# L3DCube_16x16_Base_Rev3.net
KiCad netlist of a schematic drawn in EAGLE
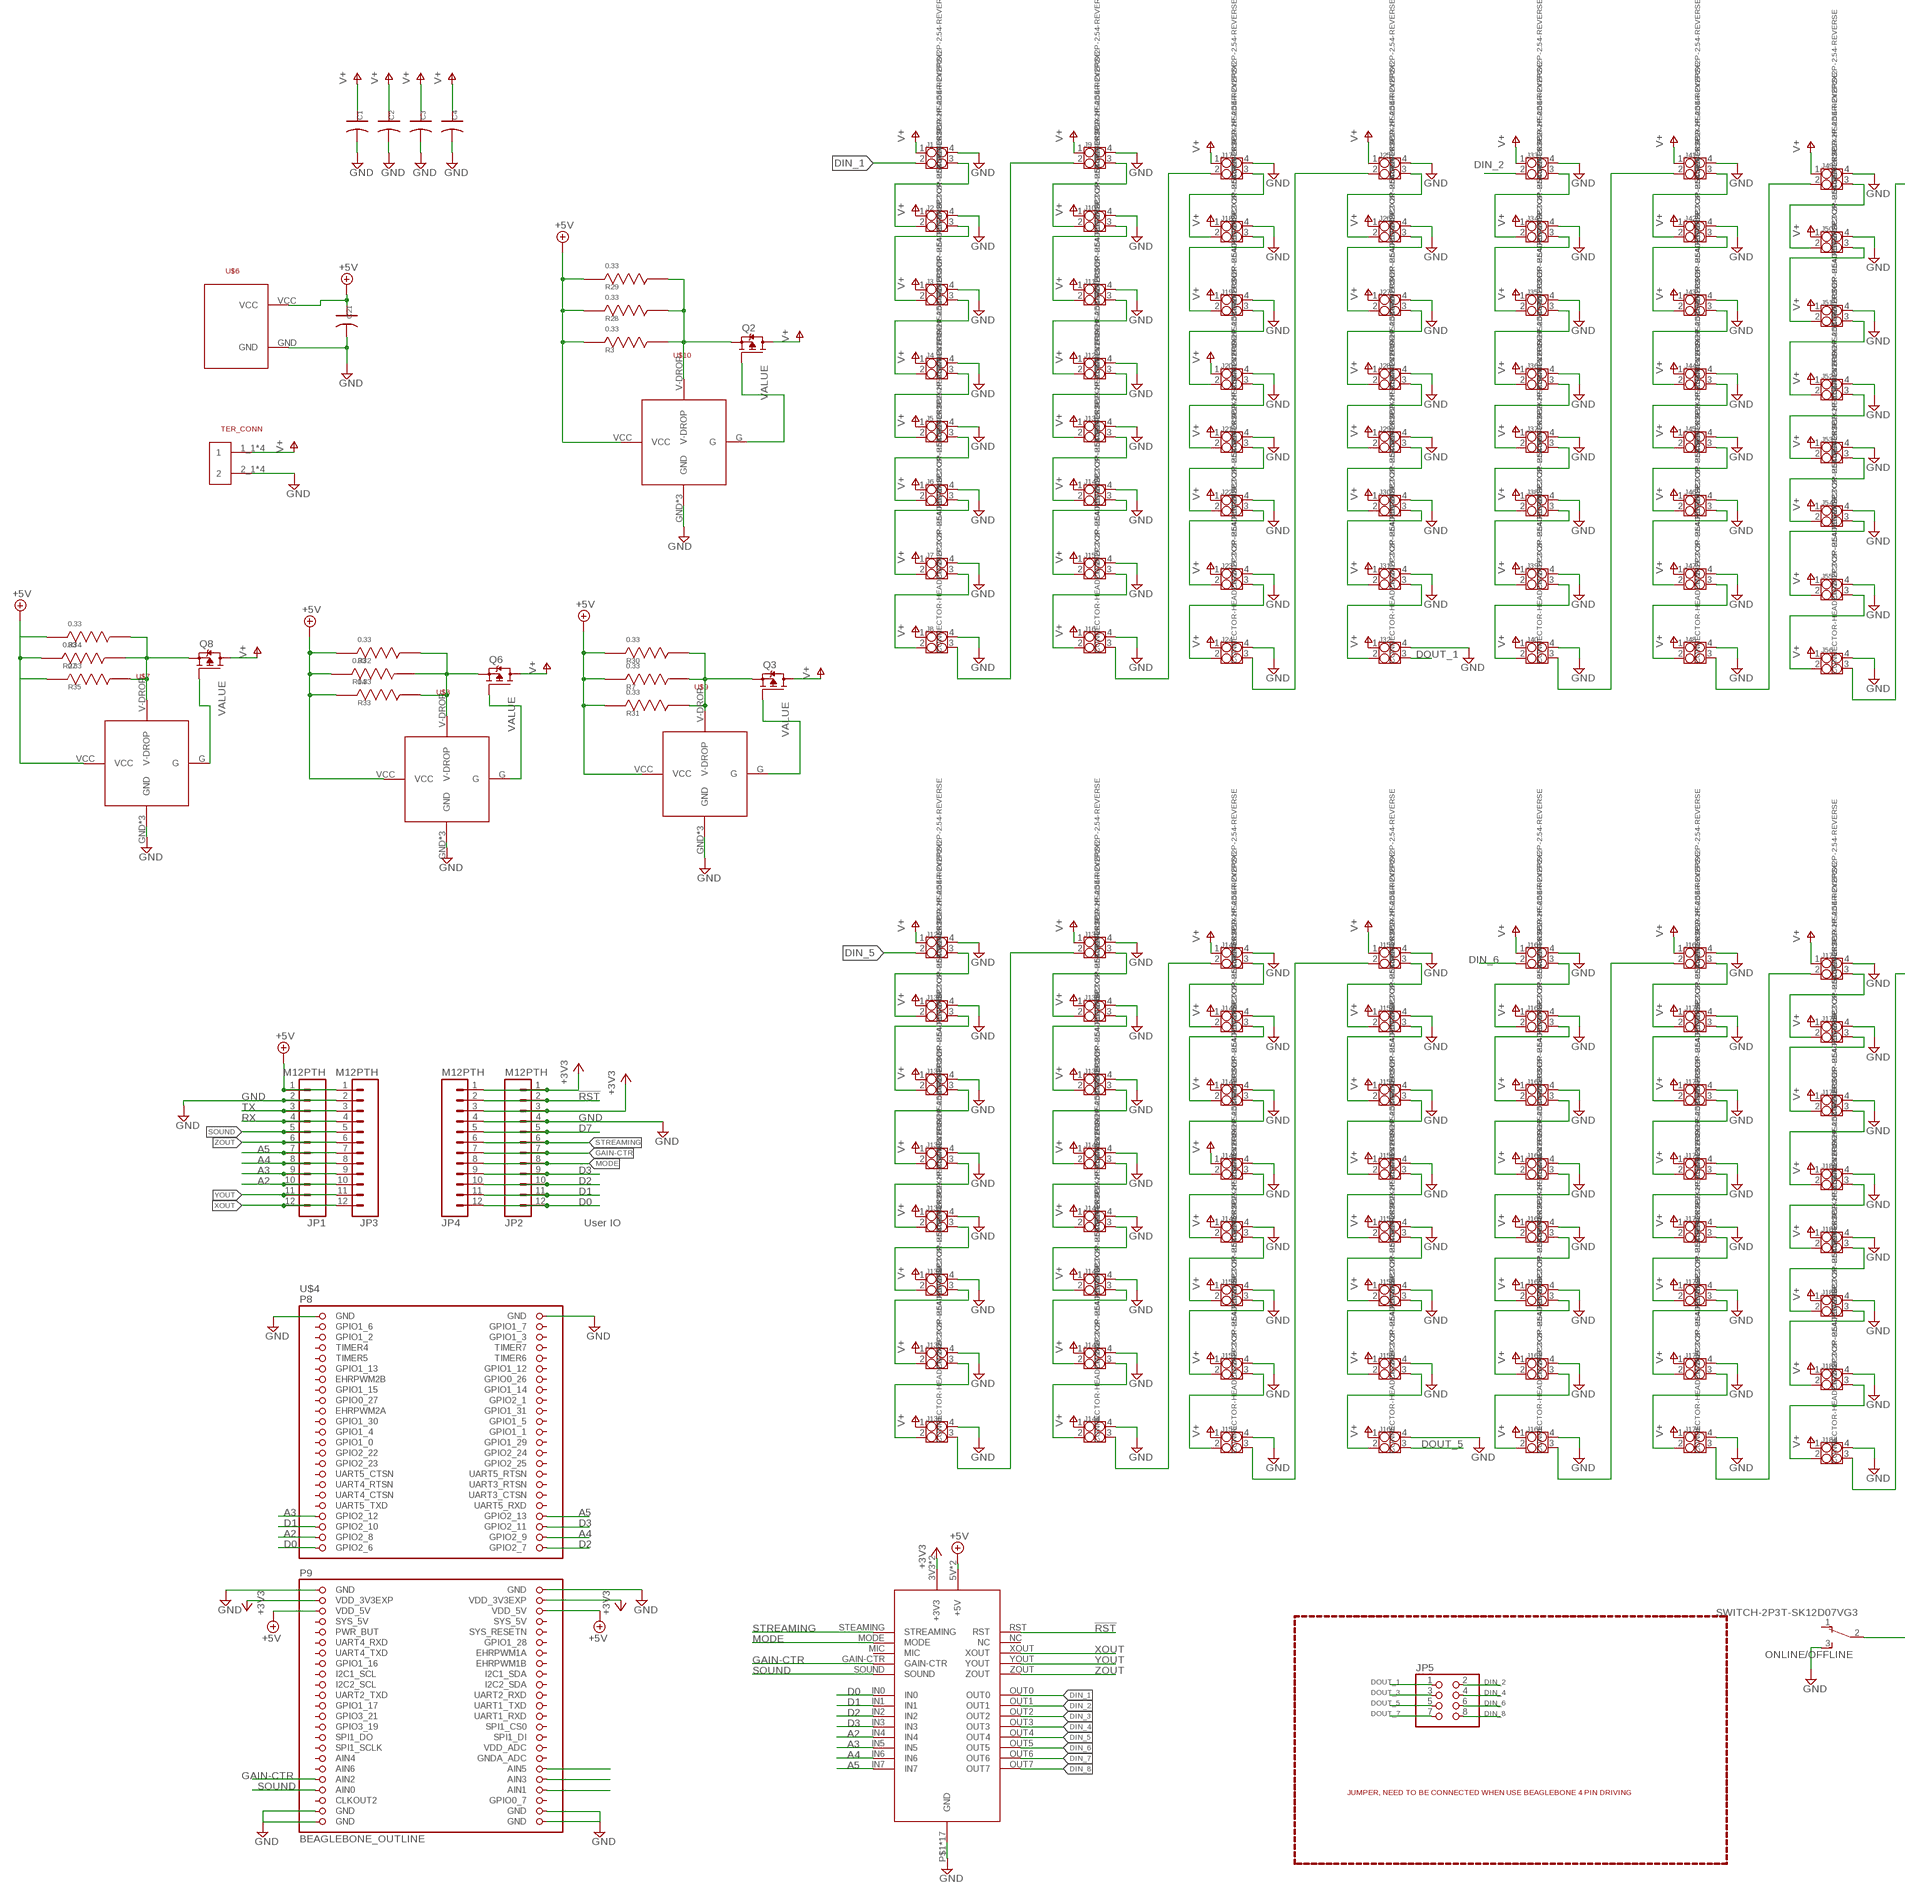
[diagram p0: schematic, sheet 1, part 1 of 2]
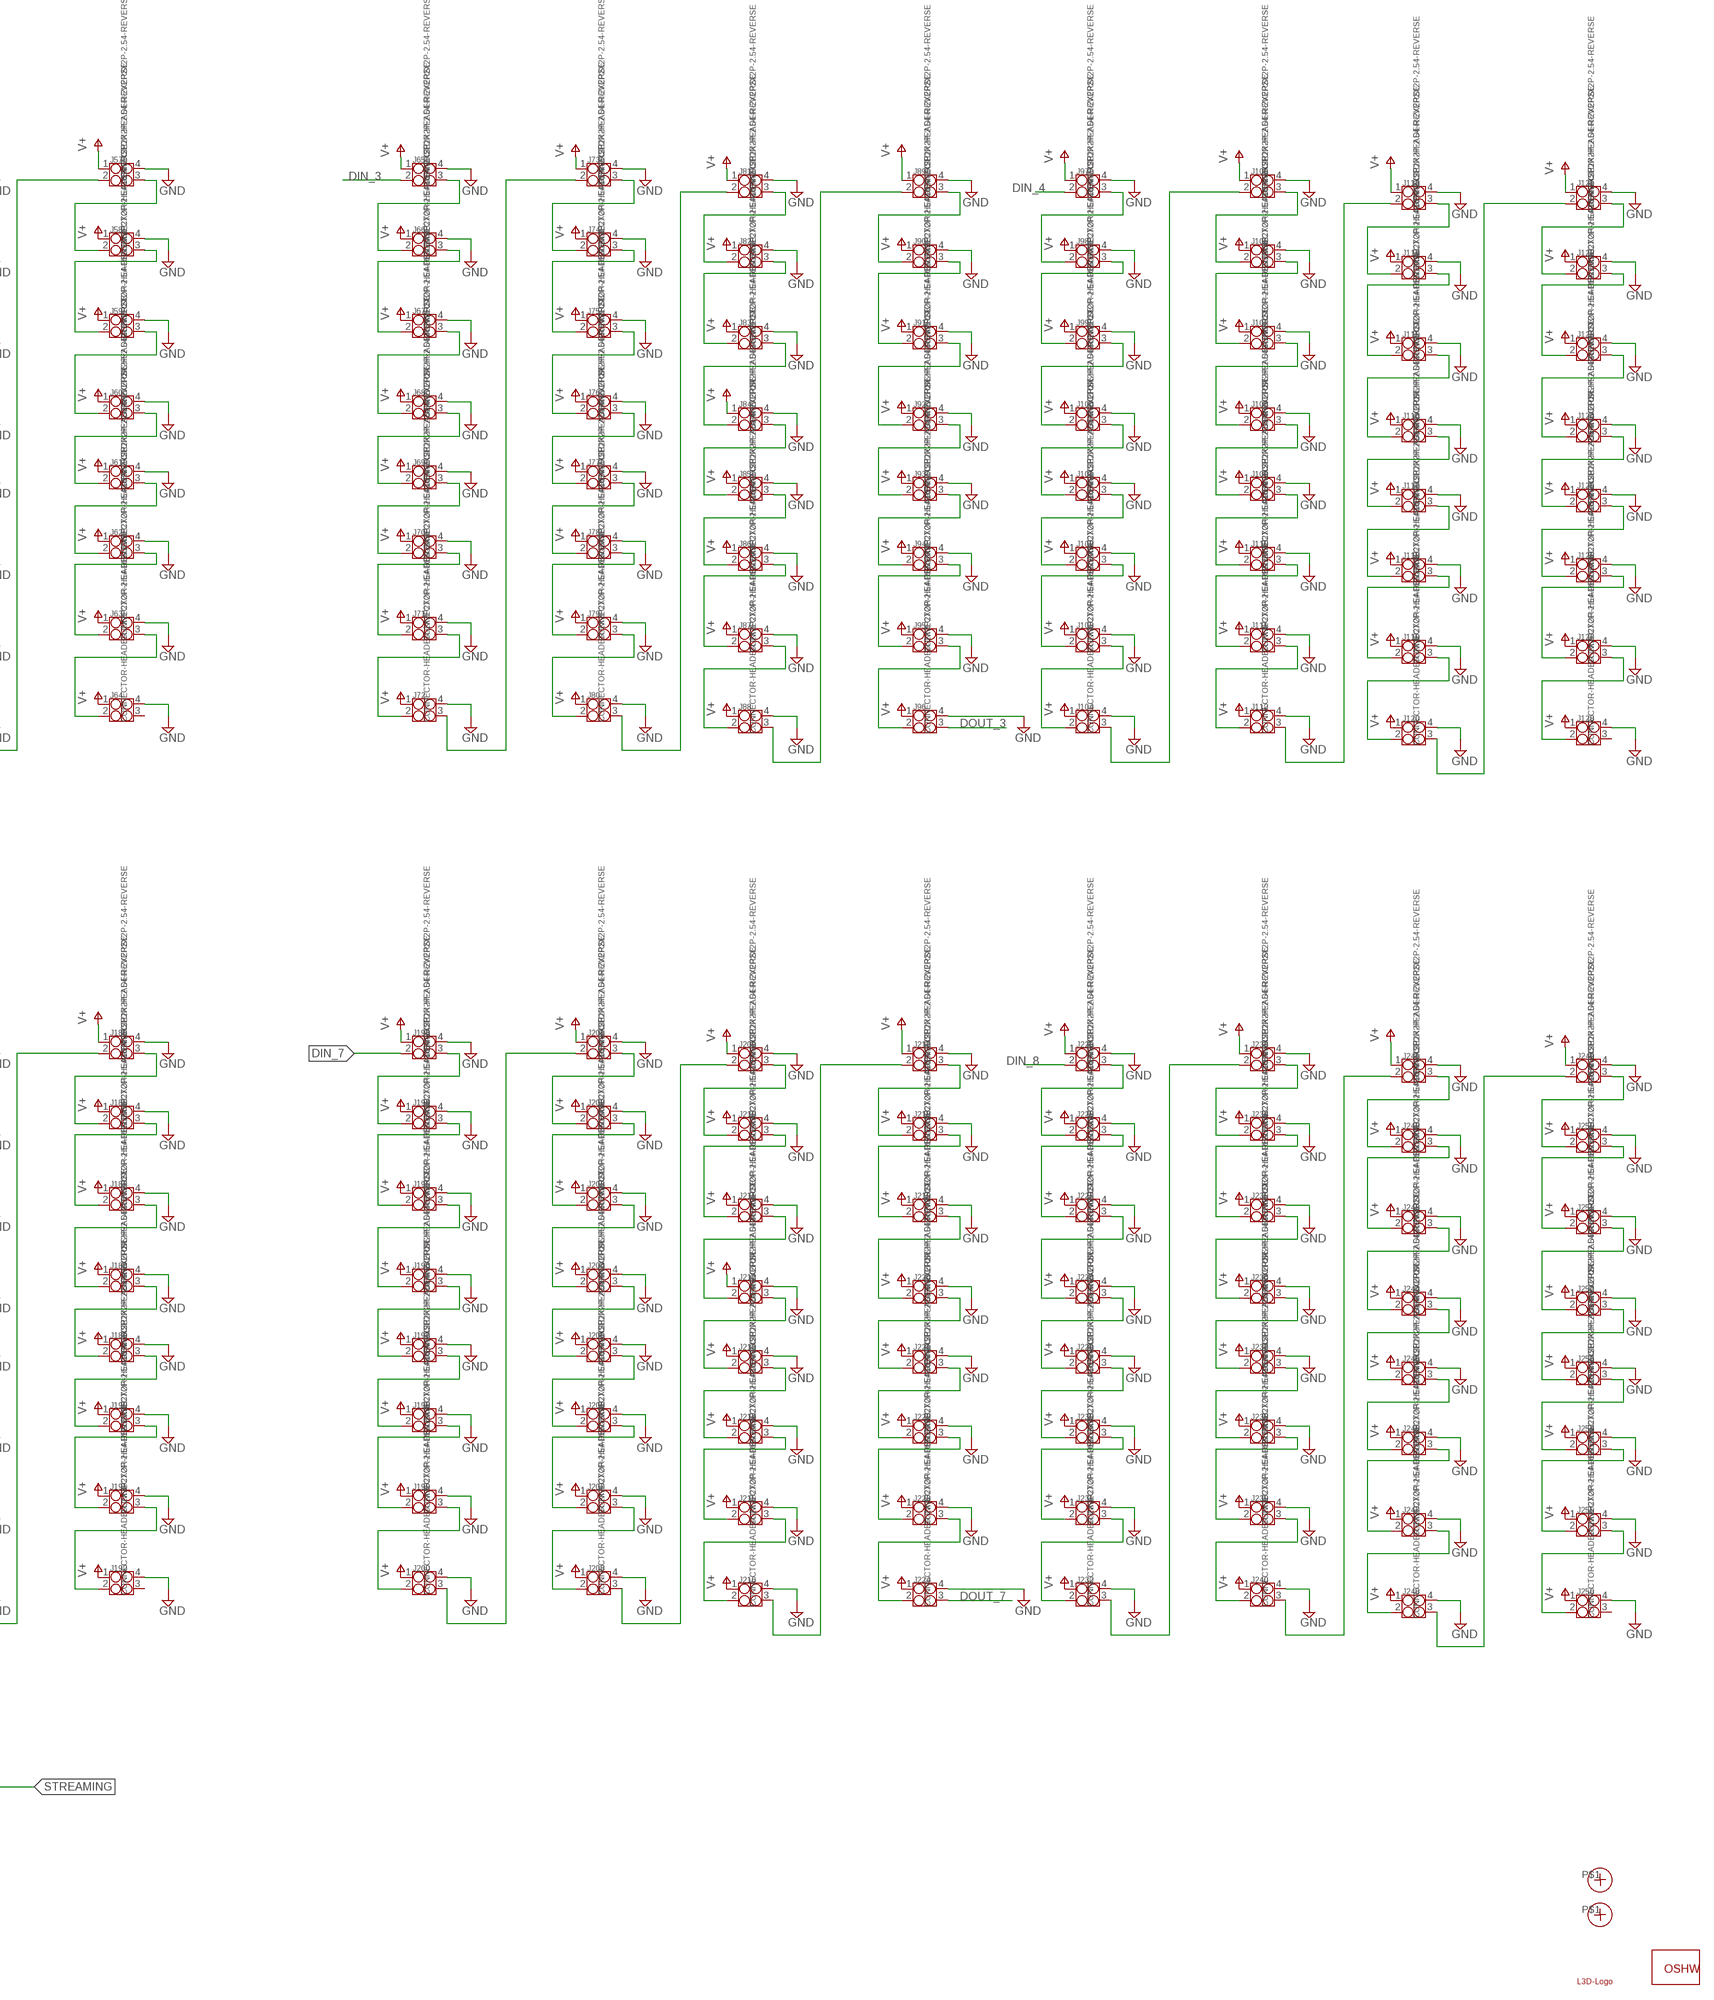
[diagram p1: schematic, sheet 1, part 2 of 2]

(export (version "E")
  (design (tool "Eeschema 10.0.6"))
  (components
    (comp (ref "C1")
      (value "C-POLAR")
      (footprint "eagle-import:CAPACITOR-E3-8")
      (libsource (lib "eagle-import") (part "C-POLAR"))
    )
    (comp (ref "C2")
      (value "C-POLAR")
      (footprint "eagle-import:CAPACITOR-E3-8")
      (libsource (lib "eagle-import") (part "C-POLAR"))
    )
    (comp (ref "C3")
      (value "C-POLAR")
      (footprint "eagle-import:CAPACITOR-E3-8")
      (libsource (lib "eagle-import") (part "C-POLAR"))
    )
    (comp (ref "C4")
      (value "C-POLAR")
      (footprint "eagle-import:CAPACITOR-E3-8")
      (libsource (lib "eagle-import") (part "C-POLAR"))
    )
    (comp (ref "C21")
      (value "C-POLAR")
      (footprint "eagle-import:CAPACITOR-E3-8")
      (libsource (lib "eagle-import") (part "C-POLAR"))
    )
    (comp (ref "GOLD_ORB_SM1")
      (value "OSHWLOGO_GOLD_ORB_LG")
      (footprint "eagle-import:OSHW0")
      (libsource (lib "eagle-import") (part "OSHWLOGO_GOLD_ORB_LG"))
    )
    (comp (ref "J1")
      (value "CONNECTOR-HEADER-2X2P2X2P-2.54-REVERSE")
      (footprint "eagle-import:2X2P-2.54-REVERSE")
      (libsource (lib "eagle-import") (part "CONNECTOR-HEADER-2X2P2X2P-2.54-REVERSE"))
    )
    (comp (ref "J2")
      (value "CONNECTOR-HEADER-2X2P2X2P-2.54-REVERSE")
      (footprint "eagle-import:2X2P-2.54-REVERSE")
      (libsource (lib "eagle-import") (part "CONNECTOR-HEADER-2X2P2X2P-2.54-REVERSE"))
    )
    (comp (ref "J3")
      (value "CONNECTOR-HEADER-2X2P2X2P-2.54-REVERSE")
      (footprint "eagle-import:2X2P-2.54-REVERSE")
      (libsource (lib "eagle-import") (part "CONNECTOR-HEADER-2X2P2X2P-2.54-REVERSE"))
    )
    (comp (ref "J4")
      (value "CONNECTOR-HEADER-2X2P2X2P-2.54-REVERSE")
      (footprint "eagle-import:2X2P-2.54-REVERSE")
      (libsource (lib "eagle-import") (part "CONNECTOR-HEADER-2X2P2X2P-2.54-REVERSE"))
    )
    (comp (ref "J5")
      (value "CONNECTOR-HEADER-2X2P2X2P-2.54-REVERSE")
      (footprint "eagle-import:2X2P-2.54-REVERSE")
      (libsource (lib "eagle-import") (part "CONNECTOR-HEADER-2X2P2X2P-2.54-REVERSE"))
    )
    (comp (ref "J6")
      (value "CONNECTOR-HEADER-2X2P2X2P-2.54-REVERSE")
      (footprint "eagle-import:2X2P-2.54-REVERSE")
      (libsource (lib "eagle-import") (part "CONNECTOR-HEADER-2X2P2X2P-2.54-REVERSE"))
    )
    (comp (ref "J7")
      (value "CONNECTOR-HEADER-2X2P2X2P-2.54-REVERSE")
      (footprint "eagle-import:2X2P-2.54-REVERSE")
      (libsource (lib "eagle-import") (part "CONNECTOR-HEADER-2X2P2X2P-2.54-REVERSE"))
    )
    (comp (ref "J8")
      (value "CONNECTOR-HEADER-2X2P2X2P-2.54-REVERSE")
      (footprint "eagle-import:2X2P-2.54-REVERSE")
      (libsource (lib "eagle-import") (part "CONNECTOR-HEADER-2X2P2X2P-2.54-REVERSE"))
    )
    (comp (ref "J9")
      (value "CONNECTOR-HEADER-2X2P2X2P-2.54-REVERSE")
      (footprint "eagle-import:2X2P-2.54-REVERSE")
      (libsource (lib "eagle-import") (part "CONNECTOR-HEADER-2X2P2X2P-2.54-REVERSE"))
    )
    (comp (ref "J10")
      (value "CONNECTOR-HEADER-2X2P2X2P-2.54-REVERSE")
      (footprint "eagle-import:2X2P-2.54-REVERSE")
      (libsource (lib "eagle-import") (part "CONNECTOR-HEADER-2X2P2X2P-2.54-REVERSE"))
    )
    (comp (ref "J11")
      (value "CONNECTOR-HEADER-2X2P2X2P-2.54-REVERSE")
      (footprint "eagle-import:2X2P-2.54-REVERSE")
      (libsource (lib "eagle-import") (part "CONNECTOR-HEADER-2X2P2X2P-2.54-REVERSE"))
    )
    (comp (ref "J12")
      (value "CONNECTOR-HEADER-2X2P2X2P-2.54-REVERSE")
      (footprint "eagle-import:2X2P-2.54-REVERSE")
      (libsource (lib "eagle-import") (part "CONNECTOR-HEADER-2X2P2X2P-2.54-REVERSE"))
    )
    (comp (ref "J13")
      (value "CONNECTOR-HEADER-2X2P2X2P-2.54-REVERSE")
      (footprint "eagle-import:2X2P-2.54-REVERSE")
      (libsource (lib "eagle-import") (part "CONNECTOR-HEADER-2X2P2X2P-2.54-REVERSE"))
    )
    (comp (ref "J14")
      (value "CONNECTOR-HEADER-2X2P2X2P-2.54-REVERSE")
      (footprint "eagle-import:2X2P-2.54-REVERSE")
      (libsource (lib "eagle-import") (part "CONNECTOR-HEADER-2X2P2X2P-2.54-REVERSE"))
    )
    (comp (ref "J15")
      (value "CONNECTOR-HEADER-2X2P2X2P-2.54-REVERSE")
      (footprint "eagle-import:2X2P-2.54-REVERSE")
      (libsource (lib "eagle-import") (part "CONNECTOR-HEADER-2X2P2X2P-2.54-REVERSE"))
    )
    (comp (ref "J16")
      (value "CONNECTOR-HEADER-2X2P2X2P-2.54-REVERSE")
      (footprint "eagle-import:2X2P-2.54-REVERSE")
      (libsource (lib "eagle-import") (part "CONNECTOR-HEADER-2X2P2X2P-2.54-REVERSE"))
    )
    (comp (ref "J17")
      (value "CONNECTOR-HEADER-2X2P2X2P-2.54-REVERSE")
      (footprint "eagle-import:2X2P-2.54-REVERSE")
      (libsource (lib "eagle-import") (part "CONNECTOR-HEADER-2X2P2X2P-2.54-REVERSE"))
    )
    (comp (ref "J18")
      (value "CONNECTOR-HEADER-2X2P2X2P-2.54-REVERSE")
      (footprint "eagle-import:2X2P-2.54-REVERSE")
      (libsource (lib "eagle-import") (part "CONNECTOR-HEADER-2X2P2X2P-2.54-REVERSE"))
    )
    (comp (ref "J19")
      (value "CONNECTOR-HEADER-2X2P2X2P-2.54-REVERSE")
      (footprint "eagle-import:2X2P-2.54-REVERSE")
      (libsource (lib "eagle-import") (part "CONNECTOR-HEADER-2X2P2X2P-2.54-REVERSE"))
    )
    (comp (ref "J20")
      (value "CONNECTOR-HEADER-2X2P2X2P-2.54-REVERSE")
      (footprint "eagle-import:2X2P-2.54-REVERSE")
      (libsource (lib "eagle-import") (part "CONNECTOR-HEADER-2X2P2X2P-2.54-REVERSE"))
    )
    (comp (ref "J21")
      (value "CONNECTOR-HEADER-2X2P2X2P-2.54-REVERSE")
      (footprint "eagle-import:2X2P-2.54-REVERSE")
      (libsource (lib "eagle-import") (part "CONNECTOR-HEADER-2X2P2X2P-2.54-REVERSE"))
    )
    (comp (ref "J22")
      (value "CONNECTOR-HEADER-2X2P2X2P-2.54-REVERSE")
      (footprint "eagle-import:2X2P-2.54-REVERSE")
      (libsource (lib "eagle-import") (part "CONNECTOR-HEADER-2X2P2X2P-2.54-REVERSE"))
    )
    (comp (ref "J23")
      (value "CONNECTOR-HEADER-2X2P2X2P-2.54-REVERSE")
      (footprint "eagle-import:2X2P-2.54-REVERSE")
      (libsource (lib "eagle-import") (part "CONNECTOR-HEADER-2X2P2X2P-2.54-REVERSE"))
    )
    (comp (ref "J24")
      (value "CONNECTOR-HEADER-2X2P2X2P-2.54-REVERSE")
      (footprint "eagle-import:2X2P-2.54-REVERSE")
      (libsource (lib "eagle-import") (part "CONNECTOR-HEADER-2X2P2X2P-2.54-REVERSE"))
    )
    (comp (ref "J25")
      (value "CONNECTOR-HEADER-2X2P2X2P-2.54-REVERSE")
      (footprint "eagle-import:2X2P-2.54-REVERSE")
      (libsource (lib "eagle-import") (part "CONNECTOR-HEADER-2X2P2X2P-2.54-REVERSE"))
    )
    (comp (ref "J26")
      (value "CONNECTOR-HEADER-2X2P2X2P-2.54-REVERSE")
      (footprint "eagle-import:2X2P-2.54-REVERSE")
      (libsource (lib "eagle-import") (part "CONNECTOR-HEADER-2X2P2X2P-2.54-REVERSE"))
    )
    (comp (ref "J27")
      (value "CONNECTOR-HEADER-2X2P2X2P-2.54-REVERSE")
      (footprint "eagle-import:2X2P-2.54-REVERSE")
      (libsource (lib "eagle-import") (part "CONNECTOR-HEADER-2X2P2X2P-2.54-REVERSE"))
    )
    (comp (ref "J28")
      (value "CONNECTOR-HEADER-2X2P2X2P-2.54-REVERSE")
      (footprint "eagle-import:2X2P-2.54-REVERSE")
      (libsource (lib "eagle-import") (part "CONNECTOR-HEADER-2X2P2X2P-2.54-REVERSE"))
    )
    (comp (ref "J29")
      (value "CONNECTOR-HEADER-2X2P2X2P-2.54-REVERSE")
      (footprint "eagle-import:2X2P-2.54-REVERSE")
      (libsource (lib "eagle-import") (part "CONNECTOR-HEADER-2X2P2X2P-2.54-REVERSE"))
    )
    (comp (ref "J30")
      (value "CONNECTOR-HEADER-2X2P2X2P-2.54-REVERSE")
      (footprint "eagle-import:2X2P-2.54-REVERSE")
      (libsource (lib "eagle-import") (part "CONNECTOR-HEADER-2X2P2X2P-2.54-REVERSE"))
    )
    (comp (ref "J31")
      (value "CONNECTOR-HEADER-2X2P2X2P-2.54-REVERSE")
      (footprint "eagle-import:2X2P-2.54-REVERSE")
      (libsource (lib "eagle-import") (part "CONNECTOR-HEADER-2X2P2X2P-2.54-REVERSE"))
    )
    (comp (ref "J32")
      (value "CONNECTOR-HEADER-2X2P2X2P-2.54-REVERSE")
      (footprint "eagle-import:2X2P-2.54-REVERSE")
      (libsource (lib "eagle-import") (part "CONNECTOR-HEADER-2X2P2X2P-2.54-REVERSE"))
    )
    (comp (ref "J33")
      (value "CONNECTOR-HEADER-2X2P2X2P-2.54-REVERSE")
      (footprint "eagle-import:2X2P-2.54-REVERSE")
      (libsource (lib "eagle-import") (part "CONNECTOR-HEADER-2X2P2X2P-2.54-REVERSE"))
    )
    (comp (ref "J34")
      (value "CONNECTOR-HEADER-2X2P2X2P-2.54-REVERSE")
      (footprint "eagle-import:2X2P-2.54-REVERSE")
      (libsource (lib "eagle-import") (part "CONNECTOR-HEADER-2X2P2X2P-2.54-REVERSE"))
    )
    (comp (ref "J35")
      (value "CONNECTOR-HEADER-2X2P2X2P-2.54-REVERSE")
      (footprint "eagle-import:2X2P-2.54-REVERSE")
      (libsource (lib "eagle-import") (part "CONNECTOR-HEADER-2X2P2X2P-2.54-REVERSE"))
    )
    (comp (ref "J36")
      (value "CONNECTOR-HEADER-2X2P2X2P-2.54-REVERSE")
      (footprint "eagle-import:2X2P-2.54-REVERSE")
      (libsource (lib "eagle-import") (part "CONNECTOR-HEADER-2X2P2X2P-2.54-REVERSE"))
    )
    (comp (ref "J37")
      (value "CONNECTOR-HEADER-2X2P2X2P-2.54-REVERSE")
      (footprint "eagle-import:2X2P-2.54-REVERSE")
      (libsource (lib "eagle-import") (part "CONNECTOR-HEADER-2X2P2X2P-2.54-REVERSE"))
    )
    (comp (ref "J38")
      (value "CONNECTOR-HEADER-2X2P2X2P-2.54-REVERSE")
      (footprint "eagle-import:2X2P-2.54-REVERSE")
      (libsource (lib "eagle-import") (part "CONNECTOR-HEADER-2X2P2X2P-2.54-REVERSE"))
    )
    (comp (ref "J39")
      (value "CONNECTOR-HEADER-2X2P2X2P-2.54-REVERSE")
      (footprint "eagle-import:2X2P-2.54-REVERSE")
      (libsource (lib "eagle-import") (part "CONNECTOR-HEADER-2X2P2X2P-2.54-REVERSE"))
    )
    (comp (ref "J40")
      (value "CONNECTOR-HEADER-2X2P2X2P-2.54-REVERSE")
      (footprint "eagle-import:2X2P-2.54-REVERSE")
      (libsource (lib "eagle-import") (part "CONNECTOR-HEADER-2X2P2X2P-2.54-REVERSE"))
    )
    (comp (ref "J41")
      (value "CONNECTOR-HEADER-2X2P2X2P-2.54-REVERSE")
      (footprint "eagle-import:2X2P-2.54-REVERSE")
      (libsource (lib "eagle-import") (part "CONNECTOR-HEADER-2X2P2X2P-2.54-REVERSE"))
    )
    (comp (ref "J42")
      (value "CONNECTOR-HEADER-2X2P2X2P-2.54-REVERSE")
      (footprint "eagle-import:2X2P-2.54-REVERSE")
      (libsource (lib "eagle-import") (part "CONNECTOR-HEADER-2X2P2X2P-2.54-REVERSE"))
    )
    (comp (ref "J43")
      (value "CONNECTOR-HEADER-2X2P2X2P-2.54-REVERSE")
      (footprint "eagle-import:2X2P-2.54-REVERSE")
      (libsource (lib "eagle-import") (part "CONNECTOR-HEADER-2X2P2X2P-2.54-REVERSE"))
    )
    (comp (ref "J44")
      (value "CONNECTOR-HEADER-2X2P2X2P-2.54-REVERSE")
      (footprint "eagle-import:2X2P-2.54-REVERSE")
      (libsource (lib "eagle-import") (part "CONNECTOR-HEADER-2X2P2X2P-2.54-REVERSE"))
    )
    (comp (ref "J45")
      (value "CONNECTOR-HEADER-2X2P2X2P-2.54-REVERSE")
      (footprint "eagle-import:2X2P-2.54-REVERSE")
      (libsource (lib "eagle-import") (part "CONNECTOR-HEADER-2X2P2X2P-2.54-REVERSE"))
    )
    (comp (ref "J46")
      (value "CONNECTOR-HEADER-2X2P2X2P-2.54-REVERSE")
      (footprint "eagle-import:2X2P-2.54-REVERSE")
      (libsource (lib "eagle-import") (part "CONNECTOR-HEADER-2X2P2X2P-2.54-REVERSE"))
    )
    (comp (ref "J47")
      (value "CONNECTOR-HEADER-2X2P2X2P-2.54-REVERSE")
      (footprint "eagle-import:2X2P-2.54-REVERSE")
      (libsource (lib "eagle-import") (part "CONNECTOR-HEADER-2X2P2X2P-2.54-REVERSE"))
    )
    (comp (ref "J48")
      (value "CONNECTOR-HEADER-2X2P2X2P-2.54-REVERSE")
      (footprint "eagle-import:2X2P-2.54-REVERSE")
      (libsource (lib "eagle-import") (part "CONNECTOR-HEADER-2X2P2X2P-2.54-REVERSE"))
    )
    (comp (ref "J49")
      (value "CONNECTOR-HEADER-2X2P2X2P-2.54-REVERSE")
      (footprint "eagle-import:2X2P-2.54-REVERSE")
      (libsource (lib "eagle-import") (part "CONNECTOR-HEADER-2X2P2X2P-2.54-REVERSE"))
    )
    (comp (ref "J50")
      (value "CONNECTOR-HEADER-2X2P2X2P-2.54-REVERSE")
      (footprint "eagle-import:2X2P-2.54-REVERSE")
      (libsource (lib "eagle-import") (part "CONNECTOR-HEADER-2X2P2X2P-2.54-REVERSE"))
    )
    (comp (ref "J51")
      (value "CONNECTOR-HEADER-2X2P2X2P-2.54-REVERSE")
      (footprint "eagle-import:2X2P-2.54-REVERSE")
      (libsource (lib "eagle-import") (part "CONNECTOR-HEADER-2X2P2X2P-2.54-REVERSE"))
    )
    (comp (ref "J52")
      (value "CONNECTOR-HEADER-2X2P2X2P-2.54-REVERSE")
      (footprint "eagle-import:2X2P-2.54-REVERSE")
      (libsource (lib "eagle-import") (part "CONNECTOR-HEADER-2X2P2X2P-2.54-REVERSE"))
    )
    (comp (ref "J53")
      (value "CONNECTOR-HEADER-2X2P2X2P-2.54-REVERSE")
      (footprint "eagle-import:2X2P-2.54-REVERSE")
      (libsource (lib "eagle-import") (part "CONNECTOR-HEADER-2X2P2X2P-2.54-REVERSE"))
    )
    (comp (ref "J54")
      (value "CONNECTOR-HEADER-2X2P2X2P-2.54-REVERSE")
      (footprint "eagle-import:2X2P-2.54-REVERSE")
      (libsource (lib "eagle-import") (part "CONNECTOR-HEADER-2X2P2X2P-2.54-REVERSE"))
    )
    (comp (ref "J55")
      (value "CONNECTOR-HEADER-2X2P2X2P-2.54-REVERSE")
      (footprint "eagle-import:2X2P-2.54-REVERSE")
      (libsource (lib "eagle-import") (part "CONNECTOR-HEADER-2X2P2X2P-2.54-REVERSE"))
    )
    (comp (ref "J56")
      (value "CONNECTOR-HEADER-2X2P2X2P-2.54-REVERSE")
      (footprint "eagle-import:2X2P-2.54-REVERSE")
      (libsource (lib "eagle-import") (part "CONNECTOR-HEADER-2X2P2X2P-2.54-REVERSE"))
    )
    (comp (ref "J57")
      (value "CONNECTOR-HEADER-2X2P2X2P-2.54-REVERSE")
      (footprint "eagle-import:2X2P-2.54-REVERSE")
      (libsource (lib "eagle-import") (part "CONNECTOR-HEADER-2X2P2X2P-2.54-REVERSE"))
    )
    (comp (ref "J58")
      (value "CONNECTOR-HEADER-2X2P2X2P-2.54-REVERSE")
      (footprint "eagle-import:2X2P-2.54-REVERSE")
      (libsource (lib "eagle-import") (part "CONNECTOR-HEADER-2X2P2X2P-2.54-REVERSE"))
    )
    (comp (ref "J59")
      (value "CONNECTOR-HEADER-2X2P2X2P-2.54-REVERSE")
      (footprint "eagle-import:2X2P-2.54-REVERSE")
      (libsource (lib "eagle-import") (part "CONNECTOR-HEADER-2X2P2X2P-2.54-REVERSE"))
    )
    (comp (ref "J60")
      (value "CONNECTOR-HEADER-2X2P2X2P-2.54-REVERSE")
      (footprint "eagle-import:2X2P-2.54-REVERSE")
      (libsource (lib "eagle-import") (part "CONNECTOR-HEADER-2X2P2X2P-2.54-REVERSE"))
    )
    (comp (ref "J61")
      (value "CONNECTOR-HEADER-2X2P2X2P-2.54-REVERSE")
      (footprint "eagle-import:2X2P-2.54-REVERSE")
      (libsource (lib "eagle-import") (part "CONNECTOR-HEADER-2X2P2X2P-2.54-REVERSE"))
    )
    (comp (ref "J62")
      (value "CONNECTOR-HEADER-2X2P2X2P-2.54-REVERSE")
      (footprint "eagle-import:2X2P-2.54-REVERSE")
      (libsource (lib "eagle-import") (part "CONNECTOR-HEADER-2X2P2X2P-2.54-REVERSE"))
    )
    (comp (ref "J63")
      (value "CONNECTOR-HEADER-2X2P2X2P-2.54-REVERSE")
      (footprint "eagle-import:2X2P-2.54-REVERSE")
      (libsource (lib "eagle-import") (part "CONNECTOR-HEADER-2X2P2X2P-2.54-REVERSE"))
    )
    (comp (ref "J64")
      (value "CONNECTOR-HEADER-2X2P2X2P-2.54-REVERSE")
      (footprint "eagle-import:2X2P-2.54-REVERSE")
      (libsource (lib "eagle-import") (part "CONNECTOR-HEADER-2X2P2X2P-2.54-REVERSE"))
    )
    (comp (ref "J65")
      (value "CONNECTOR-HEADER-2X2P2X2P-2.54-REVERSE")
      (footprint "eagle-import:2X2P-2.54-REVERSE")
      (libsource (lib "eagle-import") (part "CONNECTOR-HEADER-2X2P2X2P-2.54-REVERSE"))
    )
    (comp (ref "J66")
      (value "CONNECTOR-HEADER-2X2P2X2P-2.54-REVERSE")
      (footprint "eagle-import:2X2P-2.54-REVERSE")
      (libsource (lib "eagle-import") (part "CONNECTOR-HEADER-2X2P2X2P-2.54-REVERSE"))
    )
    (comp (ref "J67")
      (value "CONNECTOR-HEADER-2X2P2X2P-2.54-REVERSE")
      (footprint "eagle-import:2X2P-2.54-REVERSE")
      (libsource (lib "eagle-import") (part "CONNECTOR-HEADER-2X2P2X2P-2.54-REVERSE"))
    )
    (comp (ref "J68")
      (value "CONNECTOR-HEADER-2X2P2X2P-2.54-REVERSE")
      (footprint "eagle-import:2X2P-2.54-REVERSE")
      (libsource (lib "eagle-import") (part "CONNECTOR-HEADER-2X2P2X2P-2.54-REVERSE"))
    )
    (comp (ref "J69")
      (value "CONNECTOR-HEADER-2X2P2X2P-2.54-REVERSE")
      (footprint "eagle-import:2X2P-2.54-REVERSE")
      (libsource (lib "eagle-import") (part "CONNECTOR-HEADER-2X2P2X2P-2.54-REVERSE"))
    )
    (comp (ref "J70")
      (value "CONNECTOR-HEADER-2X2P2X2P-2.54-REVERSE")
      (footprint "eagle-import:2X2P-2.54-REVERSE")
      (libsource (lib "eagle-import") (part "CONNECTOR-HEADER-2X2P2X2P-2.54-REVERSE"))
    )
    (comp (ref "J71")
      (value "CONNECTOR-HEADER-2X2P2X2P-2.54-REVERSE")
      (footprint "eagle-import:2X2P-2.54-REVERSE")
      (libsource (lib "eagle-import") (part "CONNECTOR-HEADER-2X2P2X2P-2.54-REVERSE"))
    )
    (comp (ref "J72")
      (value "CONNECTOR-HEADER-2X2P2X2P-2.54-REVERSE")
      (footprint "eagle-import:2X2P-2.54-REVERSE")
      (libsource (lib "eagle-import") (part "CONNECTOR-HEADER-2X2P2X2P-2.54-REVERSE"))
    )
    (comp (ref "J73")
      (value "CONNECTOR-HEADER-2X2P2X2P-2.54-REVERSE")
      (footprint "eagle-import:2X2P-2.54-REVERSE")
      (libsource (lib "eagle-import") (part "CONNECTOR-HEADER-2X2P2X2P-2.54-REVERSE"))
    )
    (comp (ref "J74")
      (value "CONNECTOR-HEADER-2X2P2X2P-2.54-REVERSE")
      (footprint "eagle-import:2X2P-2.54-REVERSE")
      (libsource (lib "eagle-import") (part "CONNECTOR-HEADER-2X2P2X2P-2.54-REVERSE"))
    )
    (comp (ref "J75")
      (value "CONNECTOR-HEADER-2X2P2X2P-2.54-REVERSE")
      (footprint "eagle-import:2X2P-2.54-REVERSE")
      (libsource (lib "eagle-import") (part "CONNECTOR-HEADER-2X2P2X2P-2.54-REVERSE"))
    )
    (comp (ref "J76")
      (value "CONNECTOR-HEADER-2X2P2X2P-2.54-REVERSE")
      (footprint "eagle-import:2X2P-2.54-REVERSE")
      (libsource (lib "eagle-import") (part "CONNECTOR-HEADER-2X2P2X2P-2.54-REVERSE"))
    )
    (comp (ref "J77")
      (value "CONNECTOR-HEADER-2X2P2X2P-2.54-REVERSE")
      (footprint "eagle-import:2X2P-2.54-REVERSE")
      (libsource (lib "eagle-import") (part "CONNECTOR-HEADER-2X2P2X2P-2.54-REVERSE"))
    )
    (comp (ref "J78")
      (value "CONNECTOR-HEADER-2X2P2X2P-2.54-REVERSE")
      (footprint "eagle-import:2X2P-2.54-REVERSE")
      (libsource (lib "eagle-import") (part "CONNECTOR-HEADER-2X2P2X2P-2.54-REVERSE"))
    )
    (comp (ref "J79")
      (value "CONNECTOR-HEADER-2X2P2X2P-2.54-REVERSE")
      (footprint "eagle-import:2X2P-2.54-REVERSE")
      (libsource (lib "eagle-import") (part "CONNECTOR-HEADER-2X2P2X2P-2.54-REVERSE"))
    )
    (comp (ref "J80")
      (value "CONNECTOR-HEADER-2X2P2X2P-2.54-REVERSE")
      (footprint "eagle-import:2X2P-2.54-REVERSE")
      (libsource (lib "eagle-import") (part "CONNECTOR-HEADER-2X2P2X2P-2.54-REVERSE"))
    )
    (comp (ref "J81")
      (value "CONNECTOR-HEADER-2X2P2X2P-2.54-REVERSE")
      (footprint "eagle-import:2X2P-2.54-REVERSE")
      (libsource (lib "eagle-import") (part "CONNECTOR-HEADER-2X2P2X2P-2.54-REVERSE"))
    )
    (comp (ref "J82")
      (value "CONNECTOR-HEADER-2X2P2X2P-2.54-REVERSE")
      (footprint "eagle-import:2X2P-2.54-REVERSE")
      (libsource (lib "eagle-import") (part "CONNECTOR-HEADER-2X2P2X2P-2.54-REVERSE"))
    )
    (comp (ref "J83")
      (value "CONNECTOR-HEADER-2X2P2X2P-2.54-REVERSE")
      (footprint "eagle-import:2X2P-2.54-REVERSE")
      (libsource (lib "eagle-import") (part "CONNECTOR-HEADER-2X2P2X2P-2.54-REVERSE"))
    )
    (comp (ref "J84")
      (value "CONNECTOR-HEADER-2X2P2X2P-2.54-REVERSE")
      (footprint "eagle-import:2X2P-2.54-REVERSE")
      (libsource (lib "eagle-import") (part "CONNECTOR-HEADER-2X2P2X2P-2.54-REVERSE"))
    )
    (comp (ref "J85")
      (value "CONNECTOR-HEADER-2X2P2X2P-2.54-REVERSE")
      (footprint "eagle-import:2X2P-2.54-REVERSE")
      (libsource (lib "eagle-import") (part "CONNECTOR-HEADER-2X2P2X2P-2.54-REVERSE"))
    )
    (comp (ref "J86")
      (value "CONNECTOR-HEADER-2X2P2X2P-2.54-REVERSE")
      (footprint "eagle-import:2X2P-2.54-REVERSE")
      (libsource (lib "eagle-import") (part "CONNECTOR-HEADER-2X2P2X2P-2.54-REVERSE"))
    )
    (comp (ref "J87")
      (value "CONNECTOR-HEADER-2X2P2X2P-2.54-REVERSE")
      (footprint "eagle-import:2X2P-2.54-REVERSE")
      (libsource (lib "eagle-import") (part "CONNECTOR-HEADER-2X2P2X2P-2.54-REVERSE"))
    )
    (comp (ref "J88")
      (value "CONNECTOR-HEADER-2X2P2X2P-2.54-REVERSE")
      (footprint "eagle-import:2X2P-2.54-REVERSE")
      (libsource (lib "eagle-import") (part "CONNECTOR-HEADER-2X2P2X2P-2.54-REVERSE"))
    )
    (comp (ref "J89")
      (value "CONNECTOR-HEADER-2X2P2X2P-2.54-REVERSE")
      (footprint "eagle-import:2X2P-2.54-REVERSE")
      (libsource (lib "eagle-import") (part "CONNECTOR-HEADER-2X2P2X2P-2.54-REVERSE"))
    )
    (comp (ref "J90")
      (value "CONNECTOR-HEADER-2X2P2X2P-2.54-REVERSE")
      (footprint "eagle-import:2X2P-2.54-REVERSE")
      (libsource (lib "eagle-import") (part "CONNECTOR-HEADER-2X2P2X2P-2.54-REVERSE"))
    )
    (comp (ref "J91")
      (value "CONNECTOR-HEADER-2X2P2X2P-2.54-REVERSE")
      (footprint "eagle-import:2X2P-2.54-REVERSE")
      (libsource (lib "eagle-import") (part "CONNECTOR-HEADER-2X2P2X2P-2.54-REVERSE"))
    )
    (comp (ref "J92")
      (value "CONNECTOR-HEADER-2X2P2X2P-2.54-REVERSE")
      (footprint "eagle-import:2X2P-2.54-REVERSE")
      (libsource (lib "eagle-import") (part "CONNECTOR-HEADER-2X2P2X2P-2.54-REVERSE"))
    )
    (comp (ref "J93")
      (value "CONNECTOR-HEADER-2X2P2X2P-2.54-REVERSE")
      (footprint "eagle-import:2X2P-2.54-REVERSE")
      (libsource (lib "eagle-import") (part "CONNECTOR-HEADER-2X2P2X2P-2.54-REVERSE"))
    )
    (comp (ref "J94")
      (value "CONNECTOR-HEADER-2X2P2X2P-2.54-REVERSE")
      (footprint "eagle-import:2X2P-2.54-REVERSE")
      (libsource (lib "eagle-import") (part "CONNECTOR-HEADER-2X2P2X2P-2.54-REVERSE"))
    )
    (comp (ref "J95")
      (value "CONNECTOR-HEADER-2X2P2X2P-2.54-REVERSE")
      (footprint "eagle-import:2X2P-2.54-REVERSE")
      (libsource (lib "eagle-import") (part "CONNECTOR-HEADER-2X2P2X2P-2.54-REVERSE"))
    )
    (comp (ref "J96")
      (value "CONNECTOR-HEADER-2X2P2X2P-2.54-REVERSE")
      (footprint "eagle-import:2X2P-2.54-REVERSE")
      (libsource (lib "eagle-import") (part "CONNECTOR-HEADER-2X2P2X2P-2.54-REVERSE"))
    )
    (comp (ref "J97")
      (value "CONNECTOR-HEADER-2X2P2X2P-2.54-REVERSE")
      (footprint "eagle-import:2X2P-2.54-REVERSE")
      (libsource (lib "eagle-import") (part "CONNECTOR-HEADER-2X2P2X2P-2.54-REVERSE"))
    )
    (comp (ref "J98")
      (value "CONNECTOR-HEADER-2X2P2X2P-2.54-REVERSE")
      (footprint "eagle-import:2X2P-2.54-REVERSE")
      (libsource (lib "eagle-import") (part "CONNECTOR-HEADER-2X2P2X2P-2.54-REVERSE"))
    )
    (comp (ref "J99")
      (value "CONNECTOR-HEADER-2X2P2X2P-2.54-REVERSE")
      (footprint "eagle-import:2X2P-2.54-REVERSE")
      (libsource (lib "eagle-import") (part "CONNECTOR-HEADER-2X2P2X2P-2.54-REVERSE"))
    )
    (comp (ref "J100")
      (value "CONNECTOR-HEADER-2X2P2X2P-2.54-REVERSE")
      (footprint "eagle-import:2X2P-2.54-REVERSE")
      (libsource (lib "eagle-import") (part "CONNECTOR-HEADER-2X2P2X2P-2.54-REVERSE"))
    )
    (comp (ref "J101")
      (value "CONNECTOR-HEADER-2X2P2X2P-2.54-REVERSE")
      (footprint "eagle-import:2X2P-2.54-REVERSE")
      (libsource (lib "eagle-import") (part "CONNECTOR-HEADER-2X2P2X2P-2.54-REVERSE"))
    )
    (comp (ref "J102")
      (value "CONNECTOR-HEADER-2X2P2X2P-2.54-REVERSE")
      (footprint "eagle-import:2X2P-2.54-REVERSE")
      (libsource (lib "eagle-import") (part "CONNECTOR-HEADER-2X2P2X2P-2.54-REVERSE"))
    )
    (comp (ref "J103")
      (value "CONNECTOR-HEADER-2X2P2X2P-2.54-REVERSE")
      (footprint "eagle-import:2X2P-2.54-REVERSE")
      (libsource (lib "eagle-import") (part "CONNECTOR-HEADER-2X2P2X2P-2.54-REVERSE"))
    )
    (comp (ref "J104")
      (value "CONNECTOR-HEADER-2X2P2X2P-2.54-REVERSE")
      (footprint "eagle-import:2X2P-2.54-REVERSE")
      (libsource (lib "eagle-import") (part "CONNECTOR-HEADER-2X2P2X2P-2.54-REVERSE"))
    )
    (comp (ref "J105")
      (value "CONNECTOR-HEADER-2X2P2X2P-2.54-REVERSE")
      (footprint "eagle-import:2X2P-2.54-REVERSE")
      (libsource (lib "eagle-import") (part "CONNECTOR-HEADER-2X2P2X2P-2.54-REVERSE"))
    )
    (comp (ref "J106")
      (value "CONNECTOR-HEADER-2X2P2X2P-2.54-REVERSE")
      (footprint "eagle-import:2X2P-2.54-REVERSE")
      (libsource (lib "eagle-import") (part "CONNECTOR-HEADER-2X2P2X2P-2.54-REVERSE"))
    )
    (comp (ref "J107")
      (value "CONNECTOR-HEADER-2X2P2X2P-2.54-REVERSE")
      (footprint "eagle-import:2X2P-2.54-REVERSE")
      (libsource (lib "eagle-import") (part "CONNECTOR-HEADER-2X2P2X2P-2.54-REVERSE"))
    )
    (comp (ref "J108")
      (value "CONNECTOR-HEADER-2X2P2X2P-2.54-REVERSE")
      (footprint "eagle-import:2X2P-2.54-REVERSE")
      (libsource (lib "eagle-import") (part "CONNECTOR-HEADER-2X2P2X2P-2.54-REVERSE"))
    )
    (comp (ref "J109")
      (value "CONNECTOR-HEADER-2X2P2X2P-2.54-REVERSE")
      (footprint "eagle-import:2X2P-2.54-REVERSE")
      (libsource (lib "eagle-import") (part "CONNECTOR-HEADER-2X2P2X2P-2.54-REVERSE"))
    )
    (comp (ref "J110")
      (value "CONNECTOR-HEADER-2X2P2X2P-2.54-REVERSE")
      (footprint "eagle-import:2X2P-2.54-REVERSE")
      (libsource (lib "eagle-import") (part "CONNECTOR-HEADER-2X2P2X2P-2.54-REVERSE"))
    )
    (comp (ref "J111")
      (value "CONNECTOR-HEADER-2X2P2X2P-2.54-REVERSE")
      (footprint "eagle-import:2X2P-2.54-REVERSE")
      (libsource (lib "eagle-import") (part "CONNECTOR-HEADER-2X2P2X2P-2.54-REVERSE"))
    )
    (comp (ref "J112")
      (value "CONNECTOR-HEADER-2X2P2X2P-2.54-REVERSE")
      (footprint "eagle-import:2X2P-2.54-REVERSE")
      (libsource (lib "eagle-import") (part "CONNECTOR-HEADER-2X2P2X2P-2.54-REVERSE"))
    )
    (comp (ref "J113")
      (value "CONNECTOR-HEADER-2X2P2X2P-2.54-REVERSE")
      (footprint "eagle-import:2X2P-2.54-REVERSE")
      (libsource (lib "eagle-import") (part "CONNECTOR-HEADER-2X2P2X2P-2.54-REVERSE"))
    )
    (comp (ref "J114")
      (value "CONNECTOR-HEADER-2X2P2X2P-2.54-REVERSE")
      (footprint "eagle-import:2X2P-2.54-REVERSE")
      (libsource (lib "eagle-import") (part "CONNECTOR-HEADER-2X2P2X2P-2.54-REVERSE"))
    )
    (comp (ref "J115")
      (value "CONNECTOR-HEADER-2X2P2X2P-2.54-REVERSE")
      (footprint "eagle-import:2X2P-2.54-REVERSE")
      (libsource (lib "eagle-import") (part "CONNECTOR-HEADER-2X2P2X2P-2.54-REVERSE"))
    )
    (comp (ref "J116")
      (value "CONNECTOR-HEADER-2X2P2X2P-2.54-REVERSE")
      (footprint "eagle-import:2X2P-2.54-REVERSE")
      (libsource (lib "eagle-import") (part "CONNECTOR-HEADER-2X2P2X2P-2.54-REVERSE"))
    )
    (comp (ref "J117")
      (value "CONNECTOR-HEADER-2X2P2X2P-2.54-REVERSE")
      (footprint "eagle-import:2X2P-2.54-REVERSE")
      (libsource (lib "eagle-import") (part "CONNECTOR-HEADER-2X2P2X2P-2.54-REVERSE"))
    )
    (comp (ref "J118")
      (value "CONNECTOR-HEADER-2X2P2X2P-2.54-REVERSE")
      (footprint "eagle-import:2X2P-2.54-REVERSE")
      (libsource (lib "eagle-import") (part "CONNECTOR-HEADER-2X2P2X2P-2.54-REVERSE"))
    )
    (comp (ref "J119")
      (value "CONNECTOR-HEADER-2X2P2X2P-2.54-REVERSE")
      (footprint "eagle-import:2X2P-2.54-REVERSE")
      (libsource (lib "eagle-import") (part "CONNECTOR-HEADER-2X2P2X2P-2.54-REVERSE"))
    )
    (comp (ref "J120")
      (value "CONNECTOR-HEADER-2X2P2X2P-2.54-REVERSE")
      (footprint "eagle-import:2X2P-2.54-REVERSE")
      (libsource (lib "eagle-import") (part "CONNECTOR-HEADER-2X2P2X2P-2.54-REVERSE"))
    )
    (comp (ref "J121")
      (value "CONNECTOR-HEADER-2X2P2X2P-2.54-REVERSE")
      (footprint "eagle-import:2X2P-2.54-REVERSE")
      (libsource (lib "eagle-import") (part "CONNECTOR-HEADER-2X2P2X2P-2.54-REVERSE"))
    )
    (comp (ref "J122")
      (value "CONNECTOR-HEADER-2X2P2X2P-2.54-REVERSE")
      (footprint "eagle-import:2X2P-2.54-REVERSE")
      (libsource (lib "eagle-import") (part "CONNECTOR-HEADER-2X2P2X2P-2.54-REVERSE"))
    )
    (comp (ref "J123")
      (value "CONNECTOR-HEADER-2X2P2X2P-2.54-REVERSE")
      (footprint "eagle-import:2X2P-2.54-REVERSE")
      (libsource (lib "eagle-import") (part "CONNECTOR-HEADER-2X2P2X2P-2.54-REVERSE"))
    )
    (comp (ref "J124")
      (value "CONNECTOR-HEADER-2X2P2X2P-2.54-REVERSE")
      (footprint "eagle-import:2X2P-2.54-REVERSE")
      (libsource (lib "eagle-import") (part "CONNECTOR-HEADER-2X2P2X2P-2.54-REVERSE"))
    )
    (comp (ref "J125")
      (value "CONNECTOR-HEADER-2X2P2X2P-2.54-REVERSE")
      (footprint "eagle-import:2X2P-2.54-REVERSE")
      (libsource (lib "eagle-import") (part "CONNECTOR-HEADER-2X2P2X2P-2.54-REVERSE"))
    )
    (comp (ref "J126")
      (value "CONNECTOR-HEADER-2X2P2X2P-2.54-REVERSE")
      (footprint "eagle-import:2X2P-2.54-REVERSE")
      (libsource (lib "eagle-import") (part "CONNECTOR-HEADER-2X2P2X2P-2.54-REVERSE"))
    )
    (comp (ref "J127")
      (value "CONNECTOR-HEADER-2X2P2X2P-2.54-REVERSE")
      (footprint "eagle-import:2X2P-2.54-REVERSE")
      (libsource (lib "eagle-import") (part "CONNECTOR-HEADER-2X2P2X2P-2.54-REVERSE"))
    )
    (comp (ref "J128")
      (value "CONNECTOR-HEADER-2X2P2X2P-2.54-REVERSE")
      (footprint "eagle-import:2X2P-2.54-REVERSE")
      (libsource (lib "eagle-import") (part "CONNECTOR-HEADER-2X2P2X2P-2.54-REVERSE"))
    )
    (comp (ref "J129")
      (value "CONNECTOR-HEADER-2X2P2X2P-2.54-REVERSE")
      (footprint "eagle-import:2X2P-2.54-REVERSE")
      (libsource (lib "eagle-import") (part "CONNECTOR-HEADER-2X2P2X2P-2.54-REVERSE"))
    )
    (comp (ref "J130")
      (value "CONNECTOR-HEADER-2X2P2X2P-2.54-REVERSE")
      (footprint "eagle-import:2X2P-2.54-REVERSE")
      (libsource (lib "eagle-import") (part "CONNECTOR-HEADER-2X2P2X2P-2.54-REVERSE"))
    )
    (comp (ref "J131")
      (value "CONNECTOR-HEADER-2X2P2X2P-2.54-REVERSE")
      (footprint "eagle-import:2X2P-2.54-REVERSE")
      (libsource (lib "eagle-import") (part "CONNECTOR-HEADER-2X2P2X2P-2.54-REVERSE"))
    )
    (comp (ref "J132")
      (value "CONNECTOR-HEADER-2X2P2X2P-2.54-REVERSE")
      (footprint "eagle-import:2X2P-2.54-REVERSE")
      (libsource (lib "eagle-import") (part "CONNECTOR-HEADER-2X2P2X2P-2.54-REVERSE"))
    )
    (comp (ref "J133")
      (value "CONNECTOR-HEADER-2X2P2X2P-2.54-REVERSE")
      (footprint "eagle-import:2X2P-2.54-REVERSE")
      (libsource (lib "eagle-import") (part "CONNECTOR-HEADER-2X2P2X2P-2.54-REVERSE"))
    )
    (comp (ref "J134")
      (value "CONNECTOR-HEADER-2X2P2X2P-2.54-REVERSE")
      (footprint "eagle-import:2X2P-2.54-REVERSE")
      (libsource (lib "eagle-import") (part "CONNECTOR-HEADER-2X2P2X2P-2.54-REVERSE"))
    )
    (comp (ref "J135")
      (value "CONNECTOR-HEADER-2X2P2X2P-2.54-REVERSE")
      (footprint "eagle-import:2X2P-2.54-REVERSE")
      (libsource (lib "eagle-import") (part "CONNECTOR-HEADER-2X2P2X2P-2.54-REVERSE"))
    )
    (comp (ref "J136")
      (value "CONNECTOR-HEADER-2X2P2X2P-2.54-REVERSE")
      (footprint "eagle-import:2X2P-2.54-REVERSE")
      (libsource (lib "eagle-import") (part "CONNECTOR-HEADER-2X2P2X2P-2.54-REVERSE"))
    )
    (comp (ref "J137")
      (value "CONNECTOR-HEADER-2X2P2X2P-2.54-REVERSE")
      (footprint "eagle-import:2X2P-2.54-REVERSE")
      (libsource (lib "eagle-import") (part "CONNECTOR-HEADER-2X2P2X2P-2.54-REVERSE"))
    )
    (comp (ref "J138")
      (value "CONNECTOR-HEADER-2X2P2X2P-2.54-REVERSE")
      (footprint "eagle-import:2X2P-2.54-REVERSE")
      (libsource (lib "eagle-import") (part "CONNECTOR-HEADER-2X2P2X2P-2.54-REVERSE"))
    )
    (comp (ref "J139")
      (value "CONNECTOR-HEADER-2X2P2X2P-2.54-REVERSE")
      (footprint "eagle-import:2X2P-2.54-REVERSE")
      (libsource (lib "eagle-import") (part "CONNECTOR-HEADER-2X2P2X2P-2.54-REVERSE"))
    )
    (comp (ref "J140")
      (value "CONNECTOR-HEADER-2X2P2X2P-2.54-REVERSE")
      (footprint "eagle-import:2X2P-2.54-REVERSE")
      (libsource (lib "eagle-import") (part "CONNECTOR-HEADER-2X2P2X2P-2.54-REVERSE"))
    )
    (comp (ref "J141")
      (value "CONNECTOR-HEADER-2X2P2X2P-2.54-REVERSE")
      (footprint "eagle-import:2X2P-2.54-REVERSE")
      (libsource (lib "eagle-import") (part "CONNECTOR-HEADER-2X2P2X2P-2.54-REVERSE"))
    )
    (comp (ref "J142")
      (value "CONNECTOR-HEADER-2X2P2X2P-2.54-REVERSE")
      (footprint "eagle-import:2X2P-2.54-REVERSE")
      (libsource (lib "eagle-import") (part "CONNECTOR-HEADER-2X2P2X2P-2.54-REVERSE"))
    )
    (comp (ref "J143")
      (value "CONNECTOR-HEADER-2X2P2X2P-2.54-REVERSE")
      (footprint "eagle-import:2X2P-2.54-REVERSE")
      (libsource (lib "eagle-import") (part "CONNECTOR-HEADER-2X2P2X2P-2.54-REVERSE"))
    )
    (comp (ref "J144")
      (value "CONNECTOR-HEADER-2X2P2X2P-2.54-REVERSE")
      (footprint "eagle-import:2X2P-2.54-REVERSE")
      (libsource (lib "eagle-import") (part "CONNECTOR-HEADER-2X2P2X2P-2.54-REVERSE"))
    )
    (comp (ref "J145")
      (value "CONNECTOR-HEADER-2X2P2X2P-2.54-REVERSE")
      (footprint "eagle-import:2X2P-2.54-REVERSE")
      (libsource (lib "eagle-import") (part "CONNECTOR-HEADER-2X2P2X2P-2.54-REVERSE"))
    )
    (comp (ref "J146")
      (value "CONNECTOR-HEADER-2X2P2X2P-2.54-REVERSE")
      (footprint "eagle-import:2X2P-2.54-REVERSE")
      (libsource (lib "eagle-import") (part "CONNECTOR-HEADER-2X2P2X2P-2.54-REVERSE"))
    )
    (comp (ref "J147")
      (value "CONNECTOR-HEADER-2X2P2X2P-2.54-REVERSE")
      (footprint "eagle-import:2X2P-2.54-REVERSE")
      (libsource (lib "eagle-import") (part "CONNECTOR-HEADER-2X2P2X2P-2.54-REVERSE"))
    )
    (comp (ref "J148")
      (value "CONNECTOR-HEADER-2X2P2X2P-2.54-REVERSE")
      (footprint "eagle-import:2X2P-2.54-REVERSE")
      (libsource (lib "eagle-import") (part "CONNECTOR-HEADER-2X2P2X2P-2.54-REVERSE"))
    )
    (comp (ref "J149")
      (value "CONNECTOR-HEADER-2X2P2X2P-2.54-REVERSE")
      (footprint "eagle-import:2X2P-2.54-REVERSE")
      (libsource (lib "eagle-import") (part "CONNECTOR-HEADER-2X2P2X2P-2.54-REVERSE"))
    )
    (comp (ref "J150")
      (value "CONNECTOR-HEADER-2X2P2X2P-2.54-REVERSE")
      (footprint "eagle-import:2X2P-2.54-REVERSE")
      (libsource (lib "eagle-import") (part "CONNECTOR-HEADER-2X2P2X2P-2.54-REVERSE"))
    )
    (comp (ref "J151")
      (value "CONNECTOR-HEADER-2X2P2X2P-2.54-REVERSE")
      (footprint "eagle-import:2X2P-2.54-REVERSE")
      (libsource (lib "eagle-import") (part "CONNECTOR-HEADER-2X2P2X2P-2.54-REVERSE"))
    )
    (comp (ref "J152")
      (value "CONNECTOR-HEADER-2X2P2X2P-2.54-REVERSE")
      (footprint "eagle-import:2X2P-2.54-REVERSE")
      (libsource (lib "eagle-import") (part "CONNECTOR-HEADER-2X2P2X2P-2.54-REVERSE"))
    )
    (comp (ref "J153")
      (value "CONNECTOR-HEADER-2X2P2X2P-2.54-REVERSE")
      (footprint "eagle-import:2X2P-2.54-REVERSE")
      (libsource (lib "eagle-import") (part "CONNECTOR-HEADER-2X2P2X2P-2.54-REVERSE"))
    )
    (comp (ref "J154")
      (value "CONNECTOR-HEADER-2X2P2X2P-2.54-REVERSE")
      (footprint "eagle-import:2X2P-2.54-REVERSE")
      (libsource (lib "eagle-import") (part "CONNECTOR-HEADER-2X2P2X2P-2.54-REVERSE"))
    )
    (comp (ref "J155")
      (value "CONNECTOR-HEADER-2X2P2X2P-2.54-REVERSE")
      (footprint "eagle-import:2X2P-2.54-REVERSE")
      (libsource (lib "eagle-import") (part "CONNECTOR-HEADER-2X2P2X2P-2.54-REVERSE"))
    )
    (comp (ref "J156")
      (value "CONNECTOR-HEADER-2X2P2X2P-2.54-REVERSE")
      (footprint "eagle-import:2X2P-2.54-REVERSE")
      (libsource (lib "eagle-import") (part "CONNECTOR-HEADER-2X2P2X2P-2.54-REVERSE"))
    )
    (comp (ref "J157")
      (value "CONNECTOR-HEADER-2X2P2X2P-2.54-REVERSE")
      (footprint "eagle-import:2X2P-2.54-REVERSE")
      (libsource (lib "eagle-import") (part "CONNECTOR-HEADER-2X2P2X2P-2.54-REVERSE"))
    )
    (comp (ref "J158")
      (value "CONNECTOR-HEADER-2X2P2X2P-2.54-REVERSE")
      (footprint "eagle-import:2X2P-2.54-REVERSE")
      (libsource (lib "eagle-import") (part "CONNECTOR-HEADER-2X2P2X2P-2.54-REVERSE"))
    )
    (comp (ref "J159")
      (value "CONNECTOR-HEADER-2X2P2X2P-2.54-REVERSE")
      (footprint "eagle-import:2X2P-2.54-REVERSE")
      (libsource (lib "eagle-import") (part "CONNECTOR-HEADER-2X2P2X2P-2.54-REVERSE"))
    )
    (comp (ref "J160")
      (value "CONNECTOR-HEADER-2X2P2X2P-2.54-REVERSE")
      (footprint "eagle-import:2X2P-2.54-REVERSE")
      (libsource (lib "eagle-import") (part "CONNECTOR-HEADER-2X2P2X2P-2.54-REVERSE"))
    )
    (comp (ref "J161")
      (value "CONNECTOR-HEADER-2X2P2X2P-2.54-REVERSE")
      (footprint "eagle-import:2X2P-2.54-REVERSE")
      (libsource (lib "eagle-import") (part "CONNECTOR-HEADER-2X2P2X2P-2.54-REVERSE"))
    )
    (comp (ref "J162")
      (value "CONNECTOR-HEADER-2X2P2X2P-2.54-REVERSE")
      (footprint "eagle-import:2X2P-2.54-REVERSE")
      (libsource (lib "eagle-import") (part "CONNECTOR-HEADER-2X2P2X2P-2.54-REVERSE"))
    )
    (comp (ref "J163")
      (value "CONNECTOR-HEADER-2X2P2X2P-2.54-REVERSE")
      (footprint "eagle-import:2X2P-2.54-REVERSE")
      (libsource (lib "eagle-import") (part "CONNECTOR-HEADER-2X2P2X2P-2.54-REVERSE"))
    )
    (comp (ref "J164")
      (value "CONNECTOR-HEADER-2X2P2X2P-2.54-REVERSE")
      (footprint "eagle-import:2X2P-2.54-REVERSE")
      (libsource (lib "eagle-import") (part "CONNECTOR-HEADER-2X2P2X2P-2.54-REVERSE"))
    )
    (comp (ref "J165")
      (value "CONNECTOR-HEADER-2X2P2X2P-2.54-REVERSE")
      (footprint "eagle-import:2X2P-2.54-REVERSE")
      (libsource (lib "eagle-import") (part "CONNECTOR-HEADER-2X2P2X2P-2.54-REVERSE"))
    )
    (comp (ref "J166")
      (value "CONNECTOR-HEADER-2X2P2X2P-2.54-REVERSE")
      (footprint "eagle-import:2X2P-2.54-REVERSE")
      (libsource (lib "eagle-import") (part "CONNECTOR-HEADER-2X2P2X2P-2.54-REVERSE"))
    )
    (comp (ref "J167")
      (value "CONNECTOR-HEADER-2X2P2X2P-2.54-REVERSE")
      (footprint "eagle-import:2X2P-2.54-REVERSE")
      (libsource (lib "eagle-import") (part "CONNECTOR-HEADER-2X2P2X2P-2.54-REVERSE"))
    )
    (comp (ref "J168")
      (value "CONNECTOR-HEADER-2X2P2X2P-2.54-REVERSE")
      (footprint "eagle-import:2X2P-2.54-REVERSE")
      (libsource (lib "eagle-import") (part "CONNECTOR-HEADER-2X2P2X2P-2.54-REVERSE"))
    )
    (comp (ref "J169")
      (value "CONNECTOR-HEADER-2X2P2X2P-2.54-REVERSE")
      (footprint "eagle-import:2X2P-2.54-REVERSE")
      (libsource (lib "eagle-import") (part "CONNECTOR-HEADER-2X2P2X2P-2.54-REVERSE"))
    )
    (comp (ref "J170")
      (value "CONNECTOR-HEADER-2X2P2X2P-2.54-REVERSE")
      (footprint "eagle-import:2X2P-2.54-REVERSE")
      (libsource (lib "eagle-import") (part "CONNECTOR-HEADER-2X2P2X2P-2.54-REVERSE"))
    )
    (comp (ref "J171")
      (value "CONNECTOR-HEADER-2X2P2X2P-2.54-REVERSE")
      (footprint "eagle-import:2X2P-2.54-REVERSE")
      (libsource (lib "eagle-import") (part "CONNECTOR-HEADER-2X2P2X2P-2.54-REVERSE"))
    )
    (comp (ref "J172")
      (value "CONNECTOR-HEADER-2X2P2X2P-2.54-REVERSE")
      (footprint "eagle-import:2X2P-2.54-REVERSE")
      (libsource (lib "eagle-import") (part "CONNECTOR-HEADER-2X2P2X2P-2.54-REVERSE"))
    )
    (comp (ref "J173")
      (value "CONNECTOR-HEADER-2X2P2X2P-2.54-REVERSE")
      (footprint "eagle-import:2X2P-2.54-REVERSE")
      (libsource (lib "eagle-import") (part "CONNECTOR-HEADER-2X2P2X2P-2.54-REVERSE"))
    )
    (comp (ref "J174")
      (value "CONNECTOR-HEADER-2X2P2X2P-2.54-REVERSE")
      (footprint "eagle-import:2X2P-2.54-REVERSE")
      (libsource (lib "eagle-import") (part "CONNECTOR-HEADER-2X2P2X2P-2.54-REVERSE"))
    )
    (comp (ref "J175")
      (value "CONNECTOR-HEADER-2X2P2X2P-2.54-REVERSE")
      (footprint "eagle-import:2X2P-2.54-REVERSE")
      (libsource (lib "eagle-import") (part "CONNECTOR-HEADER-2X2P2X2P-2.54-REVERSE"))
    )
    (comp (ref "J176")
      (value "CONNECTOR-HEADER-2X2P2X2P-2.54-REVERSE")
      (footprint "eagle-import:2X2P-2.54-REVERSE")
      (libsource (lib "eagle-import") (part "CONNECTOR-HEADER-2X2P2X2P-2.54-REVERSE"))
    )
    (comp (ref "J177")
      (value "CONNECTOR-HEADER-2X2P2X2P-2.54-REVERSE")
      (footprint "eagle-import:2X2P-2.54-REVERSE")
      (libsource (lib "eagle-import") (part "CONNECTOR-HEADER-2X2P2X2P-2.54-REVERSE"))
    )
    (comp (ref "J178")
      (value "CONNECTOR-HEADER-2X2P2X2P-2.54-REVERSE")
      (footprint "eagle-import:2X2P-2.54-REVERSE")
      (libsource (lib "eagle-import") (part "CONNECTOR-HEADER-2X2P2X2P-2.54-REVERSE"))
    )
    (comp (ref "J179")
      (value "CONNECTOR-HEADER-2X2P2X2P-2.54-REVERSE")
      (footprint "eagle-import:2X2P-2.54-REVERSE")
      (libsource (lib "eagle-import") (part "CONNECTOR-HEADER-2X2P2X2P-2.54-REVERSE"))
    )
    (comp (ref "J180")
      (value "CONNECTOR-HEADER-2X2P2X2P-2.54-REVERSE")
      (footprint "eagle-import:2X2P-2.54-REVERSE")
      (libsource (lib "eagle-import") (part "CONNECTOR-HEADER-2X2P2X2P-2.54-REVERSE"))
    )
    (comp (ref "J181")
      (value "CONNECTOR-HEADER-2X2P2X2P-2.54-REVERSE")
      (footprint "eagle-import:2X2P-2.54-REVERSE")
      (libsource (lib "eagle-import") (part "CONNECTOR-HEADER-2X2P2X2P-2.54-REVERSE"))
    )
    (comp (ref "J182")
      (value "CONNECTOR-HEADER-2X2P2X2P-2.54-REVERSE")
      (footprint "eagle-import:2X2P-2.54-REVERSE")
      (libsource (lib "eagle-import") (part "CONNECTOR-HEADER-2X2P2X2P-2.54-REVERSE"))
    )
    (comp (ref "J183")
      (value "CONNECTOR-HEADER-2X2P2X2P-2.54-REVERSE")
      (footprint "eagle-import:2X2P-2.54-REVERSE")
      (libsource (lib "eagle-import") (part "CONNECTOR-HEADER-2X2P2X2P-2.54-REVERSE"))
    )
    (comp (ref "J184")
      (value "CONNECTOR-HEADER-2X2P2X2P-2.54-REVERSE")
      (footprint "eagle-import:2X2P-2.54-REVERSE")
      (libsource (lib "eagle-import") (part "CONNECTOR-HEADER-2X2P2X2P-2.54-REVERSE"))
    )
    (comp (ref "J185")
      (value "CONNECTOR-HEADER-2X2P2X2P-2.54-REVERSE")
      (footprint "eagle-import:2X2P-2.54-REVERSE")
      (libsource (lib "eagle-import") (part "CONNECTOR-HEADER-2X2P2X2P-2.54-REVERSE"))
    )
    (comp (ref "J186")
      (value "CONNECTOR-HEADER-2X2P2X2P-2.54-REVERSE")
      (footprint "eagle-import:2X2P-2.54-REVERSE")
      (libsource (lib "eagle-import") (part "CONNECTOR-HEADER-2X2P2X2P-2.54-REVERSE"))
    )
    (comp (ref "J187")
      (value "CONNECTOR-HEADER-2X2P2X2P-2.54-REVERSE")
      (footprint "eagle-import:2X2P-2.54-REVERSE")
      (libsource (lib "eagle-import") (part "CONNECTOR-HEADER-2X2P2X2P-2.54-REVERSE"))
    )
    (comp (ref "J188")
      (value "CONNECTOR-HEADER-2X2P2X2P-2.54-REVERSE")
      (footprint "eagle-import:2X2P-2.54-REVERSE")
      (libsource (lib "eagle-import") (part "CONNECTOR-HEADER-2X2P2X2P-2.54-REVERSE"))
    )
    (comp (ref "J189")
      (value "CONNECTOR-HEADER-2X2P2X2P-2.54-REVERSE")
      (footprint "eagle-import:2X2P-2.54-REVERSE")
      (libsource (lib "eagle-import") (part "CONNECTOR-HEADER-2X2P2X2P-2.54-REVERSE"))
    )
    (comp (ref "J190")
      (value "CONNECTOR-HEADER-2X2P2X2P-2.54-REVERSE")
      (footprint "eagle-import:2X2P-2.54-REVERSE")
      (libsource (lib "eagle-import") (part "CONNECTOR-HEADER-2X2P2X2P-2.54-REVERSE"))
    )
    (comp (ref "J191")
      (value "CONNECTOR-HEADER-2X2P2X2P-2.54-REVERSE")
      (footprint "eagle-import:2X2P-2.54-REVERSE")
      (libsource (lib "eagle-import") (part "CONNECTOR-HEADER-2X2P2X2P-2.54-REVERSE"))
    )
    (comp (ref "J192")
      (value "CONNECTOR-HEADER-2X2P2X2P-2.54-REVERSE")
      (footprint "eagle-import:2X2P-2.54-REVERSE")
      (libsource (lib "eagle-import") (part "CONNECTOR-HEADER-2X2P2X2P-2.54-REVERSE"))
    )
    (comp (ref "J193")
      (value "CONNECTOR-HEADER-2X2P2X2P-2.54-REVERSE")
      (footprint "eagle-import:2X2P-2.54-REVERSE")
      (libsource (lib "eagle-import") (part "CONNECTOR-HEADER-2X2P2X2P-2.54-REVERSE"))
    )
    (comp (ref "J194")
      (value "CONNECTOR-HEADER-2X2P2X2P-2.54-REVERSE")
      (footprint "eagle-import:2X2P-2.54-REVERSE")
      (libsource (lib "eagle-import") (part "CONNECTOR-HEADER-2X2P2X2P-2.54-REVERSE"))
    )
    (comp (ref "J195")
      (value "CONNECTOR-HEADER-2X2P2X2P-2.54-REVERSE")
      (footprint "eagle-import:2X2P-2.54-REVERSE")
      (libsource (lib "eagle-import") (part "CONNECTOR-HEADER-2X2P2X2P-2.54-REVERSE"))
    )
    (comp (ref "J196")
      (value "CONNECTOR-HEADER-2X2P2X2P-2.54-REVERSE")
      (footprint "eagle-import:2X2P-2.54-REVERSE")
      (libsource (lib "eagle-import") (part "CONNECTOR-HEADER-2X2P2X2P-2.54-REVERSE"))
    )
    (comp (ref "J197")
      (value "CONNECTOR-HEADER-2X2P2X2P-2.54-REVERSE")
      (footprint "eagle-import:2X2P-2.54-REVERSE")
      (libsource (lib "eagle-import") (part "CONNECTOR-HEADER-2X2P2X2P-2.54-REVERSE"))
    )
    (comp (ref "J198")
      (value "CONNECTOR-HEADER-2X2P2X2P-2.54-REVERSE")
      (footprint "eagle-import:2X2P-2.54-REVERSE")
      (libsource (lib "eagle-import") (part "CONNECTOR-HEADER-2X2P2X2P-2.54-REVERSE"))
    )
    (comp (ref "J199")
      (value "CONNECTOR-HEADER-2X2P2X2P-2.54-REVERSE")
      (footprint "eagle-import:2X2P-2.54-REVERSE")
      (libsource (lib "eagle-import") (part "CONNECTOR-HEADER-2X2P2X2P-2.54-REVERSE"))
    )
    (comp (ref "J200")
      (value "CONNECTOR-HEADER-2X2P2X2P-2.54-REVERSE")
      (footprint "eagle-import:2X2P-2.54-REVERSE")
      (libsource (lib "eagle-import") (part "CONNECTOR-HEADER-2X2P2X2P-2.54-REVERSE"))
    )
    (comp (ref "J201")
      (value "CONNECTOR-HEADER-2X2P2X2P-2.54-REVERSE")
      (footprint "eagle-import:2X2P-2.54-REVERSE")
      (libsource (lib "eagle-import") (part "CONNECTOR-HEADER-2X2P2X2P-2.54-REVERSE"))
    )
    (comp (ref "J202")
      (value "CONNECTOR-HEADER-2X2P2X2P-2.54-REVERSE")
      (footprint "eagle-import:2X2P-2.54-REVERSE")
      (libsource (lib "eagle-import") (part "CONNECTOR-HEADER-2X2P2X2P-2.54-REVERSE"))
    )
    (comp (ref "J203")
      (value "CONNECTOR-HEADER-2X2P2X2P-2.54-REVERSE")
      (footprint "eagle-import:2X2P-2.54-REVERSE")
      (libsource (lib "eagle-import") (part "CONNECTOR-HEADER-2X2P2X2P-2.54-REVERSE"))
    )
    (comp (ref "J204")
      (value "CONNECTOR-HEADER-2X2P2X2P-2.54-REVERSE")
      (footprint "eagle-import:2X2P-2.54-REVERSE")
      (libsource (lib "eagle-import") (part "CONNECTOR-HEADER-2X2P2X2P-2.54-REVERSE"))
    )
    (comp (ref "J205")
      (value "CONNECTOR-HEADER-2X2P2X2P-2.54-REVERSE")
      (footprint "eagle-import:2X2P-2.54-REVERSE")
      (libsource (lib "eagle-import") (part "CONNECTOR-HEADER-2X2P2X2P-2.54-REVERSE"))
    )
    (comp (ref "J206")
      (value "CONNECTOR-HEADER-2X2P2X2P-2.54-REVERSE")
      (footprint "eagle-import:2X2P-2.54-REVERSE")
      (libsource (lib "eagle-import") (part "CONNECTOR-HEADER-2X2P2X2P-2.54-REVERSE"))
    )
    (comp (ref "J207")
      (value "CONNECTOR-HEADER-2X2P2X2P-2.54-REVERSE")
      (footprint "eagle-import:2X2P-2.54-REVERSE")
      (libsource (lib "eagle-import") (part "CONNECTOR-HEADER-2X2P2X2P-2.54-REVERSE"))
    )
    (comp (ref "J208")
      (value "CONNECTOR-HEADER-2X2P2X2P-2.54-REVERSE")
      (footprint "eagle-import:2X2P-2.54-REVERSE")
      (libsource (lib "eagle-import") (part "CONNECTOR-HEADER-2X2P2X2P-2.54-REVERSE"))
    )
    (comp (ref "J209")
      (value "CONNECTOR-HEADER-2X2P2X2P-2.54-REVERSE")
      (footprint "eagle-import:2X2P-2.54-REVERSE")
      (libsource (lib "eagle-import") (part "CONNECTOR-HEADER-2X2P2X2P-2.54-REVERSE"))
    )
    (comp (ref "J210")
      (value "CONNECTOR-HEADER-2X2P2X2P-2.54-REVERSE")
      (footprint "eagle-import:2X2P-2.54-REVERSE")
      (libsource (lib "eagle-import") (part "CONNECTOR-HEADER-2X2P2X2P-2.54-REVERSE"))
    )
    (comp (ref "J211")
      (value "CONNECTOR-HEADER-2X2P2X2P-2.54-REVERSE")
      (footprint "eagle-import:2X2P-2.54-REVERSE")
      (libsource (lib "eagle-import") (part "CONNECTOR-HEADER-2X2P2X2P-2.54-REVERSE"))
    )
    (comp (ref "J212")
      (value "CONNECTOR-HEADER-2X2P2X2P-2.54-REVERSE")
      (footprint "eagle-import:2X2P-2.54-REVERSE")
      (libsource (lib "eagle-import") (part "CONNECTOR-HEADER-2X2P2X2P-2.54-REVERSE"))
    )
    (comp (ref "J213")
      (value "CONNECTOR-HEADER-2X2P2X2P-2.54-REVERSE")
      (footprint "eagle-import:2X2P-2.54-REVERSE")
      (libsource (lib "eagle-import") (part "CONNECTOR-HEADER-2X2P2X2P-2.54-REVERSE"))
    )
    (comp (ref "J214")
      (value "CONNECTOR-HEADER-2X2P2X2P-2.54-REVERSE")
      (footprint "eagle-import:2X2P-2.54-REVERSE")
      (libsource (lib "eagle-import") (part "CONNECTOR-HEADER-2X2P2X2P-2.54-REVERSE"))
    )
    (comp (ref "J215")
      (value "CONNECTOR-HEADER-2X2P2X2P-2.54-REVERSE")
      (footprint "eagle-import:2X2P-2.54-REVERSE")
      (libsource (lib "eagle-import") (part "CONNECTOR-HEADER-2X2P2X2P-2.54-REVERSE"))
    )
    (comp (ref "J216")
      (value "CONNECTOR-HEADER-2X2P2X2P-2.54-REVERSE")
      (footprint "eagle-import:2X2P-2.54-REVERSE")
      (libsource (lib "eagle-import") (part "CONNECTOR-HEADER-2X2P2X2P-2.54-REVERSE"))
    )
    (comp (ref "J217")
      (value "CONNECTOR-HEADER-2X2P2X2P-2.54-REVERSE")
      (footprint "eagle-import:2X2P-2.54-REVERSE")
      (libsource (lib "eagle-import") (part "CONNECTOR-HEADER-2X2P2X2P-2.54-REVERSE"))
    )
    (comp (ref "J218")
      (value "CONNECTOR-HEADER-2X2P2X2P-2.54-REVERSE")
      (footprint "eagle-import:2X2P-2.54-REVERSE")
      (libsource (lib "eagle-import") (part "CONNECTOR-HEADER-2X2P2X2P-2.54-REVERSE"))
    )
    (comp (ref "J219")
      (value "CONNECTOR-HEADER-2X2P2X2P-2.54-REVERSE")
      (footprint "eagle-import:2X2P-2.54-REVERSE")
      (libsource (lib "eagle-import") (part "CONNECTOR-HEADER-2X2P2X2P-2.54-REVERSE"))
    )
    (comp (ref "J220")
      (value "CONNECTOR-HEADER-2X2P2X2P-2.54-REVERSE")
      (footprint "eagle-import:2X2P-2.54-REVERSE")
      (libsource (lib "eagle-import") (part "CONNECTOR-HEADER-2X2P2X2P-2.54-REVERSE"))
    )
    (comp (ref "J221")
      (value "CONNECTOR-HEADER-2X2P2X2P-2.54-REVERSE")
      (footprint "eagle-import:2X2P-2.54-REVERSE")
      (libsource (lib "eagle-import") (part "CONNECTOR-HEADER-2X2P2X2P-2.54-REVERSE"))
    )
    (comp (ref "J222")
      (value "CONNECTOR-HEADER-2X2P2X2P-2.54-REVERSE")
      (footprint "eagle-import:2X2P-2.54-REVERSE")
      (libsource (lib "eagle-import") (part "CONNECTOR-HEADER-2X2P2X2P-2.54-REVERSE"))
    )
    (comp (ref "J223")
      (value "CONNECTOR-HEADER-2X2P2X2P-2.54-REVERSE")
      (footprint "eagle-import:2X2P-2.54-REVERSE")
      (libsource (lib "eagle-import") (part "CONNECTOR-HEADER-2X2P2X2P-2.54-REVERSE"))
    )
    (comp (ref "J224")
      (value "CONNECTOR-HEADER-2X2P2X2P-2.54-REVERSE")
      (footprint "eagle-import:2X2P-2.54-REVERSE")
      (libsource (lib "eagle-import") (part "CONNECTOR-HEADER-2X2P2X2P-2.54-REVERSE"))
    )
    (comp (ref "J225")
      (value "CONNECTOR-HEADER-2X2P2X2P-2.54-REVERSE")
      (footprint "eagle-import:2X2P-2.54-REVERSE")
      (libsource (lib "eagle-import") (part "CONNECTOR-HEADER-2X2P2X2P-2.54-REVERSE"))
    )
    (comp (ref "J226")
      (value "CONNECTOR-HEADER-2X2P2X2P-2.54-REVERSE")
      (footprint "eagle-import:2X2P-2.54-REVERSE")
      (libsource (lib "eagle-import") (part "CONNECTOR-HEADER-2X2P2X2P-2.54-REVERSE"))
    )
    (comp (ref "J227")
      (value "CONNECTOR-HEADER-2X2P2X2P-2.54-REVERSE")
      (footprint "eagle-import:2X2P-2.54-REVERSE")
      (libsource (lib "eagle-import") (part "CONNECTOR-HEADER-2X2P2X2P-2.54-REVERSE"))
    )
    (comp (ref "J228")
      (value "CONNECTOR-HEADER-2X2P2X2P-2.54-REVERSE")
      (footprint "eagle-import:2X2P-2.54-REVERSE")
      (libsource (lib "eagle-import") (part "CONNECTOR-HEADER-2X2P2X2P-2.54-REVERSE"))
    )
    (comp (ref "J229")
      (value "CONNECTOR-HEADER-2X2P2X2P-2.54-REVERSE")
      (footprint "eagle-import:2X2P-2.54-REVERSE")
      (libsource (lib "eagle-import") (part "CONNECTOR-HEADER-2X2P2X2P-2.54-REVERSE"))
    )
    (comp (ref "J230")
      (value "CONNECTOR-HEADER-2X2P2X2P-2.54-REVERSE")
      (footprint "eagle-import:2X2P-2.54-REVERSE")
      (libsource (lib "eagle-import") (part "CONNECTOR-HEADER-2X2P2X2P-2.54-REVERSE"))
    )
    (comp (ref "J231")
      (value "CONNECTOR-HEADER-2X2P2X2P-2.54-REVERSE")
      (footprint "eagle-import:2X2P-2.54-REVERSE")
      (libsource (lib "eagle-import") (part "CONNECTOR-HEADER-2X2P2X2P-2.54-REVERSE"))
    )
    (comp (ref "J232")
      (value "CONNECTOR-HEADER-2X2P2X2P-2.54-REVERSE")
      (footprint "eagle-import:2X2P-2.54-REVERSE")
      (libsource (lib "eagle-import") (part "CONNECTOR-HEADER-2X2P2X2P-2.54-REVERSE"))
    )
    (comp (ref "J233")
      (value "CONNECTOR-HEADER-2X2P2X2P-2.54-REVERSE")
      (footprint "eagle-import:2X2P-2.54-REVERSE")
      (libsource (lib "eagle-import") (part "CONNECTOR-HEADER-2X2P2X2P-2.54-REVERSE"))
    )
    (comp (ref "J234")
      (value "CONNECTOR-HEADER-2X2P2X2P-2.54-REVERSE")
      (footprint "eagle-import:2X2P-2.54-REVERSE")
      (libsource (lib "eagle-import") (part "CONNECTOR-HEADER-2X2P2X2P-2.54-REVERSE"))
    )
    (comp (ref "J235")
      (value "CONNECTOR-HEADER-2X2P2X2P-2.54-REVERSE")
      (footprint "eagle-import:2X2P-2.54-REVERSE")
      (libsource (lib "eagle-import") (part "CONNECTOR-HEADER-2X2P2X2P-2.54-REVERSE"))
    )
    (comp (ref "J236")
      (value "CONNECTOR-HEADER-2X2P2X2P-2.54-REVERSE")
      (footprint "eagle-import:2X2P-2.54-REVERSE")
      (libsource (lib "eagle-import") (part "CONNECTOR-HEADER-2X2P2X2P-2.54-REVERSE"))
    )
    (comp (ref "J237")
      (value "CONNECTOR-HEADER-2X2P2X2P-2.54-REVERSE")
      (footprint "eagle-import:2X2P-2.54-REVERSE")
      (libsource (lib "eagle-import") (part "CONNECTOR-HEADER-2X2P2X2P-2.54-REVERSE"))
    )
    (comp (ref "J238")
      (value "CONNECTOR-HEADER-2X2P2X2P-2.54-REVERSE")
      (footprint "eagle-import:2X2P-2.54-REVERSE")
      (libsource (lib "eagle-import") (part "CONNECTOR-HEADER-2X2P2X2P-2.54-REVERSE"))
    )
    (comp (ref "J239")
      (value "CONNECTOR-HEADER-2X2P2X2P-2.54-REVERSE")
      (footprint "eagle-import:2X2P-2.54-REVERSE")
      (libsource (lib "eagle-import") (part "CONNECTOR-HEADER-2X2P2X2P-2.54-REVERSE"))
    )
    (comp (ref "J240")
      (value "CONNECTOR-HEADER-2X2P2X2P-2.54-REVERSE")
      (footprint "eagle-import:2X2P-2.54-REVERSE")
      (libsource (lib "eagle-import") (part "CONNECTOR-HEADER-2X2P2X2P-2.54-REVERSE"))
    )
    (comp (ref "J241")
      (value "CONNECTOR-HEADER-2X2P2X2P-2.54-REVERSE")
      (footprint "eagle-import:2X2P-2.54-REVERSE")
      (libsource (lib "eagle-import") (part "CONNECTOR-HEADER-2X2P2X2P-2.54-REVERSE"))
    )
    (comp (ref "J242")
      (value "CONNECTOR-HEADER-2X2P2X2P-2.54-REVERSE")
      (footprint "eagle-import:2X2P-2.54-REVERSE")
      (libsource (lib "eagle-import") (part "CONNECTOR-HEADER-2X2P2X2P-2.54-REVERSE"))
    )
    (comp (ref "J243")
      (value "CONNECTOR-HEADER-2X2P2X2P-2.54-REVERSE")
      (footprint "eagle-import:2X2P-2.54-REVERSE")
      (libsource (lib "eagle-import") (part "CONNECTOR-HEADER-2X2P2X2P-2.54-REVERSE"))
    )
    (comp (ref "J244")
      (value "CONNECTOR-HEADER-2X2P2X2P-2.54-REVERSE")
      (footprint "eagle-import:2X2P-2.54-REVERSE")
      (libsource (lib "eagle-import") (part "CONNECTOR-HEADER-2X2P2X2P-2.54-REVERSE"))
    )
    (comp (ref "J245")
      (value "CONNECTOR-HEADER-2X2P2X2P-2.54-REVERSE")
      (footprint "eagle-import:2X2P-2.54-REVERSE")
      (libsource (lib "eagle-import") (part "CONNECTOR-HEADER-2X2P2X2P-2.54-REVERSE"))
    )
    (comp (ref "J246")
      (value "CONNECTOR-HEADER-2X2P2X2P-2.54-REVERSE")
      (footprint "eagle-import:2X2P-2.54-REVERSE")
      (libsource (lib "eagle-import") (part "CONNECTOR-HEADER-2X2P2X2P-2.54-REVERSE"))
    )
    (comp (ref "J247")
      (value "CONNECTOR-HEADER-2X2P2X2P-2.54-REVERSE")
      (footprint "eagle-import:2X2P-2.54-REVERSE")
      (libsource (lib "eagle-import") (part "CONNECTOR-HEADER-2X2P2X2P-2.54-REVERSE"))
    )
    (comp (ref "J248")
      (value "CONNECTOR-HEADER-2X2P2X2P-2.54-REVERSE")
      (footprint "eagle-import:2X2P-2.54-REVERSE")
      (libsource (lib "eagle-import") (part "CONNECTOR-HEADER-2X2P2X2P-2.54-REVERSE"))
    )
    (comp (ref "J249")
      (value "CONNECTOR-HEADER-2X2P2X2P-2.54-REVERSE")
      (footprint "eagle-import:2X2P-2.54-REVERSE")
      (libsource (lib "eagle-import") (part "CONNECTOR-HEADER-2X2P2X2P-2.54-REVERSE"))
    )
    (comp (ref "J250")
      (value "CONNECTOR-HEADER-2X2P2X2P-2.54-REVERSE")
      (footprint "eagle-import:2X2P-2.54-REVERSE")
      (libsource (lib "eagle-import") (part "CONNECTOR-HEADER-2X2P2X2P-2.54-REVERSE"))
    )
    (comp (ref "J251")
      (value "CONNECTOR-HEADER-2X2P2X2P-2.54-REVERSE")
      (footprint "eagle-import:2X2P-2.54-REVERSE")
      (libsource (lib "eagle-import") (part "CONNECTOR-HEADER-2X2P2X2P-2.54-REVERSE"))
    )
    (comp (ref "J252")
      (value "CONNECTOR-HEADER-2X2P2X2P-2.54-REVERSE")
      (footprint "eagle-import:2X2P-2.54-REVERSE")
      (libsource (lib "eagle-import") (part "CONNECTOR-HEADER-2X2P2X2P-2.54-REVERSE"))
    )
    (comp (ref "J253")
      (value "CONNECTOR-HEADER-2X2P2X2P-2.54-REVERSE")
      (footprint "eagle-import:2X2P-2.54-REVERSE")
      (libsource (lib "eagle-import") (part "CONNECTOR-HEADER-2X2P2X2P-2.54-REVERSE"))
    )
    (comp (ref "J254")
      (value "CONNECTOR-HEADER-2X2P2X2P-2.54-REVERSE")
      (footprint "eagle-import:2X2P-2.54-REVERSE")
      (libsource (lib "eagle-import") (part "CONNECTOR-HEADER-2X2P2X2P-2.54-REVERSE"))
    )
    (comp (ref "J255")
      (value "CONNECTOR-HEADER-2X2P2X2P-2.54-REVERSE")
      (footprint "eagle-import:2X2P-2.54-REVERSE")
      (libsource (lib "eagle-import") (part "CONNECTOR-HEADER-2X2P2X2P-2.54-REVERSE"))
    )
    (comp (ref "J256")
      (value "CONNECTOR-HEADER-2X2P2X2P-2.54-REVERSE")
      (footprint "eagle-import:2X2P-2.54-REVERSE")
      (libsource (lib "eagle-import") (part "CONNECTOR-HEADER-2X2P2X2P-2.54-REVERSE"))
    )
    (comp (ref "JP1")
      (value "M12PTH")
      (footprint "eagle-import:1X12-SMALL-PADS")
      (libsource (lib "eagle-import") (part "M12PTH"))
    )
    (comp (ref "JP2")
      (value "M12PTH")
      (footprint "eagle-import:1X12-SMALL-PADS")
      (libsource (lib "eagle-import") (part "M12PTH"))
    )
    (comp (ref "JP3")
      (value "M12PTH")
      (footprint "eagle-import:1X12-SMALL-PADS")
      (libsource (lib "eagle-import") (part "M12PTH"))
    )
    (comp (ref "JP4")
      (value "M12PTH")
      (footprint "eagle-import:1X12-SMALL-PADS")
      (libsource (lib "eagle-import") (part "M12PTH"))
    )
    (comp (ref "JP5")
      (value "PINHD-2X4")
      (footprint "eagle-import:2X04")
      (libsource (lib "eagle-import") (part "PINHD-2X4"))
    )
    (comp (ref "ONLINE/OFFLINE")
      (value "SWITCH-2P3T-SK12D07VG3")
      (footprint "eagle-import:SWITCH-2P3T-SK12D07VG3")
      (libsource (lib "eagle-import") (part "SWITCH-2P3T-SK12D07VG3"))
    )
    (comp (ref "Q2")
      (value "FDD6637")
      (footprint "eagle-import:TO252")
      (libsource (lib "eagle-import") (part "FDD4141TO252"))
    )
    (comp (ref "Q3")
      (value "FDD6637")
      (footprint "eagle-import:TO252")
      (libsource (lib "eagle-import") (part "FDD4141TO252"))
    )
    (comp (ref "Q6")
      (value "FDD6637")
      (footprint "eagle-import:TO252")
      (libsource (lib "eagle-import") (part "FDD4141TO252"))
    )
    (comp (ref "Q8")
      (value "FDD6637")
      (footprint "eagle-import:TO252")
      (libsource (lib "eagle-import") (part "FDD4141TO252"))
    )
    (comp (ref "R3")
      (value "0.33")
      (footprint "eagle-import:RESISTOR-3W-20MM")
      (libsource (lib "eagle-import") (part "RESISTOR-3W-20MM"))
    )
    (comp (ref "R7")
      (value "0.33")
      (footprint "eagle-import:RESISTOR-3W-20MM")
      (libsource (lib "eagle-import") (part "RESISTOR-3W-20MM"))
    )
    (comp (ref "R14")
      (value "0.33")
      (footprint "eagle-import:RESISTOR-3W-20MM")
      (libsource (lib "eagle-import") (part "RESISTOR-3W-20MM"))
    )
    (comp (ref "R27")
      (value "0.33")
      (footprint "eagle-import:RESISTOR-3W-20MM")
      (libsource (lib "eagle-import") (part "RESISTOR-3W-20MM"))
    )
    (comp (ref "R28")
      (value "0.33")
      (footprint "eagle-import:RESISTOR-3W-20MM")
      (libsource (lib "eagle-import") (part "RESISTOR-3W-20MM"))
    )
    (comp (ref "R29")
      (value "0.33")
      (footprint "eagle-import:RESISTOR-3W-20MM")
      (libsource (lib "eagle-import") (part "RESISTOR-3W-20MM"))
    )
    (comp (ref "R30")
      (value "0.33")
      (footprint "eagle-import:RESISTOR-3W-20MM")
      (libsource (lib "eagle-import") (part "RESISTOR-3W-20MM"))
    )
    (comp (ref "R31")
      (value "0.33")
      (footprint "eagle-import:RESISTOR-3W-20MM")
      (libsource (lib "eagle-import") (part "RESISTOR-3W-20MM"))
    )
    (comp (ref "R32")
      (value "0.33")
      (footprint "eagle-import:RESISTOR-3W-20MM")
      (libsource (lib "eagle-import") (part "RESISTOR-3W-20MM"))
    )
    (comp (ref "R33")
      (value "0.33")
      (footprint "eagle-import:RESISTOR-3W-20MM")
      (libsource (lib "eagle-import") (part "RESISTOR-3W-20MM"))
    )
    (comp (ref "R34")
      (value "0.33")
      (footprint "eagle-import:RESISTOR-3W-20MM")
      (libsource (lib "eagle-import") (part "RESISTOR-3W-20MM"))
    )
    (comp (ref "R35")
      (value "0.33")
      (footprint "eagle-import:RESISTOR-3W-20MM")
      (libsource (lib "eagle-import") (part "RESISTOR-3W-20MM"))
    )
    (comp (ref "TER_CONN")
      (value "TERMINAL_CONN")
      (footprint "eagle-import:TERMINALCONNECTOR_15MM")
      (libsource (lib "eagle-import") (part "TERMINAL_CONN"))
    )
    (comp (ref "U$1")
      (value "L3D-LOGOL3DCUBE-LOGO-0.8X2.5")
      (footprint "eagle-import:L3DCUBE-LOGO-0.8X2.5")
      (libsource (lib "eagle-import") (part "L3D-LOGOL3DCUBE-LOGO-0.8X2.5"))
    )
    (comp (ref "U$2")
      (value "FIDUCIAL-MARK")
      (footprint "eagle-import:FIDUCIAL-MARK")
      (libsource (lib "eagle-import") (part "FIDUCIAL-MARK"))
    )
    (comp (ref "U$3")
      (value "FIDUCIAL-MARK")
      (footprint "eagle-import:FIDUCIAL-MARK")
      (libsource (lib "eagle-import") (part "FIDUCIAL-MARK"))
    )
    (comp (ref "U$4")
      (value "BEAGLEBONE_OUTLINE")
      (footprint "eagle-import:BEAGLEBONE_SHIELD")
      (libsource (lib "eagle-import") (part "BEAGLEBONE_OUTLINE"))
    )
    (comp (ref "U$5")
      (value "CUBE-16-DAUGHTERBOARD-SOLDERPAD")
      (footprint "eagle-import:CUBE-16-DAUGHTERBOARD-PAD")
      (libsource (lib "eagle-import") (part "CUBE-16-DAUGHTERBOARD-SOLDERPAD"))
    )
    (comp (ref "U$6")
      (value "CONNECTOR-1X2P-POWER-PAD")
      (footprint "eagle-import:1X2P-POWER-PAD")
      (libsource (lib "eagle-import") (part "CONNECTOR-1X2P-POWER-PAD"))
    )
    (comp (ref "U$7")
      (value "CUBE-16-DAUGHTERBOARD-CURRENT-LMTPAD")
      (footprint "eagle-import:CUBE-16-DAUGHTERBOARD-CURRENT-LMT-PAD")
      (libsource (lib "eagle-import") (part "CUBE-16-DAUGHTERBOARD-CURRENT-LMTPAD"))
    )
    (comp (ref "U$8")
      (value "CUBE-16-DAUGHTERBOARD-CURRENT-LMTPAD")
      (footprint "eagle-import:CUBE-16-DAUGHTERBOARD-CURRENT-LMT-PAD")
      (libsource (lib "eagle-import") (part "CUBE-16-DAUGHTERBOARD-CURRENT-LMTPAD"))
    )
    (comp (ref "U$9")
      (value "CUBE-16-DAUGHTERBOARD-CURRENT-LMTPAD")
      (footprint "eagle-import:CUBE-16-DAUGHTERBOARD-CURRENT-LMT-PAD")
      (libsource (lib "eagle-import") (part "CUBE-16-DAUGHTERBOARD-CURRENT-LMTPAD"))
    )
    (comp (ref "U$10")
      (value "CUBE-16-DAUGHTERBOARD-CURRENT-LMTPAD")
      (footprint "eagle-import:CUBE-16-DAUGHTERBOARD-CURRENT-LMT-PAD")
      (libsource (lib "eagle-import") (part "CUBE-16-DAUGHTERBOARD-CURRENT-LMTPAD"))
    )
  )
  (nets
    (net (code "1") (name "+3V3") (class "Default")
      (node (ref "JP2") (pin "1") (pinfunction "1_1") (pintype "passive"))
      (node (ref "JP2") (pin "3") (pinfunction "3_3") (pintype "passive"))
      (node (ref "JP4") (pin "1") (pinfunction "1_1") (pintype "passive"))
      (node (ref "JP4") (pin "3") (pinfunction "3_3") (pintype "passive"))
      (node (ref "U$4") (pin "49") (pinfunction "VDD_3V3EXP_49") (pintype "power_in"))
      (node (ref "U$4") (pin "50") (pinfunction "VDD_3V3EXP_50") (pintype "power_in"))
      (node (ref "U$5") (pin "3V3") (pinfunction "+3V3_3V3") (pintype "bidirectional"))
      (node (ref "U$5") (pin "3V3'") (pinfunction "+3V3_3V3'") (pintype "bidirectional"))
    )
    (net (code "2") (name "+5V") (class "Default")
      (node (ref "C21") (pin "+") (pinfunction "1_+") (pintype "bidirectional"))
      (node (ref "JP1") (pin "1") (pinfunction "1_1") (pintype "passive"))
      (node (ref "JP3") (pin "1") (pinfunction "1_1") (pintype "passive"))
      (node (ref "R14") (pin "1") (pinfunction "1_1") (pintype "bidirectional"))
      (node (ref "R27") (pin "1") (pinfunction "1_1") (pintype "bidirectional"))
      (node (ref "R28") (pin "1") (pinfunction "1_1") (pintype "bidirectional"))
      (node (ref "R29") (pin "1") (pinfunction "1_1") (pintype "bidirectional"))
      (node (ref "R3") (pin "1") (pinfunction "1_1") (pintype "bidirectional"))
      (node (ref "R30") (pin "1") (pinfunction "1_1") (pintype "bidirectional"))
      (node (ref "R31") (pin "1") (pinfunction "1_1") (pintype "bidirectional"))
      (node (ref "R32") (pin "1") (pinfunction "1_1") (pintype "bidirectional"))
      (node (ref "R33") (pin "1") (pinfunction "1_1") (pintype "bidirectional"))
      (node (ref "R34") (pin "1") (pinfunction "1_1") (pintype "bidirectional"))
      (node (ref "R35") (pin "1") (pinfunction "1_1") (pintype "bidirectional"))
      (node (ref "R7") (pin "1") (pinfunction "1_1") (pintype "bidirectional"))
      (node (ref "U$10") (pin "VCC") (pinfunction "VCC_VCC") (pintype "bidirectional"))
      (node (ref "U$4") (pin "51") (pinfunction "VDD_5V_51") (pintype "power_in"))
      (node (ref "U$4") (pin "52") (pinfunction "VDD_5V_52") (pintype "power_in"))
      (node (ref "U$5") (pin "5V") (pinfunction "+5V_5V") (pintype "bidirectional"))
      (node (ref "U$5") (pin "5V'") (pinfunction "+5V_5V'") (pintype "bidirectional"))
      (node (ref "U$6") (pin "VCC") (pinfunction "VCC_VCC") (pintype "bidirectional"))
      (node (ref "U$7") (pin "VCC") (pinfunction "VCC_VCC") (pintype "bidirectional"))
      (node (ref "U$8") (pin "VCC") (pinfunction "VCC_VCC") (pintype "bidirectional"))
      (node (ref "U$9") (pin "VCC") (pinfunction "VCC_VCC") (pintype "bidirectional"))
    )
    (net (code "3") (name "/A2") (class "Default")
      (node (ref "JP1") (pin "10") (pinfunction "10_10") (pintype "passive"))
      (node (ref "JP3") (pin "10") (pinfunction "10_10") (pintype "passive"))
      (node (ref "U$4") (pin "43") (pinfunction "GPIO2_8_43") (pintype "passive"))
      (node (ref "U$5") (pin "IN4") (pinfunction "IN4_IN4") (pintype "bidirectional"))
    )
    (net (code "4") (name "/A3") (class "Default")
      (node (ref "JP1") (pin "9") (pinfunction "9_9") (pintype "passive"))
      (node (ref "JP3") (pin "9") (pinfunction "9_9") (pintype "passive"))
      (node (ref "U$4") (pin "39") (pinfunction "GPIO2_12_39") (pintype "passive"))
      (node (ref "U$5") (pin "IN5") (pinfunction "IN5_IN5") (pintype "bidirectional"))
    )
    (net (code "5") (name "/A4") (class "Default")
      (node (ref "JP1") (pin "8") (pinfunction "8_8") (pintype "passive"))
      (node (ref "JP3") (pin "8") (pinfunction "8_8") (pintype "passive"))
      (node (ref "U$4") (pin "44") (pinfunction "GPIO2_9_44") (pintype "passive"))
      (node (ref "U$5") (pin "IN6") (pinfunction "IN6_IN6") (pintype "bidirectional"))
    )
    (net (code "6") (name "/A5") (class "Default")
      (node (ref "JP1") (pin "7") (pinfunction "7_7") (pintype "passive"))
      (node (ref "JP3") (pin "7") (pinfunction "7_7") (pintype "passive"))
      (node (ref "U$4") (pin "40") (pinfunction "GPIO2_13_40") (pintype "passive"))
      (node (ref "U$5") (pin "IN7") (pinfunction "IN7_IN7") (pintype "bidirectional"))
    )
    (net (code "7") (name "/D0") (class "Default")
      (node (ref "JP2") (pin "12") (pinfunction "12_12") (pintype "passive"))
      (node (ref "JP4") (pin "12") (pinfunction "12_12") (pintype "passive"))
      (node (ref "U$4") (pin "45") (pinfunction "GPIO2_6_45") (pintype "passive"))
      (node (ref "U$5") (pin "IN0") (pinfunction "IN0_IN0") (pintype "bidirectional"))
    )
    (net (code "8") (name "/D1") (class "Default")
      (node (ref "JP2") (pin "11") (pinfunction "11_11") (pintype "passive"))
      (node (ref "JP4") (pin "11") (pinfunction "11_11") (pintype "passive"))
      (node (ref "U$4") (pin "41") (pinfunction "GPIO2_10_41") (pintype "passive"))
      (node (ref "U$5") (pin "IN1") (pinfunction "IN1_IN1") (pintype "bidirectional"))
    )
    (net (code "9") (name "/D2") (class "Default")
      (node (ref "JP2") (pin "10") (pinfunction "10_10") (pintype "passive"))
      (node (ref "JP4") (pin "10") (pinfunction "10_10") (pintype "passive"))
      (node (ref "U$4") (pin "46") (pinfunction "GPIO2_7_46") (pintype "passive"))
      (node (ref "U$5") (pin "IN2") (pinfunction "IN2_IN2") (pintype "bidirectional"))
    )
    (net (code "10") (name "/D3") (class "Default")
      (node (ref "JP2") (pin "9") (pinfunction "9_9") (pintype "passive"))
      (node (ref "JP4") (pin "9") (pinfunction "9_9") (pintype "passive"))
      (node (ref "U$4") (pin "42") (pinfunction "GPIO2_11_42") (pintype "passive"))
      (node (ref "U$5") (pin "IN3") (pinfunction "IN3_IN3") (pintype "bidirectional"))
    )
    (net (code "11") (name "/D7") (class "Default")
      (node (ref "JP2") (pin "5") (pinfunction "5_5") (pintype "passive"))
      (node (ref "JP4") (pin "5") (pinfunction "5_5") (pintype "passive"))
    )
    (net (code "12") (name "/DOUT_1") (class "Default")
      (node (ref "J32") (pin "3") (pinfunction "3_3") (pintype "bidirectional"))
      (node (ref "JP5") (pin "1") (pinfunction "1_1") (pintype "passive"))
    )
    (net (code "13") (name "/DOUT_3") (class "Default")
      (node (ref "J96") (pin "3") (pinfunction "3_3") (pintype "bidirectional"))
      (node (ref "JP5") (pin "3") (pinfunction "3_3") (pintype "passive"))
    )
    (net (code "14") (name "/DOUT_5") (class "Default")
      (node (ref "J160") (pin "3") (pinfunction "3_3") (pintype "bidirectional"))
      (node (ref "JP5") (pin "5") (pinfunction "5_5") (pintype "passive"))
    )
    (net (code "15") (name "/DOUT_7") (class "Default")
      (node (ref "J224") (pin "3") (pinfunction "3_3") (pintype "bidirectional"))
      (node (ref "JP5") (pin "7") (pinfunction "7_7") (pintype "passive"))
    )
    (net (code "16") (name "/RX") (class "Default")
      (node (ref "JP1") (pin "4") (pinfunction "4_4") (pintype "passive"))
      (node (ref "JP3") (pin "4") (pinfunction "4_4") (pintype "passive"))
    )
    (net (code "17") (name "/SYS_5V") (class "Default")
      (node (ref "U$4") (pin "53") (pinfunction "SYS_5V_53") (pintype "power_in"))
    )
    (net (code "18") (name "/TX") (class "Default")
      (node (ref "JP1") (pin "3") (pinfunction "3_3") (pintype "passive"))
      (node (ref "JP3") (pin "3") (pinfunction "3_3") (pintype "passive"))
    )
    (net (code "19") (name "/~{RST}") (class "Default")
      (node (ref "JP2") (pin "2") (pinfunction "2_2") (pintype "passive"))
      (node (ref "JP4") (pin "2") (pinfunction "2_2") (pintype "passive"))
      (node (ref "U$5") (pin "RST") (pinfunction "RST_RST") (pintype "bidirectional"))
    )
    (net (code "20") (name "DIN_1") (class "Default")
      (node (ref "J1") (pin "2") (pinfunction "2_2") (pintype "bidirectional"))
      (node (ref "U$5") (pin "OUT0") (pinfunction "OUT0_OUT0") (pintype "bidirectional"))
    )
    (net (code "21") (name "DIN_2") (class "Default")
      (node (ref "J33") (pin "2") (pinfunction "2_2") (pintype "bidirectional"))
      (node (ref "JP5") (pin "2") (pinfunction "2_2") (pintype "passive"))
      (node (ref "U$5") (pin "OUT1") (pinfunction "OUT1_OUT1") (pintype "bidirectional"))
    )
    (net (code "22") (name "DIN_3") (class "Default")
      (node (ref "J65") (pin "2") (pinfunction "2_2") (pintype "bidirectional"))
      (node (ref "U$5") (pin "OUT2") (pinfunction "OUT2_OUT2") (pintype "bidirectional"))
    )
    (net (code "23") (name "DIN_4") (class "Default")
      (node (ref "J97") (pin "2") (pinfunction "2_2") (pintype "bidirectional"))
      (node (ref "JP5") (pin "4") (pinfunction "4_4") (pintype "passive"))
      (node (ref "U$5") (pin "OUT3") (pinfunction "OUT3_OUT3") (pintype "bidirectional"))
    )
    (net (code "24") (name "DIN_5") (class "Default")
      (node (ref "J129") (pin "2") (pinfunction "2_2") (pintype "bidirectional"))
      (node (ref "U$5") (pin "OUT4") (pinfunction "OUT4_OUT4") (pintype "bidirectional"))
    )
    (net (code "25") (name "DIN_6") (class "Default")
      (node (ref "J161") (pin "2") (pinfunction "2_2") (pintype "bidirectional"))
      (node (ref "JP5") (pin "6") (pinfunction "6_6") (pintype "passive"))
      (node (ref "U$5") (pin "OUT5") (pinfunction "OUT5_OUT5") (pintype "bidirectional"))
    )
    (net (code "26") (name "DIN_7") (class "Default")
      (node (ref "J193") (pin "2") (pinfunction "2_2") (pintype "bidirectional"))
      (node (ref "U$5") (pin "OUT6") (pinfunction "OUT6_OUT6") (pintype "bidirectional"))
    )
    (net (code "27") (name "DIN_8") (class "Default")
      (node (ref "J225") (pin "2") (pinfunction "2_2") (pintype "bidirectional"))
      (node (ref "JP5") (pin "8") (pinfunction "8_8") (pintype "passive"))
      (node (ref "U$5") (pin "OUT7") (pinfunction "OUT7_OUT7") (pintype "bidirectional"))
    )
    (net (code "28") (name "GAIN-CTR") (class "Default")
      (node (ref "JP2") (pin "7") (pinfunction "7_7") (pintype "passive"))
      (node (ref "JP4") (pin "7") (pinfunction "7_7") (pintype "passive"))
      (node (ref "U$4") (pin "83") (pinfunction "AIN2_83") (pintype "passive"))
      (node (ref "U$5") (pin "GAIN-CTR") (pinfunction "GAIN-CTR_GAIN-CTR") (pintype "bidirectional"))
    )
    (net (code "29") (name "GND") (class "Default")
      (node (ref "C1") (pin "-") (pinfunction "2_-") (pintype "bidirectional"))
      (node (ref "C2") (pin "-") (pinfunction "2_-") (pintype "bidirectional"))
      (node (ref "C21") (pin "-") (pinfunction "2_-") (pintype "bidirectional"))
      (node (ref "C3") (pin "-") (pinfunction "2_-") (pintype "bidirectional"))
      (node (ref "C4") (pin "-") (pinfunction "2_-") (pintype "bidirectional"))
      (node (ref "J1") (pin "4") (pinfunction "4_4") (pintype "bidirectional"))
      (node (ref "J10") (pin "4") (pinfunction "4_4") (pintype "bidirectional"))
      (node (ref "J100") (pin "4") (pinfunction "4_4") (pintype "bidirectional"))
      (node (ref "J101") (pin "4") (pinfunction "4_4") (pintype "bidirectional"))
      (node (ref "J102") (pin "4") (pinfunction "4_4") (pintype "bidirectional"))
      (node (ref "J103") (pin "4") (pinfunction "4_4") (pintype "bidirectional"))
      (node (ref "J104") (pin "4") (pinfunction "4_4") (pintype "bidirectional"))
      (node (ref "J105") (pin "4") (pinfunction "4_4") (pintype "bidirectional"))
      (node (ref "J106") (pin "4") (pinfunction "4_4") (pintype "bidirectional"))
      (node (ref "J107") (pin "4") (pinfunction "4_4") (pintype "bidirectional"))
      (node (ref "J108") (pin "4") (pinfunction "4_4") (pintype "bidirectional"))
      (node (ref "J109") (pin "4") (pinfunction "4_4") (pintype "bidirectional"))
      (node (ref "J11") (pin "4") (pinfunction "4_4") (pintype "bidirectional"))
      (node (ref "J110") (pin "4") (pinfunction "4_4") (pintype "bidirectional"))
      (node (ref "J111") (pin "4") (pinfunction "4_4") (pintype "bidirectional"))
      (node (ref "J112") (pin "4") (pinfunction "4_4") (pintype "bidirectional"))
      (node (ref "J113") (pin "4") (pinfunction "4_4") (pintype "bidirectional"))
      (node (ref "J114") (pin "4") (pinfunction "4_4") (pintype "bidirectional"))
      (node (ref "J115") (pin "4") (pinfunction "4_4") (pintype "bidirectional"))
      (node (ref "J116") (pin "4") (pinfunction "4_4") (pintype "bidirectional"))
      (node (ref "J117") (pin "4") (pinfunction "4_4") (pintype "bidirectional"))
      (node (ref "J118") (pin "4") (pinfunction "4_4") (pintype "bidirectional"))
      (node (ref "J119") (pin "4") (pinfunction "4_4") (pintype "bidirectional"))
      (node (ref "J12") (pin "4") (pinfunction "4_4") (pintype "bidirectional"))
      (node (ref "J120") (pin "4") (pinfunction "4_4") (pintype "bidirectional"))
      (node (ref "J121") (pin "4") (pinfunction "4_4") (pintype "bidirectional"))
      (node (ref "J122") (pin "4") (pinfunction "4_4") (pintype "bidirectional"))
      (node (ref "J123") (pin "4") (pinfunction "4_4") (pintype "bidirectional"))
      (node (ref "J124") (pin "4") (pinfunction "4_4") (pintype "bidirectional"))
      (node (ref "J125") (pin "4") (pinfunction "4_4") (pintype "bidirectional"))
      (node (ref "J126") (pin "4") (pinfunction "4_4") (pintype "bidirectional"))
      (node (ref "J127") (pin "4") (pinfunction "4_4") (pintype "bidirectional"))
      (node (ref "J128") (pin "4") (pinfunction "4_4") (pintype "bidirectional"))
      (node (ref "J129") (pin "4") (pinfunction "4_4") (pintype "bidirectional"))
      (node (ref "J13") (pin "4") (pinfunction "4_4") (pintype "bidirectional"))
      (node (ref "J130") (pin "4") (pinfunction "4_4") (pintype "bidirectional"))
      (node (ref "J131") (pin "4") (pinfunction "4_4") (pintype "bidirectional"))
      (node (ref "J132") (pin "4") (pinfunction "4_4") (pintype "bidirectional"))
      (node (ref "J133") (pin "4") (pinfunction "4_4") (pintype "bidirectional"))
      (node (ref "J134") (pin "4") (pinfunction "4_4") (pintype "bidirectional"))
      (node (ref "J135") (pin "4") (pinfunction "4_4") (pintype "bidirectional"))
      (node (ref "J136") (pin "4") (pinfunction "4_4") (pintype "bidirectional"))
      (node (ref "J137") (pin "4") (pinfunction "4_4") (pintype "bidirectional"))
      (node (ref "J138") (pin "4") (pinfunction "4_4") (pintype "bidirectional"))
      (node (ref "J139") (pin "4") (pinfunction "4_4") (pintype "bidirectional"))
      (node (ref "J14") (pin "4") (pinfunction "4_4") (pintype "bidirectional"))
      (node (ref "J140") (pin "4") (pinfunction "4_4") (pintype "bidirectional"))
      (node (ref "J141") (pin "4") (pinfunction "4_4") (pintype "bidirectional"))
      (node (ref "J142") (pin "4") (pinfunction "4_4") (pintype "bidirectional"))
      (node (ref "J143") (pin "4") (pinfunction "4_4") (pintype "bidirectional"))
      (node (ref "J144") (pin "4") (pinfunction "4_4") (pintype "bidirectional"))
      (node (ref "J145") (pin "4") (pinfunction "4_4") (pintype "bidirectional"))
      (node (ref "J146") (pin "4") (pinfunction "4_4") (pintype "bidirectional"))
      (node (ref "J147") (pin "4") (pinfunction "4_4") (pintype "bidirectional"))
      (node (ref "J148") (pin "4") (pinfunction "4_4") (pintype "bidirectional"))
      (node (ref "J149") (pin "4") (pinfunction "4_4") (pintype "bidirectional"))
      (node (ref "J15") (pin "4") (pinfunction "4_4") (pintype "bidirectional"))
      (node (ref "J150") (pin "4") (pinfunction "4_4") (pintype "bidirectional"))
      (node (ref "J151") (pin "4") (pinfunction "4_4") (pintype "bidirectional"))
      (node (ref "J152") (pin "4") (pinfunction "4_4") (pintype "bidirectional"))
      (node (ref "J153") (pin "4") (pinfunction "4_4") (pintype "bidirectional"))
      (node (ref "J154") (pin "4") (pinfunction "4_4") (pintype "bidirectional"))
      (node (ref "J155") (pin "4") (pinfunction "4_4") (pintype "bidirectional"))
      (node (ref "J156") (pin "4") (pinfunction "4_4") (pintype "bidirectional"))
      (node (ref "J157") (pin "4") (pinfunction "4_4") (pintype "bidirectional"))
      (node (ref "J158") (pin "4") (pinfunction "4_4") (pintype "bidirectional"))
      (node (ref "J159") (pin "4") (pinfunction "4_4") (pintype "bidirectional"))
      (node (ref "J16") (pin "4") (pinfunction "4_4") (pintype "bidirectional"))
      (node (ref "J160") (pin "4") (pinfunction "4_4") (pintype "bidirectional"))
      (node (ref "J161") (pin "4") (pinfunction "4_4") (pintype "bidirectional"))
      (node (ref "J162") (pin "4") (pinfunction "4_4") (pintype "bidirectional"))
      (node (ref "J163") (pin "4") (pinfunction "4_4") (pintype "bidirectional"))
      (node (ref "J164") (pin "4") (pinfunction "4_4") (pintype "bidirectional"))
      (node (ref "J165") (pin "4") (pinfunction "4_4") (pintype "bidirectional"))
      (node (ref "J166") (pin "4") (pinfunction "4_4") (pintype "bidirectional"))
      (node (ref "J167") (pin "4") (pinfunction "4_4") (pintype "bidirectional"))
      (node (ref "J168") (pin "4") (pinfunction "4_4") (pintype "bidirectional"))
      (node (ref "J169") (pin "4") (pinfunction "4_4") (pintype "bidirectional"))
      (node (ref "J17") (pin "4") (pinfunction "4_4") (pintype "bidirectional"))
      (node (ref "J170") (pin "4") (pinfunction "4_4") (pintype "bidirectional"))
      (node (ref "J171") (pin "4") (pinfunction "4_4") (pintype "bidirectional"))
      (node (ref "J172") (pin "4") (pinfunction "4_4") (pintype "bidirectional"))
      (node (ref "J173") (pin "4") (pinfunction "4_4") (pintype "bidirectional"))
      (node (ref "J174") (pin "4") (pinfunction "4_4") (pintype "bidirectional"))
      (node (ref "J175") (pin "4") (pinfunction "4_4") (pintype "bidirectional"))
      (node (ref "J176") (pin "4") (pinfunction "4_4") (pintype "bidirectional"))
      (node (ref "J177") (pin "4") (pinfunction "4_4") (pintype "bidirectional"))
      (node (ref "J178") (pin "4") (pinfunction "4_4") (pintype "bidirectional"))
      (node (ref "J179") (pin "4") (pinfunction "4_4") (pintype "bidirectional"))
      (node (ref "J18") (pin "4") (pinfunction "4_4") (pintype "bidirectional"))
      (node (ref "J180") (pin "4") (pinfunction "4_4") (pintype "bidirectional"))
      (node (ref "J181") (pin "4") (pinfunction "4_4") (pintype "bidirectional"))
      (node (ref "J182") (pin "4") (pinfunction "4_4") (pintype "bidirectional"))
      (node (ref "J183") (pin "4") (pinfunction "4_4") (pintype "bidirectional"))
      (node (ref "J184") (pin "4") (pinfunction "4_4") (pintype "bidirectional"))
      (node (ref "J185") (pin "4") (pinfunction "4_4") (pintype "bidirectional"))
      (node (ref "J186") (pin "4") (pinfunction "4_4") (pintype "bidirectional"))
      (node (ref "J187") (pin "4") (pinfunction "4_4") (pintype "bidirectional"))
      (node (ref "J188") (pin "4") (pinfunction "4_4") (pintype "bidirectional"))
      (node (ref "J189") (pin "4") (pinfunction "4_4") (pintype "bidirectional"))
      (node (ref "J19") (pin "4") (pinfunction "4_4") (pintype "bidirectional"))
      (node (ref "J190") (pin "4") (pinfunction "4_4") (pintype "bidirectional"))
      (node (ref "J191") (pin "4") (pinfunction "4_4") (pintype "bidirectional"))
      (node (ref "J192") (pin "4") (pinfunction "4_4") (pintype "bidirectional"))
      (node (ref "J193") (pin "4") (pinfunction "4_4") (pintype "bidirectional"))
      (node (ref "J194") (pin "4") (pinfunction "4_4") (pintype "bidirectional"))
      (node (ref "J195") (pin "4") (pinfunction "4_4") (pintype "bidirectional"))
      (node (ref "J196") (pin "4") (pinfunction "4_4") (pintype "bidirectional"))
      (node (ref "J197") (pin "4") (pinfunction "4_4") (pintype "bidirectional"))
      (node (ref "J198") (pin "4") (pinfunction "4_4") (pintype "bidirectional"))
      (node (ref "J199") (pin "4") (pinfunction "4_4") (pintype "bidirectional"))
      (node (ref "J2") (pin "4") (pinfunction "4_4") (pintype "bidirectional"))
      (node (ref "J20") (pin "4") (pinfunction "4_4") (pintype "bidirectional"))
      (node (ref "J200") (pin "4") (pinfunction "4_4") (pintype "bidirectional"))
      (node (ref "J201") (pin "4") (pinfunction "4_4") (pintype "bidirectional"))
      (node (ref "J202") (pin "4") (pinfunction "4_4") (pintype "bidirectional"))
      (node (ref "J203") (pin "4") (pinfunction "4_4") (pintype "bidirectional"))
      (node (ref "J204") (pin "4") (pinfunction "4_4") (pintype "bidirectional"))
      (node (ref "J205") (pin "4") (pinfunction "4_4") (pintype "bidirectional"))
      (node (ref "J206") (pin "4") (pinfunction "4_4") (pintype "bidirectional"))
      (node (ref "J207") (pin "4") (pinfunction "4_4") (pintype "bidirectional"))
      (node (ref "J208") (pin "4") (pinfunction "4_4") (pintype "bidirectional"))
      (node (ref "J209") (pin "4") (pinfunction "4_4") (pintype "bidirectional"))
      (node (ref "J21") (pin "4") (pinfunction "4_4") (pintype "bidirectional"))
      (node (ref "J210") (pin "4") (pinfunction "4_4") (pintype "bidirectional"))
      (node (ref "J211") (pin "4") (pinfunction "4_4") (pintype "bidirectional"))
      (node (ref "J212") (pin "4") (pinfunction "4_4") (pintype "bidirectional"))
      (node (ref "J213") (pin "4") (pinfunction "4_4") (pintype "bidirectional"))
      (node (ref "J214") (pin "4") (pinfunction "4_4") (pintype "bidirectional"))
      (node (ref "J215") (pin "4") (pinfunction "4_4") (pintype "bidirectional"))
      (node (ref "J216") (pin "4") (pinfunction "4_4") (pintype "bidirectional"))
      (node (ref "J217") (pin "4") (pinfunction "4_4") (pintype "bidirectional"))
      (node (ref "J218") (pin "4") (pinfunction "4_4") (pintype "bidirectional"))
      (node (ref "J219") (pin "4") (pinfunction "4_4") (pintype "bidirectional"))
      (node (ref "J22") (pin "4") (pinfunction "4_4") (pintype "bidirectional"))
      (node (ref "J220") (pin "4") (pinfunction "4_4") (pintype "bidirectional"))
      (node (ref "J221") (pin "4") (pinfunction "4_4") (pintype "bidirectional"))
      (node (ref "J222") (pin "4") (pinfunction "4_4") (pintype "bidirectional"))
      (node (ref "J223") (pin "4") (pinfunction "4_4") (pintype "bidirectional"))
      (node (ref "J224") (pin "4") (pinfunction "4_4") (pintype "bidirectional"))
      (node (ref "J225") (pin "4") (pinfunction "4_4") (pintype "bidirectional"))
      (node (ref "J226") (pin "4") (pinfunction "4_4") (pintype "bidirectional"))
      (node (ref "J227") (pin "4") (pinfunction "4_4") (pintype "bidirectional"))
      (node (ref "J228") (pin "4") (pinfunction "4_4") (pintype "bidirectional"))
      (node (ref "J229") (pin "4") (pinfunction "4_4") (pintype "bidirectional"))
      (node (ref "J23") (pin "4") (pinfunction "4_4") (pintype "bidirectional"))
      (node (ref "J230") (pin "4") (pinfunction "4_4") (pintype "bidirectional"))
      (node (ref "J231") (pin "4") (pinfunction "4_4") (pintype "bidirectional"))
      (node (ref "J232") (pin "4") (pinfunction "4_4") (pintype "bidirectional"))
      (node (ref "J233") (pin "4") (pinfunction "4_4") (pintype "bidirectional"))
      (node (ref "J234") (pin "4") (pinfunction "4_4") (pintype "bidirectional"))
      (node (ref "J235") (pin "4") (pinfunction "4_4") (pintype "bidirectional"))
      (node (ref "J236") (pin "4") (pinfunction "4_4") (pintype "bidirectional"))
      (node (ref "J237") (pin "4") (pinfunction "4_4") (pintype "bidirectional"))
      (node (ref "J238") (pin "4") (pinfunction "4_4") (pintype "bidirectional"))
      (node (ref "J239") (pin "4") (pinfunction "4_4") (pintype "bidirectional"))
      (node (ref "J24") (pin "4") (pinfunction "4_4") (pintype "bidirectional"))
      (node (ref "J240") (pin "4") (pinfunction "4_4") (pintype "bidirectional"))
      (node (ref "J241") (pin "4") (pinfunction "4_4") (pintype "bidirectional"))
      (node (ref "J242") (pin "4") (pinfunction "4_4") (pintype "bidirectional"))
      (node (ref "J243") (pin "4") (pinfunction "4_4") (pintype "bidirectional"))
      (node (ref "J244") (pin "4") (pinfunction "4_4") (pintype "bidirectional"))
      (node (ref "J245") (pin "4") (pinfunction "4_4") (pintype "bidirectional"))
      (node (ref "J246") (pin "4") (pinfunction "4_4") (pintype "bidirectional"))
      (node (ref "J247") (pin "4") (pinfunction "4_4") (pintype "bidirectional"))
      (node (ref "J248") (pin "4") (pinfunction "4_4") (pintype "bidirectional"))
      (node (ref "J249") (pin "4") (pinfunction "4_4") (pintype "bidirectional"))
      (node (ref "J25") (pin "4") (pinfunction "4_4") (pintype "bidirectional"))
      (node (ref "J250") (pin "4") (pinfunction "4_4") (pintype "bidirectional"))
      (node (ref "J251") (pin "4") (pinfunction "4_4") (pintype "bidirectional"))
      (node (ref "J252") (pin "4") (pinfunction "4_4") (pintype "bidirectional"))
      (node (ref "J253") (pin "4") (pinfunction "4_4") (pintype "bidirectional"))
      (node (ref "J254") (pin "4") (pinfunction "4_4") (pintype "bidirectional"))
      (node (ref "J255") (pin "4") (pinfunction "4_4") (pintype "bidirectional"))
      (node (ref "J256") (pin "4") (pinfunction "4_4") (pintype "bidirectional"))
      (node (ref "J26") (pin "4") (pinfunction "4_4") (pintype "bidirectional"))
      (node (ref "J27") (pin "4") (pinfunction "4_4") (pintype "bidirectional"))
      (node (ref "J28") (pin "4") (pinfunction "4_4") (pintype "bidirectional"))
      (node (ref "J29") (pin "4") (pinfunction "4_4") (pintype "bidirectional"))
      (node (ref "J3") (pin "4") (pinfunction "4_4") (pintype "bidirectional"))
      (node (ref "J30") (pin "4") (pinfunction "4_4") (pintype "bidirectional"))
      (node (ref "J31") (pin "4") (pinfunction "4_4") (pintype "bidirectional"))
      (node (ref "J32") (pin "4") (pinfunction "4_4") (pintype "bidirectional"))
      (node (ref "J33") (pin "4") (pinfunction "4_4") (pintype "bidirectional"))
      (node (ref "J34") (pin "4") (pinfunction "4_4") (pintype "bidirectional"))
      (node (ref "J35") (pin "4") (pinfunction "4_4") (pintype "bidirectional"))
      (node (ref "J36") (pin "4") (pinfunction "4_4") (pintype "bidirectional"))
      (node (ref "J37") (pin "4") (pinfunction "4_4") (pintype "bidirectional"))
      (node (ref "J38") (pin "4") (pinfunction "4_4") (pintype "bidirectional"))
      (node (ref "J39") (pin "4") (pinfunction "4_4") (pintype "bidirectional"))
      (node (ref "J4") (pin "4") (pinfunction "4_4") (pintype "bidirectional"))
      (node (ref "J40") (pin "4") (pinfunction "4_4") (pintype "bidirectional"))
      (node (ref "J41") (pin "4") (pinfunction "4_4") (pintype "bidirectional"))
      (node (ref "J42") (pin "4") (pinfunction "4_4") (pintype "bidirectional"))
      (node (ref "J43") (pin "4") (pinfunction "4_4") (pintype "bidirectional"))
      (node (ref "J44") (pin "4") (pinfunction "4_4") (pintype "bidirectional"))
      (node (ref "J45") (pin "4") (pinfunction "4_4") (pintype "bidirectional"))
      (node (ref "J46") (pin "4") (pinfunction "4_4") (pintype "bidirectional"))
      (node (ref "J47") (pin "4") (pinfunction "4_4") (pintype "bidirectional"))
      (node (ref "J48") (pin "4") (pinfunction "4_4") (pintype "bidirectional"))
      (node (ref "J49") (pin "4") (pinfunction "4_4") (pintype "bidirectional"))
      (node (ref "J5") (pin "4") (pinfunction "4_4") (pintype "bidirectional"))
      (node (ref "J50") (pin "4") (pinfunction "4_4") (pintype "bidirectional"))
      (node (ref "J51") (pin "4") (pinfunction "4_4") (pintype "bidirectional"))
      (node (ref "J52") (pin "4") (pinfunction "4_4") (pintype "bidirectional"))
      (node (ref "J53") (pin "4") (pinfunction "4_4") (pintype "bidirectional"))
      (node (ref "J54") (pin "4") (pinfunction "4_4") (pintype "bidirectional"))
      (node (ref "J55") (pin "4") (pinfunction "4_4") (pintype "bidirectional"))
      (node (ref "J56") (pin "4") (pinfunction "4_4") (pintype "bidirectional"))
      (node (ref "J57") (pin "4") (pinfunction "4_4") (pintype "bidirectional"))
      (node (ref "J58") (pin "4") (pinfunction "4_4") (pintype "bidirectional"))
      (node (ref "J59") (pin "4") (pinfunction "4_4") (pintype "bidirectional"))
      (node (ref "J6") (pin "4") (pinfunction "4_4") (pintype "bidirectional"))
      (node (ref "J60") (pin "4") (pinfunction "4_4") (pintype "bidirectional"))
      (node (ref "J61") (pin "4") (pinfunction "4_4") (pintype "bidirectional"))
      (node (ref "J62") (pin "4") (pinfunction "4_4") (pintype "bidirectional"))
      (node (ref "J63") (pin "4") (pinfunction "4_4") (pintype "bidirectional"))
      (node (ref "J64") (pin "4") (pinfunction "4_4") (pintype "bidirectional"))
      (node (ref "J65") (pin "4") (pinfunction "4_4") (pintype "bidirectional"))
      (node (ref "J66") (pin "4") (pinfunction "4_4") (pintype "bidirectional"))
      (node (ref "J67") (pin "4") (pinfunction "4_4") (pintype "bidirectional"))
      (node (ref "J68") (pin "4") (pinfunction "4_4") (pintype "bidirectional"))
      (node (ref "J69") (pin "4") (pinfunction "4_4") (pintype "bidirectional"))
      (node (ref "J7") (pin "4") (pinfunction "4_4") (pintype "bidirectional"))
      (node (ref "J70") (pin "4") (pinfunction "4_4") (pintype "bidirectional"))
      (node (ref "J71") (pin "4") (pinfunction "4_4") (pintype "bidirectional"))
      (node (ref "J72") (pin "4") (pinfunction "4_4") (pintype "bidirectional"))
      (node (ref "J73") (pin "4") (pinfunction "4_4") (pintype "bidirectional"))
      (node (ref "J74") (pin "4") (pinfunction "4_4") (pintype "bidirectional"))
      (node (ref "J75") (pin "4") (pinfunction "4_4") (pintype "bidirectional"))
      (node (ref "J76") (pin "4") (pinfunction "4_4") (pintype "bidirectional"))
      (node (ref "J77") (pin "4") (pinfunction "4_4") (pintype "bidirectional"))
      (node (ref "J78") (pin "4") (pinfunction "4_4") (pintype "bidirectional"))
      (node (ref "J79") (pin "4") (pinfunction "4_4") (pintype "bidirectional"))
      (node (ref "J8") (pin "4") (pinfunction "4_4") (pintype "bidirectional"))
      (node (ref "J80") (pin "4") (pinfunction "4_4") (pintype "bidirectional"))
      (node (ref "J81") (pin "4") (pinfunction "4_4") (pintype "bidirectional"))
      (node (ref "J82") (pin "4") (pinfunction "4_4") (pintype "bidirectional"))
      (node (ref "J83") (pin "4") (pinfunction "4_4") (pintype "bidirectional"))
      (node (ref "J84") (pin "4") (pinfunction "4_4") (pintype "bidirectional"))
      (node (ref "J85") (pin "4") (pinfunction "4_4") (pintype "bidirectional"))
      (node (ref "J86") (pin "4") (pinfunction "4_4") (pintype "bidirectional"))
      (node (ref "J87") (pin "4") (pinfunction "4_4") (pintype "bidirectional"))
      (node (ref "J88") (pin "4") (pinfunction "4_4") (pintype "bidirectional"))
      (node (ref "J89") (pin "4") (pinfunction "4_4") (pintype "bidirectional"))
      (node (ref "J9") (pin "4") (pinfunction "4_4") (pintype "bidirectional"))
      (node (ref "J90") (pin "4") (pinfunction "4_4") (pintype "bidirectional"))
      (node (ref "J91") (pin "4") (pinfunction "4_4") (pintype "bidirectional"))
      (node (ref "J92") (pin "4") (pinfunction "4_4") (pintype "bidirectional"))
      (node (ref "J93") (pin "4") (pinfunction "4_4") (pintype "bidirectional"))
      (node (ref "J94") (pin "4") (pinfunction "4_4") (pintype "bidirectional"))
      (node (ref "J95") (pin "4") (pinfunction "4_4") (pintype "bidirectional"))
      (node (ref "J96") (pin "4") (pinfunction "4_4") (pintype "bidirectional"))
      (node (ref "J97") (pin "4") (pinfunction "4_4") (pintype "bidirectional"))
      (node (ref "J98") (pin "4") (pinfunction "4_4") (pintype "bidirectional"))
      (node (ref "J99") (pin "4") (pinfunction "4_4") (pintype "bidirectional"))
      (node (ref "JP1") (pin "2") (pinfunction "2_2") (pintype "passive"))
      (node (ref "JP2") (pin "4") (pinfunction "4_4") (pintype "passive"))
      (node (ref "JP3") (pin "2") (pinfunction "2_2") (pintype "passive"))
      (node (ref "JP4") (pin "4") (pinfunction "4_4") (pintype "passive"))
      (node (ref "ONLINE/OFFLINE") (pin "3") (pinfunction "S_3") (pintype "passive"))
      (node (ref "TER_CONN") (pin "2_1") (pinfunction "2_2_1") (pintype "bidirectional"))
      (node (ref "TER_CONN") (pin "2_2") (pinfunction "2_2_2") (pintype "bidirectional"))
      (node (ref "TER_CONN") (pin "2_3") (pinfunction "2_2_3") (pintype "bidirectional"))
      (node (ref "TER_CONN") (pin "2_4") (pinfunction "2_2_4") (pintype "bidirectional"))
      (node (ref "U$10") (pin "GND") (pinfunction "GND_GND") (pintype "bidirectional"))
      (node (ref "U$10") (pin "GND1") (pinfunction "GND_GND1") (pintype "bidirectional"))
      (node (ref "U$10") (pin "GND2") (pinfunction "GND_GND2") (pintype "bidirectional"))
      (node (ref "U$4") (pin "1") (pinfunction "GND_1") (pintype "power_in"))
      (node (ref "U$4") (pin "2") (pinfunction "GND_2") (pintype "power_in"))
      (node (ref "U$4") (pin "47") (pinfunction "GND_47") (pintype "power_in"))
      (node (ref "U$4") (pin "48") (pinfunction "GND_48") (pintype "power_in"))
      (node (ref "U$4") (pin "89") (pinfunction "GND_89") (pintype "power_in"))
      (node (ref "U$4") (pin "90") (pinfunction "GND_90") (pintype "power_in"))
      (node (ref "U$4") (pin "91") (pinfunction "GND_91") (pintype "power_in"))
      (node (ref "U$4") (pin "92") (pinfunction "GND_92") (pintype "power_in"))
      (node (ref "U$5") (pin "P$1") (pinfunction "GND_P$1") (pintype "bidirectional"))
      (node (ref "U$5") (pin "P$2") (pinfunction "GND_P$2") (pintype "bidirectional"))
      (node (ref "U$5") (pin "P$27") (pinfunction "GND_P$27") (pintype "bidirectional"))
      (node (ref "U$5") (pin "P$3") (pinfunction "GND_P$3") (pintype "bidirectional"))
      (node (ref "U$5") (pin "P$30") (pinfunction "GND_P$30") (pintype "bidirectional"))
      (node (ref "U$5") (pin "P$31") (pinfunction "GND_P$31") (pintype "bidirectional"))
      (node (ref "U$5") (pin "P$32") (pinfunction "GND_P$32") (pintype "bidirectional"))
      (node (ref "U$5") (pin "P$33") (pinfunction "GND_P$33") (pintype "bidirectional"))
      (node (ref "U$5") (pin "P$4") (pinfunction "GND_P$4") (pintype "bidirectional"))
      (node (ref "U$5") (pin "P$44") (pinfunction "GND_P$44") (pintype "bidirectional"))
      (node (ref "U$5") (pin "P$45") (pinfunction "GND_P$45") (pintype "bidirectional"))
      (node (ref "U$5") (pin "P$46") (pinfunction "GND_P$46") (pintype "bidirectional"))
      (node (ref "U$5") (pin "P$47") (pinfunction "GND_P$47") (pintype "bidirectional"))
      (node (ref "U$5") (pin "P$48") (pinfunction "GND_P$48") (pintype "bidirectional"))
      (node (ref "U$5") (pin "P$5") (pinfunction "GND_P$5") (pintype "bidirectional"))
      (node (ref "U$5") (pin "P$6") (pinfunction "GND_P$6") (pintype "bidirectional"))
      (node (ref "U$5") (pin "P$8") (pinfunction "GND_P$8") (pintype "bidirectional"))
      (node (ref "U$6") (pin "GND") (pinfunction "GND_GND") (pintype "bidirectional"))
      (node (ref "U$7") (pin "GND") (pinfunction "GND_GND") (pintype "bidirectional"))
      (node (ref "U$7") (pin "GND1") (pinfunction "GND_GND1") (pintype "bidirectional"))
      (node (ref "U$7") (pin "GND2") (pinfunction "GND_GND2") (pintype "bidirectional"))
      (node (ref "U$8") (pin "GND") (pinfunction "GND_GND") (pintype "bidirectional"))
      (node (ref "U$8") (pin "GND1") (pinfunction "GND_GND1") (pintype "bidirectional"))
      (node (ref "U$8") (pin "GND2") (pinfunction "GND_GND2") (pintype "bidirectional"))
      (node (ref "U$9") (pin "GND") (pinfunction "GND_GND") (pintype "bidirectional"))
      (node (ref "U$9") (pin "GND1") (pinfunction "GND_GND1") (pintype "bidirectional"))
      (node (ref "U$9") (pin "GND2") (pinfunction "GND_GND2") (pintype "bidirectional"))
    )
    (net (code "30") (name "MODE") (class "Default")
      (node (ref "JP2") (pin "8") (pinfunction "8_8") (pintype "passive"))
      (node (ref "JP4") (pin "8") (pinfunction "8_8") (pintype "passive"))
      (node (ref "U$5") (pin "MODE") (pinfunction "MODE_MODE") (pintype "bidirectional"))
    )
    (net (code "31") (name "Net-(J1-Pad3)") (class "Default")
      (node (ref "J1") (pin "3") (pinfunction "3_3") (pintype "bidirectional"))
      (node (ref "J2") (pin "2") (pinfunction "2_2") (pintype "bidirectional"))
    )
    (net (code "32") (name "Net-(J2-Pad3)") (class "Default")
      (node (ref "J2") (pin "3") (pinfunction "3_3") (pintype "bidirectional"))
      (node (ref "J3") (pin "2") (pinfunction "2_2") (pintype "bidirectional"))
    )
    (net (code "33") (name "Net-(J3-Pad3)") (class "Default")
      (node (ref "J3") (pin "3") (pinfunction "3_3") (pintype "bidirectional"))
      (node (ref "J4") (pin "2") (pinfunction "2_2") (pintype "bidirectional"))
    )
    (net (code "34") (name "Net-(J4-Pad3)") (class "Default")
      (node (ref "J4") (pin "3") (pinfunction "3_3") (pintype "bidirectional"))
      (node (ref "J5") (pin "2") (pinfunction "2_2") (pintype "bidirectional"))
    )
    (net (code "35") (name "Net-(J5-Pad3)") (class "Default")
      (node (ref "J5") (pin "3") (pinfunction "3_3") (pintype "bidirectional"))
      (node (ref "J6") (pin "2") (pinfunction "2_2") (pintype "bidirectional"))
    )
    (net (code "36") (name "Net-(J6-Pad3)") (class "Default")
      (node (ref "J6") (pin "3") (pinfunction "3_3") (pintype "bidirectional"))
      (node (ref "J7") (pin "2") (pinfunction "2_2") (pintype "bidirectional"))
    )
    (net (code "37") (name "Net-(J7-Pad3)") (class "Default")
      (node (ref "J7") (pin "3") (pinfunction "3_3") (pintype "bidirectional"))
      (node (ref "J8") (pin "2") (pinfunction "2_2") (pintype "bidirectional"))
    )
    (net (code "38") (name "Net-(J8-Pad3)") (class "Default")
      (node (ref "J8") (pin "3") (pinfunction "3_3") (pintype "bidirectional"))
      (node (ref "J9") (pin "2") (pinfunction "2_2") (pintype "bidirectional"))
    )
    (net (code "39") (name "Net-(J10-Pad2)") (class "Default")
      (node (ref "J10") (pin "2") (pinfunction "2_2") (pintype "bidirectional"))
      (node (ref "J9") (pin "3") (pinfunction "3_3") (pintype "bidirectional"))
    )
    (net (code "40") (name "Net-(J10-Pad3)") (class "Default")
      (node (ref "J10") (pin "3") (pinfunction "3_3") (pintype "bidirectional"))
      (node (ref "J11") (pin "2") (pinfunction "2_2") (pintype "bidirectional"))
    )
    (net (code "41") (name "Net-(J11-Pad3)") (class "Default")
      (node (ref "J11") (pin "3") (pinfunction "3_3") (pintype "bidirectional"))
      (node (ref "J12") (pin "2") (pinfunction "2_2") (pintype "bidirectional"))
    )
    (net (code "42") (name "Net-(J12-Pad3)") (class "Default")
      (node (ref "J12") (pin "3") (pinfunction "3_3") (pintype "bidirectional"))
      (node (ref "J13") (pin "2") (pinfunction "2_2") (pintype "bidirectional"))
    )
    (net (code "43") (name "Net-(J13-Pad3)") (class "Default")
      (node (ref "J13") (pin "3") (pinfunction "3_3") (pintype "bidirectional"))
      (node (ref "J14") (pin "2") (pinfunction "2_2") (pintype "bidirectional"))
    )
    (net (code "44") (name "Net-(J14-Pad3)") (class "Default")
      (node (ref "J14") (pin "3") (pinfunction "3_3") (pintype "bidirectional"))
      (node (ref "J15") (pin "2") (pinfunction "2_2") (pintype "bidirectional"))
    )
    (net (code "45") (name "Net-(J15-Pad3)") (class "Default")
      (node (ref "J15") (pin "3") (pinfunction "3_3") (pintype "bidirectional"))
      (node (ref "J16") (pin "2") (pinfunction "2_2") (pintype "bidirectional"))
    )
    (net (code "46") (name "Net-(J16-Pad3)") (class "Default")
      (node (ref "J16") (pin "3") (pinfunction "3_3") (pintype "bidirectional"))
      (node (ref "J17") (pin "2") (pinfunction "2_2") (pintype "bidirectional"))
    )
    (net (code "47") (name "Net-(J17-Pad3)") (class "Default")
      (node (ref "J17") (pin "3") (pinfunction "3_3") (pintype "bidirectional"))
      (node (ref "J18") (pin "2") (pinfunction "2_2") (pintype "bidirectional"))
    )
    (net (code "48") (name "Net-(J18-Pad3)") (class "Default")
      (node (ref "J18") (pin "3") (pinfunction "3_3") (pintype "bidirectional"))
      (node (ref "J19") (pin "2") (pinfunction "2_2") (pintype "bidirectional"))
    )
    (net (code "49") (name "Net-(J19-Pad3)") (class "Default")
      (node (ref "J19") (pin "3") (pinfunction "3_3") (pintype "bidirectional"))
      (node (ref "J20") (pin "2") (pinfunction "2_2") (pintype "bidirectional"))
    )
    (net (code "50") (name "Net-(J20-Pad3)") (class "Default")
      (node (ref "J20") (pin "3") (pinfunction "3_3") (pintype "bidirectional"))
      (node (ref "J21") (pin "2") (pinfunction "2_2") (pintype "bidirectional"))
    )
    (net (code "51") (name "Net-(J21-Pad3)") (class "Default")
      (node (ref "J21") (pin "3") (pinfunction "3_3") (pintype "bidirectional"))
      (node (ref "J22") (pin "2") (pinfunction "2_2") (pintype "bidirectional"))
    )
    (net (code "52") (name "Net-(J22-Pad3)") (class "Default")
      (node (ref "J22") (pin "3") (pinfunction "3_3") (pintype "bidirectional"))
      (node (ref "J23") (pin "2") (pinfunction "2_2") (pintype "bidirectional"))
    )
    (net (code "53") (name "Net-(J23-Pad3)") (class "Default")
      (node (ref "J23") (pin "3") (pinfunction "3_3") (pintype "bidirectional"))
      (node (ref "J24") (pin "2") (pinfunction "2_2") (pintype "bidirectional"))
    )
    (net (code "54") (name "Net-(J24-Pad3)") (class "Default")
      (node (ref "J24") (pin "3") (pinfunction "3_3") (pintype "bidirectional"))
      (node (ref "J25") (pin "2") (pinfunction "2_2") (pintype "bidirectional"))
    )
    (net (code "55") (name "Net-(J25-Pad3)") (class "Default")
      (node (ref "J25") (pin "3") (pinfunction "3_3") (pintype "bidirectional"))
      (node (ref "J26") (pin "2") (pinfunction "2_2") (pintype "bidirectional"))
    )
    (net (code "56") (name "Net-(J26-Pad3)") (class "Default")
      (node (ref "J26") (pin "3") (pinfunction "3_3") (pintype "bidirectional"))
      (node (ref "J27") (pin "2") (pinfunction "2_2") (pintype "bidirectional"))
    )
    (net (code "57") (name "Net-(J27-Pad3)") (class "Default")
      (node (ref "J27") (pin "3") (pinfunction "3_3") (pintype "bidirectional"))
      (node (ref "J28") (pin "2") (pinfunction "2_2") (pintype "bidirectional"))
    )
    (net (code "58") (name "Net-(J28-Pad3)") (class "Default")
      (node (ref "J28") (pin "3") (pinfunction "3_3") (pintype "bidirectional"))
      (node (ref "J29") (pin "2") (pinfunction "2_2") (pintype "bidirectional"))
    )
    (net (code "59") (name "Net-(J29-Pad3)") (class "Default")
      (node (ref "J29") (pin "3") (pinfunction "3_3") (pintype "bidirectional"))
      (node (ref "J30") (pin "2") (pinfunction "2_2") (pintype "bidirectional"))
    )
    (net (code "60") (name "Net-(J30-Pad3)") (class "Default")
      (node (ref "J30") (pin "3") (pinfunction "3_3") (pintype "bidirectional"))
      (node (ref "J31") (pin "2") (pinfunction "2_2") (pintype "bidirectional"))
    )
    (net (code "61") (name "Net-(J31-Pad3)") (class "Default")
      (node (ref "J31") (pin "3") (pinfunction "3_3") (pintype "bidirectional"))
      (node (ref "J32") (pin "2") (pinfunction "2_2") (pintype "bidirectional"))
    )
    (net (code "62") (name "Net-(J33-Pad3)") (class "Default")
      (node (ref "J33") (pin "3") (pinfunction "3_3") (pintype "bidirectional"))
      (node (ref "J34") (pin "2") (pinfunction "2_2") (pintype "bidirectional"))
    )
    (net (code "63") (name "Net-(J34-Pad3)") (class "Default")
      (node (ref "J34") (pin "3") (pinfunction "3_3") (pintype "bidirectional"))
      (node (ref "J35") (pin "2") (pinfunction "2_2") (pintype "bidirectional"))
    )
    (net (code "64") (name "Net-(J35-Pad3)") (class "Default")
      (node (ref "J35") (pin "3") (pinfunction "3_3") (pintype "bidirectional"))
      (node (ref "J36") (pin "2") (pinfunction "2_2") (pintype "bidirectional"))
    )
    (net (code "65") (name "Net-(J36-Pad3)") (class "Default")
      (node (ref "J36") (pin "3") (pinfunction "3_3") (pintype "bidirectional"))
      (node (ref "J37") (pin "2") (pinfunction "2_2") (pintype "bidirectional"))
    )
    (net (code "66") (name "Net-(J37-Pad3)") (class "Default")
      (node (ref "J37") (pin "3") (pinfunction "3_3") (pintype "bidirectional"))
      (node (ref "J38") (pin "2") (pinfunction "2_2") (pintype "bidirectional"))
    )
    (net (code "67") (name "Net-(J38-Pad3)") (class "Default")
      (node (ref "J38") (pin "3") (pinfunction "3_3") (pintype "bidirectional"))
      (node (ref "J39") (pin "2") (pinfunction "2_2") (pintype "bidirectional"))
    )
    (net (code "68") (name "Net-(J39-Pad3)") (class "Default")
      (node (ref "J39") (pin "3") (pinfunction "3_3") (pintype "bidirectional"))
      (node (ref "J40") (pin "2") (pinfunction "2_2") (pintype "bidirectional"))
    )
    (net (code "69") (name "Net-(J40-Pad3)") (class "Default")
      (node (ref "J40") (pin "3") (pinfunction "3_3") (pintype "bidirectional"))
      (node (ref "J41") (pin "2") (pinfunction "2_2") (pintype "bidirectional"))
    )
    (net (code "70") (name "Net-(J41-Pad3)") (class "Default")
      (node (ref "J41") (pin "3") (pinfunction "3_3") (pintype "bidirectional"))
      (node (ref "J42") (pin "2") (pinfunction "2_2") (pintype "bidirectional"))
    )
    (net (code "71") (name "Net-(J42-Pad3)") (class "Default")
      (node (ref "J42") (pin "3") (pinfunction "3_3") (pintype "bidirectional"))
      (node (ref "J43") (pin "2") (pinfunction "2_2") (pintype "bidirectional"))
    )
    (net (code "72") (name "Net-(J43-Pad3)") (class "Default")
      (node (ref "J43") (pin "3") (pinfunction "3_3") (pintype "bidirectional"))
      (node (ref "J44") (pin "2") (pinfunction "2_2") (pintype "bidirectional"))
    )
    (net (code "73") (name "Net-(J44-Pad3)") (class "Default")
      (node (ref "J44") (pin "3") (pinfunction "3_3") (pintype "bidirectional"))
      (node (ref "J45") (pin "2") (pinfunction "2_2") (pintype "bidirectional"))
    )
    (net (code "74") (name "Net-(J45-Pad3)") (class "Default")
      (node (ref "J45") (pin "3") (pinfunction "3_3") (pintype "bidirectional"))
      (node (ref "J46") (pin "2") (pinfunction "2_2") (pintype "bidirectional"))
    )
    (net (code "75") (name "Net-(J46-Pad3)") (class "Default")
      (node (ref "J46") (pin "3") (pinfunction "3_3") (pintype "bidirectional"))
      (node (ref "J47") (pin "2") (pinfunction "2_2") (pintype "bidirectional"))
    )
    (net (code "76") (name "Net-(J47-Pad3)") (class "Default")
      (node (ref "J47") (pin "3") (pinfunction "3_3") (pintype "bidirectional"))
      (node (ref "J48") (pin "2") (pinfunction "2_2") (pintype "bidirectional"))
    )
    (net (code "77") (name "Net-(J48-Pad3)") (class "Default")
      (node (ref "J48") (pin "3") (pinfunction "3_3") (pintype "bidirectional"))
      (node (ref "J49") (pin "2") (pinfunction "2_2") (pintype "bidirectional"))
    )
    (net (code "78") (name "Net-(J49-Pad3)") (class "Default")
      (node (ref "J49") (pin "3") (pinfunction "3_3") (pintype "bidirectional"))
      (node (ref "J50") (pin "2") (pinfunction "2_2") (pintype "bidirectional"))
    )
    (net (code "79") (name "Net-(J50-Pad3)") (class "Default")
      (node (ref "J50") (pin "3") (pinfunction "3_3") (pintype "bidirectional"))
      (node (ref "J51") (pin "2") (pinfunction "2_2") (pintype "bidirectional"))
    )
    (net (code "80") (name "Net-(J51-Pad3)") (class "Default")
      (node (ref "J51") (pin "3") (pinfunction "3_3") (pintype "bidirectional"))
      (node (ref "J52") (pin "2") (pinfunction "2_2") (pintype "bidirectional"))
    )
    (net (code "81") (name "Net-(J52-Pad3)") (class "Default")
      (node (ref "J52") (pin "3") (pinfunction "3_3") (pintype "bidirectional"))
      (node (ref "J53") (pin "2") (pinfunction "2_2") (pintype "bidirectional"))
    )
    (net (code "82") (name "Net-(J53-Pad3)") (class "Default")
      (node (ref "J53") (pin "3") (pinfunction "3_3") (pintype "bidirectional"))
      (node (ref "J54") (pin "2") (pinfunction "2_2") (pintype "bidirectional"))
    )
    (net (code "83") (name "Net-(J54-Pad3)") (class "Default")
      (node (ref "J54") (pin "3") (pinfunction "3_3") (pintype "bidirectional"))
      (node (ref "J55") (pin "2") (pinfunction "2_2") (pintype "bidirectional"))
    )
    (net (code "84") (name "Net-(J55-Pad3)") (class "Default")
      (node (ref "J55") (pin "3") (pinfunction "3_3") (pintype "bidirectional"))
      (node (ref "J56") (pin "2") (pinfunction "2_2") (pintype "bidirectional"))
    )
    (net (code "85") (name "Net-(J56-Pad3)") (class "Default")
      (node (ref "J56") (pin "3") (pinfunction "3_3") (pintype "bidirectional"))
      (node (ref "J57") (pin "2") (pinfunction "2_2") (pintype "bidirectional"))
    )
    (net (code "86") (name "Net-(J57-Pad3)") (class "Default")
      (node (ref "J57") (pin "3") (pinfunction "3_3") (pintype "bidirectional"))
      (node (ref "J58") (pin "2") (pinfunction "2_2") (pintype "bidirectional"))
    )
    (net (code "87") (name "Net-(J58-Pad3)") (class "Default")
      (node (ref "J58") (pin "3") (pinfunction "3_3") (pintype "bidirectional"))
      (node (ref "J59") (pin "2") (pinfunction "2_2") (pintype "bidirectional"))
    )
    (net (code "88") (name "Net-(J59-Pad3)") (class "Default")
      (node (ref "J59") (pin "3") (pinfunction "3_3") (pintype "bidirectional"))
      (node (ref "J60") (pin "2") (pinfunction "2_2") (pintype "bidirectional"))
    )
    (net (code "89") (name "Net-(J60-Pad3)") (class "Default")
      (node (ref "J60") (pin "3") (pinfunction "3_3") (pintype "bidirectional"))
      (node (ref "J61") (pin "2") (pinfunction "2_2") (pintype "bidirectional"))
    )
    (net (code "90") (name "Net-(J61-Pad3)") (class "Default")
      (node (ref "J61") (pin "3") (pinfunction "3_3") (pintype "bidirectional"))
      (node (ref "J62") (pin "2") (pinfunction "2_2") (pintype "bidirectional"))
    )
    (net (code "91") (name "Net-(J62-Pad3)") (class "Default")
      (node (ref "J62") (pin "3") (pinfunction "3_3") (pintype "bidirectional"))
      (node (ref "J63") (pin "2") (pinfunction "2_2") (pintype "bidirectional"))
    )
    (net (code "92") (name "Net-(J63-Pad3)") (class "Default")
      (node (ref "J63") (pin "3") (pinfunction "3_3") (pintype "bidirectional"))
      (node (ref "J64") (pin "2") (pinfunction "2_2") (pintype "bidirectional"))
    )
    (net (code "93") (name "Net-(J65-Pad3)") (class "Default")
      (node (ref "J65") (pin "3") (pinfunction "3_3") (pintype "bidirectional"))
      (node (ref "J66") (pin "2") (pinfunction "2_2") (pintype "bidirectional"))
    )
    (net (code "94") (name "Net-(J66-Pad3)") (class "Default")
      (node (ref "J66") (pin "3") (pinfunction "3_3") (pintype "bidirectional"))
      (node (ref "J67") (pin "2") (pinfunction "2_2") (pintype "bidirectional"))
    )
    (net (code "95") (name "Net-(J67-Pad3)") (class "Default")
      (node (ref "J67") (pin "3") (pinfunction "3_3") (pintype "bidirectional"))
      (node (ref "J68") (pin "2") (pinfunction "2_2") (pintype "bidirectional"))
    )
    (net (code "96") (name "Net-(J68-Pad3)") (class "Default")
      (node (ref "J68") (pin "3") (pinfunction "3_3") (pintype "bidirectional"))
      (node (ref "J69") (pin "2") (pinfunction "2_2") (pintype "bidirectional"))
    )
    (net (code "97") (name "Net-(J69-Pad3)") (class "Default")
      (node (ref "J69") (pin "3") (pinfunction "3_3") (pintype "bidirectional"))
      (node (ref "J70") (pin "2") (pinfunction "2_2") (pintype "bidirectional"))
    )
    (net (code "98") (name "Net-(J70-Pad3)") (class "Default")
      (node (ref "J70") (pin "3") (pinfunction "3_3") (pintype "bidirectional"))
      (node (ref "J71") (pin "2") (pinfunction "2_2") (pintype "bidirectional"))
    )
    (net (code "99") (name "Net-(J71-Pad3)") (class "Default")
      (node (ref "J71") (pin "3") (pinfunction "3_3") (pintype "bidirectional"))
      (node (ref "J72") (pin "2") (pinfunction "2_2") (pintype "bidirectional"))
    )
    (net (code "100") (name "Net-(J72-Pad3)") (class "Default")
      (node (ref "J72") (pin "3") (pinfunction "3_3") (pintype "bidirectional"))
      (node (ref "J73") (pin "2") (pinfunction "2_2") (pintype "bidirectional"))
    )
    (net (code "101") (name "Net-(J73-Pad3)") (class "Default")
      (node (ref "J73") (pin "3") (pinfunction "3_3") (pintype "bidirectional"))
      (node (ref "J74") (pin "2") (pinfunction "2_2") (pintype "bidirectional"))
    )
    (net (code "102") (name "Net-(J74-Pad3)") (class "Default")
      (node (ref "J74") (pin "3") (pinfunction "3_3") (pintype "bidirectional"))
      (node (ref "J75") (pin "2") (pinfunction "2_2") (pintype "bidirectional"))
    )
    (net (code "103") (name "Net-(J75-Pad3)") (class "Default")
      (node (ref "J75") (pin "3") (pinfunction "3_3") (pintype "bidirectional"))
      (node (ref "J76") (pin "2") (pinfunction "2_2") (pintype "bidirectional"))
    )
    (net (code "104") (name "Net-(J76-Pad3)") (class "Default")
      (node (ref "J76") (pin "3") (pinfunction "3_3") (pintype "bidirectional"))
      (node (ref "J77") (pin "2") (pinfunction "2_2") (pintype "bidirectional"))
    )
    (net (code "105") (name "Net-(J77-Pad3)") (class "Default")
      (node (ref "J77") (pin "3") (pinfunction "3_3") (pintype "bidirectional"))
      (node (ref "J78") (pin "2") (pinfunction "2_2") (pintype "bidirectional"))
    )
    (net (code "106") (name "Net-(J78-Pad3)") (class "Default")
      (node (ref "J78") (pin "3") (pinfunction "3_3") (pintype "bidirectional"))
      (node (ref "J79") (pin "2") (pinfunction "2_2") (pintype "bidirectional"))
    )
    (net (code "107") (name "Net-(J79-Pad3)") (class "Default")
      (node (ref "J79") (pin "3") (pinfunction "3_3") (pintype "bidirectional"))
      (node (ref "J80") (pin "2") (pinfunction "2_2") (pintype "bidirectional"))
    )
    (net (code "108") (name "Net-(J80-Pad3)") (class "Default")
      (node (ref "J80") (pin "3") (pinfunction "3_3") (pintype "bidirectional"))
      (node (ref "J81") (pin "2") (pinfunction "2_2") (pintype "bidirectional"))
    )
    (net (code "109") (name "Net-(J81-Pad3)") (class "Default")
      (node (ref "J81") (pin "3") (pinfunction "3_3") (pintype "bidirectional"))
      (node (ref "J82") (pin "2") (pinfunction "2_2") (pintype "bidirectional"))
    )
    (net (code "110") (name "Net-(J82-Pad3)") (class "Default")
      (node (ref "J82") (pin "3") (pinfunction "3_3") (pintype "bidirectional"))
      (node (ref "J83") (pin "2") (pinfunction "2_2") (pintype "bidirectional"))
    )
    (net (code "111") (name "Net-(J83-Pad3)") (class "Default")
      (node (ref "J83") (pin "3") (pinfunction "3_3") (pintype "bidirectional"))
      (node (ref "J84") (pin "2") (pinfunction "2_2") (pintype "bidirectional"))
    )
    (net (code "112") (name "Net-(J84-Pad3)") (class "Default")
      (node (ref "J84") (pin "3") (pinfunction "3_3") (pintype "bidirectional"))
      (node (ref "J85") (pin "2") (pinfunction "2_2") (pintype "bidirectional"))
    )
    (net (code "113") (name "Net-(J85-Pad3)") (class "Default")
      (node (ref "J85") (pin "3") (pinfunction "3_3") (pintype "bidirectional"))
      (node (ref "J86") (pin "2") (pinfunction "2_2") (pintype "bidirectional"))
    )
    (net (code "114") (name "Net-(J86-Pad3)") (class "Default")
      (node (ref "J86") (pin "3") (pinfunction "3_3") (pintype "bidirectional"))
      (node (ref "J87") (pin "2") (pinfunction "2_2") (pintype "bidirectional"))
    )
    (net (code "115") (name "Net-(J87-Pad3)") (class "Default")
      (node (ref "J87") (pin "3") (pinfunction "3_3") (pintype "bidirectional"))
      (node (ref "J88") (pin "2") (pinfunction "2_2") (pintype "bidirectional"))
    )
    (net (code "116") (name "Net-(J88-Pad3)") (class "Default")
      (node (ref "J88") (pin "3") (pinfunction "3_3") (pintype "bidirectional"))
      (node (ref "J89") (pin "2") (pinfunction "2_2") (pintype "bidirectional"))
    )
    (net (code "117") (name "Net-(J89-Pad3)") (class "Default")
      (node (ref "J89") (pin "3") (pinfunction "3_3") (pintype "bidirectional"))
      (node (ref "J90") (pin "2") (pinfunction "2_2") (pintype "bidirectional"))
    )
    (net (code "118") (name "Net-(J90-Pad3)") (class "Default")
      (node (ref "J90") (pin "3") (pinfunction "3_3") (pintype "bidirectional"))
      (node (ref "J91") (pin "2") (pinfunction "2_2") (pintype "bidirectional"))
    )
    (net (code "119") (name "Net-(J91-Pad3)") (class "Default")
      (node (ref "J91") (pin "3") (pinfunction "3_3") (pintype "bidirectional"))
      (node (ref "J92") (pin "2") (pinfunction "2_2") (pintype "bidirectional"))
    )
    (net (code "120") (name "Net-(J92-Pad3)") (class "Default")
      (node (ref "J92") (pin "3") (pinfunction "3_3") (pintype "bidirectional"))
      (node (ref "J93") (pin "2") (pinfunction "2_2") (pintype "bidirectional"))
    )
    (net (code "121") (name "Net-(J93-Pad3)") (class "Default")
      (node (ref "J93") (pin "3") (pinfunction "3_3") (pintype "bidirectional"))
      (node (ref "J94") (pin "2") (pinfunction "2_2") (pintype "bidirectional"))
    )
    (net (code "122") (name "Net-(J94-Pad3)") (class "Default")
      (node (ref "J94") (pin "3") (pinfunction "3_3") (pintype "bidirectional"))
      (node (ref "J95") (pin "2") (pinfunction "2_2") (pintype "bidirectional"))
    )
    (net (code "123") (name "Net-(J95-Pad3)") (class "Default")
      (node (ref "J95") (pin "3") (pinfunction "3_3") (pintype "bidirectional"))
      (node (ref "J96") (pin "2") (pinfunction "2_2") (pintype "bidirectional"))
    )
    (net (code "124") (name "Net-(J97-Pad3)") (class "Default")
      (node (ref "J97") (pin "3") (pinfunction "3_3") (pintype "bidirectional"))
      (node (ref "J98") (pin "2") (pinfunction "2_2") (pintype "bidirectional"))
    )
    (net (code "125") (name "Net-(J98-Pad3)") (class "Default")
      (node (ref "J98") (pin "3") (pinfunction "3_3") (pintype "bidirectional"))
      (node (ref "J99") (pin "2") (pinfunction "2_2") (pintype "bidirectional"))
    )
    (net (code "126") (name "Net-(J100-Pad2)") (class "Default")
      (node (ref "J100") (pin "2") (pinfunction "2_2") (pintype "bidirectional"))
      (node (ref "J99") (pin "3") (pinfunction "3_3") (pintype "bidirectional"))
    )
    (net (code "127") (name "Net-(J100-Pad3)") (class "Default")
      (node (ref "J100") (pin "3") (pinfunction "3_3") (pintype "bidirectional"))
      (node (ref "J101") (pin "2") (pinfunction "2_2") (pintype "bidirectional"))
    )
    (net (code "128") (name "Net-(J101-Pad3)") (class "Default")
      (node (ref "J101") (pin "3") (pinfunction "3_3") (pintype "bidirectional"))
      (node (ref "J102") (pin "2") (pinfunction "2_2") (pintype "bidirectional"))
    )
    (net (code "129") (name "Net-(J102-Pad3)") (class "Default")
      (node (ref "J102") (pin "3") (pinfunction "3_3") (pintype "bidirectional"))
      (node (ref "J103") (pin "2") (pinfunction "2_2") (pintype "bidirectional"))
    )
    (net (code "130") (name "Net-(J103-Pad3)") (class "Default")
      (node (ref "J103") (pin "3") (pinfunction "3_3") (pintype "bidirectional"))
      (node (ref "J104") (pin "2") (pinfunction "2_2") (pintype "bidirectional"))
    )
    (net (code "131") (name "Net-(J104-Pad3)") (class "Default")
      (node (ref "J104") (pin "3") (pinfunction "3_3") (pintype "bidirectional"))
      (node (ref "J105") (pin "2") (pinfunction "2_2") (pintype "bidirectional"))
    )
    (net (code "132") (name "Net-(J105-Pad3)") (class "Default")
      (node (ref "J105") (pin "3") (pinfunction "3_3") (pintype "bidirectional"))
      (node (ref "J106") (pin "2") (pinfunction "2_2") (pintype "bidirectional"))
    )
    (net (code "133") (name "Net-(J106-Pad3)") (class "Default")
      (node (ref "J106") (pin "3") (pinfunction "3_3") (pintype "bidirectional"))
      (node (ref "J107") (pin "2") (pinfunction "2_2") (pintype "bidirectional"))
    )
    (net (code "134") (name "Net-(J107-Pad3)") (class "Default")
      (node (ref "J107") (pin "3") (pinfunction "3_3") (pintype "bidirectional"))
      (node (ref "J108") (pin "2") (pinfunction "2_2") (pintype "bidirectional"))
    )
    (net (code "135") (name "Net-(J108-Pad3)") (class "Default")
      (node (ref "J108") (pin "3") (pinfunction "3_3") (pintype "bidirectional"))
      (node (ref "J109") (pin "2") (pinfunction "2_2") (pintype "bidirectional"))
    )
    (net (code "136") (name "Net-(J109-Pad3)") (class "Default")
      (node (ref "J109") (pin "3") (pinfunction "3_3") (pintype "bidirectional"))
      (node (ref "J110") (pin "2") (pinfunction "2_2") (pintype "bidirectional"))
    )
    (net (code "137") (name "Net-(J110-Pad3)") (class "Default")
      (node (ref "J110") (pin "3") (pinfunction "3_3") (pintype "bidirectional"))
      (node (ref "J111") (pin "2") (pinfunction "2_2") (pintype "bidirectional"))
    )
    (net (code "138") (name "Net-(J111-Pad3)") (class "Default")
      (node (ref "J111") (pin "3") (pinfunction "3_3") (pintype "bidirectional"))
      (node (ref "J112") (pin "2") (pinfunction "2_2") (pintype "bidirectional"))
    )
    (net (code "139") (name "Net-(J112-Pad3)") (class "Default")
      (node (ref "J112") (pin "3") (pinfunction "3_3") (pintype "bidirectional"))
      (node (ref "J113") (pin "2") (pinfunction "2_2") (pintype "bidirectional"))
    )
    (net (code "140") (name "Net-(J113-Pad3)") (class "Default")
      (node (ref "J113") (pin "3") (pinfunction "3_3") (pintype "bidirectional"))
      (node (ref "J114") (pin "2") (pinfunction "2_2") (pintype "bidirectional"))
    )
    (net (code "141") (name "Net-(J114-Pad3)") (class "Default")
      (node (ref "J114") (pin "3") (pinfunction "3_3") (pintype "bidirectional"))
      (node (ref "J115") (pin "2") (pinfunction "2_2") (pintype "bidirectional"))
    )
    (net (code "142") (name "Net-(J115-Pad3)") (class "Default")
      (node (ref "J115") (pin "3") (pinfunction "3_3") (pintype "bidirectional"))
      (node (ref "J116") (pin "2") (pinfunction "2_2") (pintype "bidirectional"))
    )
    (net (code "143") (name "Net-(J116-Pad3)") (class "Default")
      (node (ref "J116") (pin "3") (pinfunction "3_3") (pintype "bidirectional"))
      (node (ref "J117") (pin "2") (pinfunction "2_2") (pintype "bidirectional"))
    )
    (net (code "144") (name "Net-(J117-Pad3)") (class "Default")
      (node (ref "J117") (pin "3") (pinfunction "3_3") (pintype "bidirectional"))
      (node (ref "J118") (pin "2") (pinfunction "2_2") (pintype "bidirectional"))
    )
    (net (code "145") (name "Net-(J118-Pad3)") (class "Default")
      (node (ref "J118") (pin "3") (pinfunction "3_3") (pintype "bidirectional"))
      (node (ref "J119") (pin "2") (pinfunction "2_2") (pintype "bidirectional"))
    )
    (net (code "146") (name "Net-(J119-Pad3)") (class "Default")
      (node (ref "J119") (pin "3") (pinfunction "3_3") (pintype "bidirectional"))
      (node (ref "J120") (pin "2") (pinfunction "2_2") (pintype "bidirectional"))
    )
    (net (code "147") (name "Net-(J120-Pad3)") (class "Default")
      (node (ref "J120") (pin "3") (pinfunction "3_3") (pintype "bidirectional"))
      (node (ref "J121") (pin "2") (pinfunction "2_2") (pintype "bidirectional"))
    )
    (net (code "148") (name "Net-(J121-Pad3)") (class "Default")
      (node (ref "J121") (pin "3") (pinfunction "3_3") (pintype "bidirectional"))
      (node (ref "J122") (pin "2") (pinfunction "2_2") (pintype "bidirectional"))
    )
    (net (code "149") (name "Net-(J122-Pad3)") (class "Default")
      (node (ref "J122") (pin "3") (pinfunction "3_3") (pintype "bidirectional"))
      (node (ref "J123") (pin "2") (pinfunction "2_2") (pintype "bidirectional"))
    )
    (net (code "150") (name "Net-(J123-Pad3)") (class "Default")
      (node (ref "J123") (pin "3") (pinfunction "3_3") (pintype "bidirectional"))
      (node (ref "J124") (pin "2") (pinfunction "2_2") (pintype "bidirectional"))
    )
    (net (code "151") (name "Net-(J124-Pad3)") (class "Default")
      (node (ref "J124") (pin "3") (pinfunction "3_3") (pintype "bidirectional"))
      (node (ref "J125") (pin "2") (pinfunction "2_2") (pintype "bidirectional"))
    )
    (net (code "152") (name "Net-(J125-Pad3)") (class "Default")
      (node (ref "J125") (pin "3") (pinfunction "3_3") (pintype "bidirectional"))
      (node (ref "J126") (pin "2") (pinfunction "2_2") (pintype "bidirectional"))
    )
    (net (code "153") (name "Net-(J126-Pad3)") (class "Default")
      (node (ref "J126") (pin "3") (pinfunction "3_3") (pintype "bidirectional"))
      (node (ref "J127") (pin "2") (pinfunction "2_2") (pintype "bidirectional"))
    )
    (net (code "154") (name "Net-(J127-Pad3)") (class "Default")
      (node (ref "J127") (pin "3") (pinfunction "3_3") (pintype "bidirectional"))
      (node (ref "J128") (pin "2") (pinfunction "2_2") (pintype "bidirectional"))
    )
    (net (code "155") (name "Net-(J129-Pad3)") (class "Default")
      (node (ref "J129") (pin "3") (pinfunction "3_3") (pintype "bidirectional"))
      (node (ref "J130") (pin "2") (pinfunction "2_2") (pintype "bidirectional"))
    )
    (net (code "156") (name "Net-(J130-Pad3)") (class "Default")
      (node (ref "J130") (pin "3") (pinfunction "3_3") (pintype "bidirectional"))
      (node (ref "J131") (pin "2") (pinfunction "2_2") (pintype "bidirectional"))
    )
    (net (code "157") (name "Net-(J131-Pad3)") (class "Default")
      (node (ref "J131") (pin "3") (pinfunction "3_3") (pintype "bidirectional"))
      (node (ref "J132") (pin "2") (pinfunction "2_2") (pintype "bidirectional"))
    )
    (net (code "158") (name "Net-(J132-Pad3)") (class "Default")
      (node (ref "J132") (pin "3") (pinfunction "3_3") (pintype "bidirectional"))
      (node (ref "J133") (pin "2") (pinfunction "2_2") (pintype "bidirectional"))
    )
    (net (code "159") (name "Net-(J133-Pad3)") (class "Default")
      (node (ref "J133") (pin "3") (pinfunction "3_3") (pintype "bidirectional"))
      (node (ref "J134") (pin "2") (pinfunction "2_2") (pintype "bidirectional"))
    )
    (net (code "160") (name "Net-(J134-Pad3)") (class "Default")
      (node (ref "J134") (pin "3") (pinfunction "3_3") (pintype "bidirectional"))
      (node (ref "J135") (pin "2") (pinfunction "2_2") (pintype "bidirectional"))
    )
    (net (code "161") (name "Net-(J135-Pad3)") (class "Default")
      (node (ref "J135") (pin "3") (pinfunction "3_3") (pintype "bidirectional"))
      (node (ref "J136") (pin "2") (pinfunction "2_2") (pintype "bidirectional"))
    )
    (net (code "162") (name "Net-(J136-Pad3)") (class "Default")
      (node (ref "J136") (pin "3") (pinfunction "3_3") (pintype "bidirectional"))
      (node (ref "J137") (pin "2") (pinfunction "2_2") (pintype "bidirectional"))
    )
    (net (code "163") (name "Net-(J137-Pad3)") (class "Default")
      (node (ref "J137") (pin "3") (pinfunction "3_3") (pintype "bidirectional"))
      (node (ref "J138") (pin "2") (pinfunction "2_2") (pintype "bidirectional"))
    )
    (net (code "164") (name "Net-(J138-Pad3)") (class "Default")
      (node (ref "J138") (pin "3") (pinfunction "3_3") (pintype "bidirectional"))
      (node (ref "J139") (pin "2") (pinfunction "2_2") (pintype "bidirectional"))
    )
    (net (code "165") (name "Net-(J139-Pad3)") (class "Default")
      (node (ref "J139") (pin "3") (pinfunction "3_3") (pintype "bidirectional"))
      (node (ref "J140") (pin "2") (pinfunction "2_2") (pintype "bidirectional"))
    )
    (net (code "166") (name "Net-(J140-Pad3)") (class "Default")
      (node (ref "J140") (pin "3") (pinfunction "3_3") (pintype "bidirectional"))
      (node (ref "J141") (pin "2") (pinfunction "2_2") (pintype "bidirectional"))
    )
    (net (code "167") (name "Net-(J141-Pad3)") (class "Default")
      (node (ref "J141") (pin "3") (pinfunction "3_3") (pintype "bidirectional"))
      (node (ref "J142") (pin "2") (pinfunction "2_2") (pintype "bidirectional"))
    )
    (net (code "168") (name "Net-(J142-Pad3)") (class "Default")
      (node (ref "J142") (pin "3") (pinfunction "3_3") (pintype "bidirectional"))
      (node (ref "J143") (pin "2") (pinfunction "2_2") (pintype "bidirectional"))
    )
    (net (code "169") (name "Net-(J143-Pad3)") (class "Default")
      (node (ref "J143") (pin "3") (pinfunction "3_3") (pintype "bidirectional"))
      (node (ref "J144") (pin "2") (pinfunction "2_2") (pintype "bidirectional"))
    )
    (net (code "170") (name "Net-(J144-Pad3)") (class "Default")
      (node (ref "J144") (pin "3") (pinfunction "3_3") (pintype "bidirectional"))
      (node (ref "J145") (pin "2") (pinfunction "2_2") (pintype "bidirectional"))
    )
    (net (code "171") (name "Net-(J145-Pad3)") (class "Default")
      (node (ref "J145") (pin "3") (pinfunction "3_3") (pintype "bidirectional"))
      (node (ref "J146") (pin "2") (pinfunction "2_2") (pintype "bidirectional"))
    )
    (net (code "172") (name "Net-(J146-Pad3)") (class "Default")
      (node (ref "J146") (pin "3") (pinfunction "3_3") (pintype "bidirectional"))
      (node (ref "J147") (pin "2") (pinfunction "2_2") (pintype "bidirectional"))
    )
    (net (code "173") (name "Net-(J147-Pad3)") (class "Default")
      (node (ref "J147") (pin "3") (pinfunction "3_3") (pintype "bidirectional"))
      (node (ref "J148") (pin "2") (pinfunction "2_2") (pintype "bidirectional"))
    )
    (net (code "174") (name "Net-(J148-Pad3)") (class "Default")
      (node (ref "J148") (pin "3") (pinfunction "3_3") (pintype "bidirectional"))
      (node (ref "J149") (pin "2") (pinfunction "2_2") (pintype "bidirectional"))
    )
    (net (code "175") (name "Net-(J149-Pad3)") (class "Default")
      (node (ref "J149") (pin "3") (pinfunction "3_3") (pintype "bidirectional"))
      (node (ref "J150") (pin "2") (pinfunction "2_2") (pintype "bidirectional"))
    )
    (net (code "176") (name "Net-(J150-Pad3)") (class "Default")
      (node (ref "J150") (pin "3") (pinfunction "3_3") (pintype "bidirectional"))
      (node (ref "J151") (pin "2") (pinfunction "2_2") (pintype "bidirectional"))
    )
    (net (code "177") (name "Net-(J151-Pad3)") (class "Default")
      (node (ref "J151") (pin "3") (pinfunction "3_3") (pintype "bidirectional"))
      (node (ref "J152") (pin "2") (pinfunction "2_2") (pintype "bidirectional"))
    )
    (net (code "178") (name "Net-(J152-Pad3)") (class "Default")
      (node (ref "J152") (pin "3") (pinfunction "3_3") (pintype "bidirectional"))
      (node (ref "J153") (pin "2") (pinfunction "2_2") (pintype "bidirectional"))
    )
    (net (code "179") (name "Net-(J153-Pad3)") (class "Default")
      (node (ref "J153") (pin "3") (pinfunction "3_3") (pintype "bidirectional"))
      (node (ref "J154") (pin "2") (pinfunction "2_2") (pintype "bidirectional"))
    )
    (net (code "180") (name "Net-(J154-Pad3)") (class "Default")
      (node (ref "J154") (pin "3") (pinfunction "3_3") (pintype "bidirectional"))
      (node (ref "J155") (pin "2") (pinfunction "2_2") (pintype "bidirectional"))
    )
    (net (code "181") (name "Net-(J155-Pad3)") (class "Default")
      (node (ref "J155") (pin "3") (pinfunction "3_3") (pintype "bidirectional"))
      (node (ref "J156") (pin "2") (pinfunction "2_2") (pintype "bidirectional"))
    )
    (net (code "182") (name "Net-(J156-Pad3)") (class "Default")
      (node (ref "J156") (pin "3") (pinfunction "3_3") (pintype "bidirectional"))
      (node (ref "J157") (pin "2") (pinfunction "2_2") (pintype "bidirectional"))
    )
    (net (code "183") (name "Net-(J157-Pad3)") (class "Default")
      (node (ref "J157") (pin "3") (pinfunction "3_3") (pintype "bidirectional"))
      (node (ref "J158") (pin "2") (pinfunction "2_2") (pintype "bidirectional"))
    )
    (net (code "184") (name "Net-(J158-Pad3)") (class "Default")
      (node (ref "J158") (pin "3") (pinfunction "3_3") (pintype "bidirectional"))
      (node (ref "J159") (pin "2") (pinfunction "2_2") (pintype "bidirectional"))
    )
    (net (code "185") (name "Net-(J159-Pad3)") (class "Default")
      (node (ref "J159") (pin "3") (pinfunction "3_3") (pintype "bidirectional"))
      (node (ref "J160") (pin "2") (pinfunction "2_2") (pintype "bidirectional"))
    )
    (net (code "186") (name "Net-(J161-Pad3)") (class "Default")
      (node (ref "J161") (pin "3") (pinfunction "3_3") (pintype "bidirectional"))
      (node (ref "J162") (pin "2") (pinfunction "2_2") (pintype "bidirectional"))
    )
    (net (code "187") (name "Net-(J162-Pad3)") (class "Default")
      (node (ref "J162") (pin "3") (pinfunction "3_3") (pintype "bidirectional"))
      (node (ref "J163") (pin "2") (pinfunction "2_2") (pintype "bidirectional"))
    )
    (net (code "188") (name "Net-(J163-Pad3)") (class "Default")
      (node (ref "J163") (pin "3") (pinfunction "3_3") (pintype "bidirectional"))
      (node (ref "J164") (pin "2") (pinfunction "2_2") (pintype "bidirectional"))
    )
    (net (code "189") (name "Net-(J164-Pad3)") (class "Default")
      (node (ref "J164") (pin "3") (pinfunction "3_3") (pintype "bidirectional"))
      (node (ref "J165") (pin "2") (pinfunction "2_2") (pintype "bidirectional"))
    )
    (net (code "190") (name "Net-(J165-Pad3)") (class "Default")
      (node (ref "J165") (pin "3") (pinfunction "3_3") (pintype "bidirectional"))
      (node (ref "J166") (pin "2") (pinfunction "2_2") (pintype "bidirectional"))
    )
    (net (code "191") (name "Net-(J166-Pad3)") (class "Default")
      (node (ref "J166") (pin "3") (pinfunction "3_3") (pintype "bidirectional"))
      (node (ref "J167") (pin "2") (pinfunction "2_2") (pintype "bidirectional"))
    )
    (net (code "192") (name "Net-(J167-Pad3)") (class "Default")
      (node (ref "J167") (pin "3") (pinfunction "3_3") (pintype "bidirectional"))
      (node (ref "J168") (pin "2") (pinfunction "2_2") (pintype "bidirectional"))
    )
    (net (code "193") (name "Net-(J168-Pad3)") (class "Default")
      (node (ref "J168") (pin "3") (pinfunction "3_3") (pintype "bidirectional"))
      (node (ref "J169") (pin "2") (pinfunction "2_2") (pintype "bidirectional"))
    )
    (net (code "194") (name "Net-(J169-Pad3)") (class "Default")
      (node (ref "J169") (pin "3") (pinfunction "3_3") (pintype "bidirectional"))
      (node (ref "J170") (pin "2") (pinfunction "2_2") (pintype "bidirectional"))
    )
    (net (code "195") (name "Net-(J170-Pad3)") (class "Default")
      (node (ref "J170") (pin "3") (pinfunction "3_3") (pintype "bidirectional"))
      (node (ref "J171") (pin "2") (pinfunction "2_2") (pintype "bidirectional"))
    )
    (net (code "196") (name "Net-(J171-Pad3)") (class "Default")
      (node (ref "J171") (pin "3") (pinfunction "3_3") (pintype "bidirectional"))
      (node (ref "J172") (pin "2") (pinfunction "2_2") (pintype "bidirectional"))
    )
    (net (code "197") (name "Net-(J172-Pad3)") (class "Default")
      (node (ref "J172") (pin "3") (pinfunction "3_3") (pintype "bidirectional"))
      (node (ref "J173") (pin "2") (pinfunction "2_2") (pintype "bidirectional"))
    )
    (net (code "198") (name "Net-(J173-Pad3)") (class "Default")
      (node (ref "J173") (pin "3") (pinfunction "3_3") (pintype "bidirectional"))
      (node (ref "J174") (pin "2") (pinfunction "2_2") (pintype "bidirectional"))
    )
    (net (code "199") (name "Net-(J174-Pad3)") (class "Default")
      (node (ref "J174") (pin "3") (pinfunction "3_3") (pintype "bidirectional"))
      (node (ref "J175") (pin "2") (pinfunction "2_2") (pintype "bidirectional"))
    )
    (net (code "200") (name "Net-(J175-Pad3)") (class "Default")
      (node (ref "J175") (pin "3") (pinfunction "3_3") (pintype "bidirectional"))
      (node (ref "J176") (pin "2") (pinfunction "2_2") (pintype "bidirectional"))
    )
    (net (code "201") (name "Net-(J176-Pad3)") (class "Default")
      (node (ref "J176") (pin "3") (pinfunction "3_3") (pintype "bidirectional"))
      (node (ref "J177") (pin "2") (pinfunction "2_2") (pintype "bidirectional"))
    )
    (net (code "202") (name "Net-(J177-Pad3)") (class "Default")
      (node (ref "J177") (pin "3") (pinfunction "3_3") (pintype "bidirectional"))
      (node (ref "J178") (pin "2") (pinfunction "2_2") (pintype "bidirectional"))
    )
    (net (code "203") (name "Net-(J178-Pad3)") (class "Default")
      (node (ref "J178") (pin "3") (pinfunction "3_3") (pintype "bidirectional"))
      (node (ref "J179") (pin "2") (pinfunction "2_2") (pintype "bidirectional"))
    )
    (net (code "204") (name "Net-(J179-Pad3)") (class "Default")
      (node (ref "J179") (pin "3") (pinfunction "3_3") (pintype "bidirectional"))
      (node (ref "J180") (pin "2") (pinfunction "2_2") (pintype "bidirectional"))
    )
    (net (code "205") (name "Net-(J180-Pad3)") (class "Default")
      (node (ref "J180") (pin "3") (pinfunction "3_3") (pintype "bidirectional"))
      (node (ref "J181") (pin "2") (pinfunction "2_2") (pintype "bidirectional"))
    )
    (net (code "206") (name "Net-(J181-Pad3)") (class "Default")
      (node (ref "J181") (pin "3") (pinfunction "3_3") (pintype "bidirectional"))
      (node (ref "J182") (pin "2") (pinfunction "2_2") (pintype "bidirectional"))
    )
    (net (code "207") (name "Net-(J182-Pad3)") (class "Default")
      (node (ref "J182") (pin "3") (pinfunction "3_3") (pintype "bidirectional"))
      (node (ref "J183") (pin "2") (pinfunction "2_2") (pintype "bidirectional"))
    )
    (net (code "208") (name "Net-(J183-Pad3)") (class "Default")
      (node (ref "J183") (pin "3") (pinfunction "3_3") (pintype "bidirectional"))
      (node (ref "J184") (pin "2") (pinfunction "2_2") (pintype "bidirectional"))
    )
    (net (code "209") (name "Net-(J184-Pad3)") (class "Default")
      (node (ref "J184") (pin "3") (pinfunction "3_3") (pintype "bidirectional"))
      (node (ref "J185") (pin "2") (pinfunction "2_2") (pintype "bidirectional"))
    )
    (net (code "210") (name "Net-(J185-Pad3)") (class "Default")
      (node (ref "J185") (pin "3") (pinfunction "3_3") (pintype "bidirectional"))
      (node (ref "J186") (pin "2") (pinfunction "2_2") (pintype "bidirectional"))
    )
    (net (code "211") (name "Net-(J186-Pad3)") (class "Default")
      (node (ref "J186") (pin "3") (pinfunction "3_3") (pintype "bidirectional"))
      (node (ref "J187") (pin "2") (pinfunction "2_2") (pintype "bidirectional"))
    )
    (net (code "212") (name "Net-(J187-Pad3)") (class "Default")
      (node (ref "J187") (pin "3") (pinfunction "3_3") (pintype "bidirectional"))
      (node (ref "J188") (pin "2") (pinfunction "2_2") (pintype "bidirectional"))
    )
    (net (code "213") (name "Net-(J188-Pad3)") (class "Default")
      (node (ref "J188") (pin "3") (pinfunction "3_3") (pintype "bidirectional"))
      (node (ref "J189") (pin "2") (pinfunction "2_2") (pintype "bidirectional"))
    )
    (net (code "214") (name "Net-(J189-Pad3)") (class "Default")
      (node (ref "J189") (pin "3") (pinfunction "3_3") (pintype "bidirectional"))
      (node (ref "J190") (pin "2") (pinfunction "2_2") (pintype "bidirectional"))
    )
    (net (code "215") (name "Net-(J190-Pad3)") (class "Default")
      (node (ref "J190") (pin "3") (pinfunction "3_3") (pintype "bidirectional"))
      (node (ref "J191") (pin "2") (pinfunction "2_2") (pintype "bidirectional"))
    )
    (net (code "216") (name "Net-(J191-Pad3)") (class "Default")
      (node (ref "J191") (pin "3") (pinfunction "3_3") (pintype "bidirectional"))
      (node (ref "J192") (pin "2") (pinfunction "2_2") (pintype "bidirectional"))
    )
    (net (code "217") (name "Net-(J193-Pad3)") (class "Default")
      (node (ref "J193") (pin "3") (pinfunction "3_3") (pintype "bidirectional"))
      (node (ref "J194") (pin "2") (pinfunction "2_2") (pintype "bidirectional"))
    )
    (net (code "218") (name "Net-(J194-Pad3)") (class "Default")
      (node (ref "J194") (pin "3") (pinfunction "3_3") (pintype "bidirectional"))
      (node (ref "J195") (pin "2") (pinfunction "2_2") (pintype "bidirectional"))
    )
    (net (code "219") (name "Net-(J195-Pad3)") (class "Default")
      (node (ref "J195") (pin "3") (pinfunction "3_3") (pintype "bidirectional"))
      (node (ref "J196") (pin "2") (pinfunction "2_2") (pintype "bidirectional"))
    )
    (net (code "220") (name "Net-(J196-Pad3)") (class "Default")
      (node (ref "J196") (pin "3") (pinfunction "3_3") (pintype "bidirectional"))
      (node (ref "J197") (pin "2") (pinfunction "2_2") (pintype "bidirectional"))
    )
    (net (code "221") (name "Net-(J197-Pad3)") (class "Default")
      (node (ref "J197") (pin "3") (pinfunction "3_3") (pintype "bidirectional"))
      (node (ref "J198") (pin "2") (pinfunction "2_2") (pintype "bidirectional"))
    )
    (net (code "222") (name "Net-(J198-Pad3)") (class "Default")
      (node (ref "J198") (pin "3") (pinfunction "3_3") (pintype "bidirectional"))
      (node (ref "J199") (pin "2") (pinfunction "2_2") (pintype "bidirectional"))
    )
    (net (code "223") (name "Net-(J199-Pad3)") (class "Default")
      (node (ref "J199") (pin "3") (pinfunction "3_3") (pintype "bidirectional"))
      (node (ref "J200") (pin "2") (pinfunction "2_2") (pintype "bidirectional"))
    )
    (net (code "224") (name "Net-(J200-Pad3)") (class "Default")
      (node (ref "J200") (pin "3") (pinfunction "3_3") (pintype "bidirectional"))
      (node (ref "J201") (pin "2") (pinfunction "2_2") (pintype "bidirectional"))
    )
    (net (code "225") (name "Net-(J201-Pad3)") (class "Default")
      (node (ref "J201") (pin "3") (pinfunction "3_3") (pintype "bidirectional"))
      (node (ref "J202") (pin "2") (pinfunction "2_2") (pintype "bidirectional"))
    )
    (net (code "226") (name "Net-(J202-Pad3)") (class "Default")
      (node (ref "J202") (pin "3") (pinfunction "3_3") (pintype "bidirectional"))
      (node (ref "J203") (pin "2") (pinfunction "2_2") (pintype "bidirectional"))
    )
    (net (code "227") (name "Net-(J203-Pad3)") (class "Default")
      (node (ref "J203") (pin "3") (pinfunction "3_3") (pintype "bidirectional"))
      (node (ref "J204") (pin "2") (pinfunction "2_2") (pintype "bidirectional"))
    )
    (net (code "228") (name "Net-(J204-Pad3)") (class "Default")
      (node (ref "J204") (pin "3") (pinfunction "3_3") (pintype "bidirectional"))
      (node (ref "J205") (pin "2") (pinfunction "2_2") (pintype "bidirectional"))
    )
    (net (code "229") (name "Net-(J205-Pad3)") (class "Default")
      (node (ref "J205") (pin "3") (pinfunction "3_3") (pintype "bidirectional"))
      (node (ref "J206") (pin "2") (pinfunction "2_2") (pintype "bidirectional"))
    )
    (net (code "230") (name "Net-(J206-Pad3)") (class "Default")
      (node (ref "J206") (pin "3") (pinfunction "3_3") (pintype "bidirectional"))
      (node (ref "J207") (pin "2") (pinfunction "2_2") (pintype "bidirectional"))
    )
    (net (code "231") (name "Net-(J207-Pad3)") (class "Default")
      (node (ref "J207") (pin "3") (pinfunction "3_3") (pintype "bidirectional"))
      (node (ref "J208") (pin "2") (pinfunction "2_2") (pintype "bidirectional"))
    )
    (net (code "232") (name "Net-(J208-Pad3)") (class "Default")
      (node (ref "J208") (pin "3") (pinfunction "3_3") (pintype "bidirectional"))
      (node (ref "J209") (pin "2") (pinfunction "2_2") (pintype "bidirectional"))
    )
    (net (code "233") (name "Net-(J209-Pad3)") (class "Default")
      (node (ref "J209") (pin "3") (pinfunction "3_3") (pintype "bidirectional"))
      (node (ref "J210") (pin "2") (pinfunction "2_2") (pintype "bidirectional"))
    )
    (net (code "234") (name "Net-(J210-Pad3)") (class "Default")
      (node (ref "J210") (pin "3") (pinfunction "3_3") (pintype "bidirectional"))
      (node (ref "J211") (pin "2") (pinfunction "2_2") (pintype "bidirectional"))
    )
    (net (code "235") (name "Net-(J211-Pad3)") (class "Default")
      (node (ref "J211") (pin "3") (pinfunction "3_3") (pintype "bidirectional"))
      (node (ref "J212") (pin "2") (pinfunction "2_2") (pintype "bidirectional"))
    )
    (net (code "236") (name "Net-(J212-Pad3)") (class "Default")
      (node (ref "J212") (pin "3") (pinfunction "3_3") (pintype "bidirectional"))
      (node (ref "J213") (pin "2") (pinfunction "2_2") (pintype "bidirectional"))
    )
    (net (code "237") (name "Net-(J213-Pad3)") (class "Default")
      (node (ref "J213") (pin "3") (pinfunction "3_3") (pintype "bidirectional"))
      (node (ref "J214") (pin "2") (pinfunction "2_2") (pintype "bidirectional"))
    )
    (net (code "238") (name "Net-(J214-Pad3)") (class "Default")
      (node (ref "J214") (pin "3") (pinfunction "3_3") (pintype "bidirectional"))
      (node (ref "J215") (pin "2") (pinfunction "2_2") (pintype "bidirectional"))
    )
    (net (code "239") (name "Net-(J215-Pad3)") (class "Default")
      (node (ref "J215") (pin "3") (pinfunction "3_3") (pintype "bidirectional"))
      (node (ref "J216") (pin "2") (pinfunction "2_2") (pintype "bidirectional"))
    )
    (net (code "240") (name "Net-(J216-Pad3)") (class "Default")
      (node (ref "J216") (pin "3") (pinfunction "3_3") (pintype "bidirectional"))
      (node (ref "J217") (pin "2") (pinfunction "2_2") (pintype "bidirectional"))
    )
    (net (code "241") (name "Net-(J217-Pad3)") (class "Default")
      (node (ref "J217") (pin "3") (pinfunction "3_3") (pintype "bidirectional"))
      (node (ref "J218") (pin "2") (pinfunction "2_2") (pintype "bidirectional"))
    )
    (net (code "242") (name "Net-(J218-Pad3)") (class "Default")
      (node (ref "J218") (pin "3") (pinfunction "3_3") (pintype "bidirectional"))
      (node (ref "J219") (pin "2") (pinfunction "2_2") (pintype "bidirectional"))
    )
    (net (code "243") (name "Net-(J219-Pad3)") (class "Default")
      (node (ref "J219") (pin "3") (pinfunction "3_3") (pintype "bidirectional"))
      (node (ref "J220") (pin "2") (pinfunction "2_2") (pintype "bidirectional"))
    )
    (net (code "244") (name "Net-(J220-Pad3)") (class "Default")
      (node (ref "J220") (pin "3") (pinfunction "3_3") (pintype "bidirectional"))
      (node (ref "J221") (pin "2") (pinfunction "2_2") (pintype "bidirectional"))
    )
    (net (code "245") (name "Net-(J221-Pad3)") (class "Default")
      (node (ref "J221") (pin "3") (pinfunction "3_3") (pintype "bidirectional"))
      (node (ref "J222") (pin "2") (pinfunction "2_2") (pintype "bidirectional"))
    )
    (net (code "246") (name "Net-(J222-Pad3)") (class "Default")
      (node (ref "J222") (pin "3") (pinfunction "3_3") (pintype "bidirectional"))
      (node (ref "J223") (pin "2") (pinfunction "2_2") (pintype "bidirectional"))
    )
    (net (code "247") (name "Net-(J223-Pad3)") (class "Default")
      (node (ref "J223") (pin "3") (pinfunction "3_3") (pintype "bidirectional"))
      (node (ref "J224") (pin "2") (pinfunction "2_2") (pintype "bidirectional"))
    )
    (net (code "248") (name "Net-(J225-Pad3)") (class "Default")
      (node (ref "J225") (pin "3") (pinfunction "3_3") (pintype "bidirectional"))
      (node (ref "J226") (pin "2") (pinfunction "2_2") (pintype "bidirectional"))
    )
    (net (code "249") (name "Net-(J226-Pad3)") (class "Default")
      (node (ref "J226") (pin "3") (pinfunction "3_3") (pintype "bidirectional"))
      (node (ref "J227") (pin "2") (pinfunction "2_2") (pintype "bidirectional"))
    )
    (net (code "250") (name "Net-(J227-Pad3)") (class "Default")
      (node (ref "J227") (pin "3") (pinfunction "3_3") (pintype "bidirectional"))
      (node (ref "J228") (pin "2") (pinfunction "2_2") (pintype "bidirectional"))
    )
    (net (code "251") (name "Net-(J228-Pad3)") (class "Default")
      (node (ref "J228") (pin "3") (pinfunction "3_3") (pintype "bidirectional"))
      (node (ref "J229") (pin "2") (pinfunction "2_2") (pintype "bidirectional"))
    )
    (net (code "252") (name "Net-(J229-Pad3)") (class "Default")
      (node (ref "J229") (pin "3") (pinfunction "3_3") (pintype "bidirectional"))
      (node (ref "J230") (pin "2") (pinfunction "2_2") (pintype "bidirectional"))
    )
    (net (code "253") (name "Net-(J230-Pad3)") (class "Default")
      (node (ref "J230") (pin "3") (pinfunction "3_3") (pintype "bidirectional"))
      (node (ref "J231") (pin "2") (pinfunction "2_2") (pintype "bidirectional"))
    )
    (net (code "254") (name "Net-(J231-Pad3)") (class "Default")
      (node (ref "J231") (pin "3") (pinfunction "3_3") (pintype "bidirectional"))
      (node (ref "J232") (pin "2") (pinfunction "2_2") (pintype "bidirectional"))
    )
    (net (code "255") (name "Net-(J232-Pad3)") (class "Default")
      (node (ref "J232") (pin "3") (pinfunction "3_3") (pintype "bidirectional"))
      (node (ref "J233") (pin "2") (pinfunction "2_2") (pintype "bidirectional"))
    )
    (net (code "256") (name "Net-(J233-Pad3)") (class "Default")
      (node (ref "J233") (pin "3") (pinfunction "3_3") (pintype "bidirectional"))
      (node (ref "J234") (pin "2") (pinfunction "2_2") (pintype "bidirectional"))
    )
    (net (code "257") (name "Net-(J234-Pad3)") (class "Default")
      (node (ref "J234") (pin "3") (pinfunction "3_3") (pintype "bidirectional"))
      (node (ref "J235") (pin "2") (pinfunction "2_2") (pintype "bidirectional"))
    )
    (net (code "258") (name "Net-(J235-Pad3)") (class "Default")
      (node (ref "J235") (pin "3") (pinfunction "3_3") (pintype "bidirectional"))
      (node (ref "J236") (pin "2") (pinfunction "2_2") (pintype "bidirectional"))
    )
    (net (code "259") (name "Net-(J236-Pad3)") (class "Default")
      (node (ref "J236") (pin "3") (pinfunction "3_3") (pintype "bidirectional"))
      (node (ref "J237") (pin "2") (pinfunction "2_2") (pintype "bidirectional"))
    )
    (net (code "260") (name "Net-(J237-Pad3)") (class "Default")
      (node (ref "J237") (pin "3") (pinfunction "3_3") (pintype "bidirectional"))
      (node (ref "J238") (pin "2") (pinfunction "2_2") (pintype "bidirectional"))
    )
    (net (code "261") (name "Net-(J238-Pad3)") (class "Default")
      (node (ref "J238") (pin "3") (pinfunction "3_3") (pintype "bidirectional"))
      (node (ref "J239") (pin "2") (pinfunction "2_2") (pintype "bidirectional"))
    )
    (net (code "262") (name "Net-(J239-Pad3)") (class "Default")
      (node (ref "J239") (pin "3") (pinfunction "3_3") (pintype "bidirectional"))
      (node (ref "J240") (pin "2") (pinfunction "2_2") (pintype "bidirectional"))
    )
    (net (code "263") (name "Net-(J240-Pad3)") (class "Default")
      (node (ref "J240") (pin "3") (pinfunction "3_3") (pintype "bidirectional"))
      (node (ref "J241") (pin "2") (pinfunction "2_2") (pintype "bidirectional"))
    )
    (net (code "264") (name "Net-(J241-Pad3)") (class "Default")
      (node (ref "J241") (pin "3") (pinfunction "3_3") (pintype "bidirectional"))
      (node (ref "J242") (pin "2") (pinfunction "2_2") (pintype "bidirectional"))
    )
    (net (code "265") (name "Net-(J242-Pad3)") (class "Default")
      (node (ref "J242") (pin "3") (pinfunction "3_3") (pintype "bidirectional"))
      (node (ref "J243") (pin "2") (pinfunction "2_2") (pintype "bidirectional"))
    )
    (net (code "266") (name "Net-(J243-Pad3)") (class "Default")
      (node (ref "J243") (pin "3") (pinfunction "3_3") (pintype "bidirectional"))
      (node (ref "J244") (pin "2") (pinfunction "2_2") (pintype "bidirectional"))
    )
    (net (code "267") (name "Net-(J244-Pad3)") (class "Default")
      (node (ref "J244") (pin "3") (pinfunction "3_3") (pintype "bidirectional"))
      (node (ref "J245") (pin "2") (pinfunction "2_2") (pintype "bidirectional"))
    )
    (net (code "268") (name "Net-(J245-Pad3)") (class "Default")
      (node (ref "J245") (pin "3") (pinfunction "3_3") (pintype "bidirectional"))
      (node (ref "J246") (pin "2") (pinfunction "2_2") (pintype "bidirectional"))
    )
    (net (code "269") (name "Net-(J246-Pad3)") (class "Default")
      (node (ref "J246") (pin "3") (pinfunction "3_3") (pintype "bidirectional"))
      (node (ref "J247") (pin "2") (pinfunction "2_2") (pintype "bidirectional"))
    )
    (net (code "270") (name "Net-(J247-Pad3)") (class "Default")
      (node (ref "J247") (pin "3") (pinfunction "3_3") (pintype "bidirectional"))
      (node (ref "J248") (pin "2") (pinfunction "2_2") (pintype "bidirectional"))
    )
    (net (code "271") (name "Net-(J248-Pad3)") (class "Default")
      (node (ref "J248") (pin "3") (pinfunction "3_3") (pintype "bidirectional"))
      (node (ref "J249") (pin "2") (pinfunction "2_2") (pintype "bidirectional"))
    )
    (net (code "272") (name "Net-(J249-Pad3)") (class "Default")
      (node (ref "J249") (pin "3") (pinfunction "3_3") (pintype "bidirectional"))
      (node (ref "J250") (pin "2") (pinfunction "2_2") (pintype "bidirectional"))
    )
    (net (code "273") (name "Net-(J250-Pad3)") (class "Default")
      (node (ref "J250") (pin "3") (pinfunction "3_3") (pintype "bidirectional"))
      (node (ref "J251") (pin "2") (pinfunction "2_2") (pintype "bidirectional"))
    )
    (net (code "274") (name "Net-(J251-Pad3)") (class "Default")
      (node (ref "J251") (pin "3") (pinfunction "3_3") (pintype "bidirectional"))
      (node (ref "J252") (pin "2") (pinfunction "2_2") (pintype "bidirectional"))
    )
    (net (code "275") (name "Net-(J252-Pad3)") (class "Default")
      (node (ref "J252") (pin "3") (pinfunction "3_3") (pintype "bidirectional"))
      (node (ref "J253") (pin "2") (pinfunction "2_2") (pintype "bidirectional"))
    )
    (net (code "276") (name "Net-(J253-Pad3)") (class "Default")
      (node (ref "J253") (pin "3") (pinfunction "3_3") (pintype "bidirectional"))
      (node (ref "J254") (pin "2") (pinfunction "2_2") (pintype "bidirectional"))
    )
    (net (code "277") (name "Net-(J254-Pad3)") (class "Default")
      (node (ref "J254") (pin "3") (pinfunction "3_3") (pintype "bidirectional"))
      (node (ref "J255") (pin "2") (pinfunction "2_2") (pintype "bidirectional"))
    )
    (net (code "278") (name "Net-(J255-Pad3)") (class "Default")
      (node (ref "J255") (pin "3") (pinfunction "3_3") (pintype "bidirectional"))
      (node (ref "J256") (pin "2") (pinfunction "2_2") (pintype "bidirectional"))
    )
    (net (code "279") (name "Net-(Q2-G)") (class "Default")
      (node (ref "Q2") (pin "1") (pinfunction "G_1") (pintype "passive"))
      (node (ref "U$10") (pin "G") (pinfunction "G_G") (pintype "bidirectional"))
    )
    (net (code "280") (name "Net-(Q2-S)") (class "Default")
      (node (ref "Q2") (pin "2") (pinfunction "S_2") (pintype "passive"))
      (node (ref "R28") (pin "2") (pinfunction "2_2") (pintype "bidirectional"))
      (node (ref "R29") (pin "2") (pinfunction "2_2") (pintype "bidirectional"))
      (node (ref "R3") (pin "2") (pinfunction "2_2") (pintype "bidirectional"))
      (node (ref "U$10") (pin "V-DROP") (pinfunction "V-DROP_V-DROP") (pintype "bidirectional"))
    )
    (net (code "281") (name "Net-(Q3-G)") (class "Default")
      (node (ref "Q3") (pin "1") (pinfunction "G_1") (pintype "passive"))
      (node (ref "U$9") (pin "G") (pinfunction "G_G") (pintype "bidirectional"))
    )
    (net (code "282") (name "Net-(Q3-S)") (class "Default")
      (node (ref "Q3") (pin "2") (pinfunction "S_2") (pintype "passive"))
      (node (ref "R30") (pin "2") (pinfunction "2_2") (pintype "bidirectional"))
      (node (ref "R31") (pin "2") (pinfunction "2_2") (pintype "bidirectional"))
      (node (ref "R7") (pin "2") (pinfunction "2_2") (pintype "bidirectional"))
      (node (ref "U$9") (pin "V-DROP") (pinfunction "V-DROP_V-DROP") (pintype "bidirectional"))
    )
    (net (code "283") (name "Net-(Q6-G)") (class "Default")
      (node (ref "Q6") (pin "1") (pinfunction "G_1") (pintype "passive"))
      (node (ref "U$8") (pin "G") (pinfunction "G_G") (pintype "bidirectional"))
    )
    (net (code "284") (name "Net-(Q6-S)") (class "Default")
      (node (ref "Q6") (pin "2") (pinfunction "S_2") (pintype "passive"))
      (node (ref "R14") (pin "2") (pinfunction "2_2") (pintype "bidirectional"))
      (node (ref "R32") (pin "2") (pinfunction "2_2") (pintype "bidirectional"))
      (node (ref "R33") (pin "2") (pinfunction "2_2") (pintype "bidirectional"))
      (node (ref "U$8") (pin "V-DROP") (pinfunction "V-DROP_V-DROP") (pintype "bidirectional"))
    )
    (net (code "285") (name "Net-(Q8-G)") (class "Default")
      (node (ref "Q8") (pin "1") (pinfunction "G_1") (pintype "passive"))
      (node (ref "U$7") (pin "G") (pinfunction "G_G") (pintype "bidirectional"))
    )
    (net (code "286") (name "Net-(Q8-S)") (class "Default")
      (node (ref "Q8") (pin "2") (pinfunction "S_2") (pintype "passive"))
      (node (ref "R27") (pin "2") (pinfunction "2_2") (pintype "bidirectional"))
      (node (ref "R34") (pin "2") (pinfunction "2_2") (pintype "bidirectional"))
      (node (ref "R35") (pin "2") (pinfunction "2_2") (pintype "bidirectional"))
      (node (ref "U$7") (pin "V-DROP") (pinfunction "V-DROP_V-DROP") (pintype "bidirectional"))
    )
    (net (code "287") (name "SOUND") (class "Default")
      (node (ref "JP1") (pin "5") (pinfunction "5_5") (pintype "passive"))
      (node (ref "JP3") (pin "5") (pinfunction "5_5") (pintype "passive"))
      (node (ref "U$4") (pin "85") (pinfunction "AIN0_85") (pintype "power_in"))
      (node (ref "U$5") (pin "SOUND") (pinfunction "SOUND_SOUND") (pintype "bidirectional"))
    )
    (net (code "288") (name "STREAMING") (class "Default")
      (node (ref "JP2") (pin "6") (pinfunction "6_6") (pintype "passive"))
      (node (ref "JP4") (pin "6") (pinfunction "6_6") (pintype "passive"))
      (node (ref "ONLINE/OFFLINE") (pin "2") (pinfunction "P_2") (pintype "passive"))
      (node (ref "U$5") (pin "STEAMING") (pinfunction "STREAMING_STEAMING") (pintype "bidirectional"))
    )
    (net (code "289") (name "V+") (class "Default")
      (node (ref "C1") (pin "+") (pinfunction "1_+") (pintype "bidirectional"))
      (node (ref "C2") (pin "+") (pinfunction "1_+") (pintype "bidirectional"))
      (node (ref "C3") (pin "+") (pinfunction "1_+") (pintype "bidirectional"))
      (node (ref "C4") (pin "+") (pinfunction "1_+") (pintype "bidirectional"))
      (node (ref "J1") (pin "1") (pinfunction "1_1") (pintype "bidirectional"))
      (node (ref "J10") (pin "1") (pinfunction "1_1") (pintype "bidirectional"))
      (node (ref "J100") (pin "1") (pinfunction "1_1") (pintype "bidirectional"))
      (node (ref "J101") (pin "1") (pinfunction "1_1") (pintype "bidirectional"))
      (node (ref "J102") (pin "1") (pinfunction "1_1") (pintype "bidirectional"))
      (node (ref "J103") (pin "1") (pinfunction "1_1") (pintype "bidirectional"))
      (node (ref "J104") (pin "1") (pinfunction "1_1") (pintype "bidirectional"))
      (node (ref "J105") (pin "1") (pinfunction "1_1") (pintype "bidirectional"))
      (node (ref "J106") (pin "1") (pinfunction "1_1") (pintype "bidirectional"))
      (node (ref "J107") (pin "1") (pinfunction "1_1") (pintype "bidirectional"))
      (node (ref "J108") (pin "1") (pinfunction "1_1") (pintype "bidirectional"))
      (node (ref "J109") (pin "1") (pinfunction "1_1") (pintype "bidirectional"))
      (node (ref "J11") (pin "1") (pinfunction "1_1") (pintype "bidirectional"))
      (node (ref "J110") (pin "1") (pinfunction "1_1") (pintype "bidirectional"))
      (node (ref "J111") (pin "1") (pinfunction "1_1") (pintype "bidirectional"))
      (node (ref "J112") (pin "1") (pinfunction "1_1") (pintype "bidirectional"))
      (node (ref "J113") (pin "1") (pinfunction "1_1") (pintype "bidirectional"))
      (node (ref "J114") (pin "1") (pinfunction "1_1") (pintype "bidirectional"))
      (node (ref "J115") (pin "1") (pinfunction "1_1") (pintype "bidirectional"))
      (node (ref "J116") (pin "1") (pinfunction "1_1") (pintype "bidirectional"))
      (node (ref "J117") (pin "1") (pinfunction "1_1") (pintype "bidirectional"))
      (node (ref "J118") (pin "1") (pinfunction "1_1") (pintype "bidirectional"))
      (node (ref "J119") (pin "1") (pinfunction "1_1") (pintype "bidirectional"))
      (node (ref "J12") (pin "1") (pinfunction "1_1") (pintype "bidirectional"))
      (node (ref "J120") (pin "1") (pinfunction "1_1") (pintype "bidirectional"))
      (node (ref "J121") (pin "1") (pinfunction "1_1") (pintype "bidirectional"))
      (node (ref "J122") (pin "1") (pinfunction "1_1") (pintype "bidirectional"))
      (node (ref "J123") (pin "1") (pinfunction "1_1") (pintype "bidirectional"))
      (node (ref "J124") (pin "1") (pinfunction "1_1") (pintype "bidirectional"))
      (node (ref "J125") (pin "1") (pinfunction "1_1") (pintype "bidirectional"))
      (node (ref "J126") (pin "1") (pinfunction "1_1") (pintype "bidirectional"))
      (node (ref "J127") (pin "1") (pinfunction "1_1") (pintype "bidirectional"))
      (node (ref "J128") (pin "1") (pinfunction "1_1") (pintype "bidirectional"))
      (node (ref "J129") (pin "1") (pinfunction "1_1") (pintype "bidirectional"))
      (node (ref "J13") (pin "1") (pinfunction "1_1") (pintype "bidirectional"))
      (node (ref "J130") (pin "1") (pinfunction "1_1") (pintype "bidirectional"))
      (node (ref "J131") (pin "1") (pinfunction "1_1") (pintype "bidirectional"))
      (node (ref "J132") (pin "1") (pinfunction "1_1") (pintype "bidirectional"))
      (node (ref "J133") (pin "1") (pinfunction "1_1") (pintype "bidirectional"))
      (node (ref "J134") (pin "1") (pinfunction "1_1") (pintype "bidirectional"))
      (node (ref "J135") (pin "1") (pinfunction "1_1") (pintype "bidirectional"))
      (node (ref "J136") (pin "1") (pinfunction "1_1") (pintype "bidirectional"))
      (node (ref "J137") (pin "1") (pinfunction "1_1") (pintype "bidirectional"))
      (node (ref "J138") (pin "1") (pinfunction "1_1") (pintype "bidirectional"))
      (node (ref "J139") (pin "1") (pinfunction "1_1") (pintype "bidirectional"))
      (node (ref "J14") (pin "1") (pinfunction "1_1") (pintype "bidirectional"))
      (node (ref "J140") (pin "1") (pinfunction "1_1") (pintype "bidirectional"))
      (node (ref "J141") (pin "1") (pinfunction "1_1") (pintype "bidirectional"))
      (node (ref "J142") (pin "1") (pinfunction "1_1") (pintype "bidirectional"))
      (node (ref "J143") (pin "1") (pinfunction "1_1") (pintype "bidirectional"))
      (node (ref "J144") (pin "1") (pinfunction "1_1") (pintype "bidirectional"))
      (node (ref "J145") (pin "1") (pinfunction "1_1") (pintype "bidirectional"))
      (node (ref "J146") (pin "1") (pinfunction "1_1") (pintype "bidirectional"))
      (node (ref "J147") (pin "1") (pinfunction "1_1") (pintype "bidirectional"))
      (node (ref "J148") (pin "1") (pinfunction "1_1") (pintype "bidirectional"))
      (node (ref "J149") (pin "1") (pinfunction "1_1") (pintype "bidirectional"))
      (node (ref "J15") (pin "1") (pinfunction "1_1") (pintype "bidirectional"))
      (node (ref "J150") (pin "1") (pinfunction "1_1") (pintype "bidirectional"))
      (node (ref "J151") (pin "1") (pinfunction "1_1") (pintype "bidirectional"))
      (node (ref "J152") (pin "1") (pinfunction "1_1") (pintype "bidirectional"))
      (node (ref "J153") (pin "1") (pinfunction "1_1") (pintype "bidirectional"))
      (node (ref "J154") (pin "1") (pinfunction "1_1") (pintype "bidirectional"))
      (node (ref "J155") (pin "1") (pinfunction "1_1") (pintype "bidirectional"))
      (node (ref "J156") (pin "1") (pinfunction "1_1") (pintype "bidirectional"))
      (node (ref "J157") (pin "1") (pinfunction "1_1") (pintype "bidirectional"))
      (node (ref "J158") (pin "1") (pinfunction "1_1") (pintype "bidirectional"))
      (node (ref "J159") (pin "1") (pinfunction "1_1") (pintype "bidirectional"))
      (node (ref "J16") (pin "1") (pinfunction "1_1") (pintype "bidirectional"))
      (node (ref "J160") (pin "1") (pinfunction "1_1") (pintype "bidirectional"))
      (node (ref "J161") (pin "1") (pinfunction "1_1") (pintype "bidirectional"))
      (node (ref "J162") (pin "1") (pinfunction "1_1") (pintype "bidirectional"))
      (node (ref "J163") (pin "1") (pinfunction "1_1") (pintype "bidirectional"))
      (node (ref "J164") (pin "1") (pinfunction "1_1") (pintype "bidirectional"))
      (node (ref "J165") (pin "1") (pinfunction "1_1") (pintype "bidirectional"))
      (node (ref "J166") (pin "1") (pinfunction "1_1") (pintype "bidirectional"))
      (node (ref "J167") (pin "1") (pinfunction "1_1") (pintype "bidirectional"))
      (node (ref "J168") (pin "1") (pinfunction "1_1") (pintype "bidirectional"))
      (node (ref "J169") (pin "1") (pinfunction "1_1") (pintype "bidirectional"))
      (node (ref "J17") (pin "1") (pinfunction "1_1") (pintype "bidirectional"))
      (node (ref "J170") (pin "1") (pinfunction "1_1") (pintype "bidirectional"))
      (node (ref "J171") (pin "1") (pinfunction "1_1") (pintype "bidirectional"))
      (node (ref "J172") (pin "1") (pinfunction "1_1") (pintype "bidirectional"))
      (node (ref "J173") (pin "1") (pinfunction "1_1") (pintype "bidirectional"))
      (node (ref "J174") (pin "1") (pinfunction "1_1") (pintype "bidirectional"))
      (node (ref "J175") (pin "1") (pinfunction "1_1") (pintype "bidirectional"))
      (node (ref "J176") (pin "1") (pinfunction "1_1") (pintype "bidirectional"))
      (node (ref "J177") (pin "1") (pinfunction "1_1") (pintype "bidirectional"))
      (node (ref "J178") (pin "1") (pinfunction "1_1") (pintype "bidirectional"))
      (node (ref "J179") (pin "1") (pinfunction "1_1") (pintype "bidirectional"))
      (node (ref "J18") (pin "1") (pinfunction "1_1") (pintype "bidirectional"))
      (node (ref "J180") (pin "1") (pinfunction "1_1") (pintype "bidirectional"))
      (node (ref "J181") (pin "1") (pinfunction "1_1") (pintype "bidirectional"))
      (node (ref "J182") (pin "1") (pinfunction "1_1") (pintype "bidirectional"))
      (node (ref "J183") (pin "1") (pinfunction "1_1") (pintype "bidirectional"))
      (node (ref "J184") (pin "1") (pinfunction "1_1") (pintype "bidirectional"))
      (node (ref "J185") (pin "1") (pinfunction "1_1") (pintype "bidirectional"))
      (node (ref "J186") (pin "1") (pinfunction "1_1") (pintype "bidirectional"))
      (node (ref "J187") (pin "1") (pinfunction "1_1") (pintype "bidirectional"))
      (node (ref "J188") (pin "1") (pinfunction "1_1") (pintype "bidirectional"))
      (node (ref "J189") (pin "1") (pinfunction "1_1") (pintype "bidirectional"))
      (node (ref "J19") (pin "1") (pinfunction "1_1") (pintype "bidirectional"))
      (node (ref "J190") (pin "1") (pinfunction "1_1") (pintype "bidirectional"))
      (node (ref "J191") (pin "1") (pinfunction "1_1") (pintype "bidirectional"))
      (node (ref "J192") (pin "1") (pinfunction "1_1") (pintype "bidirectional"))
      (node (ref "J193") (pin "1") (pinfunction "1_1") (pintype "bidirectional"))
      (node (ref "J194") (pin "1") (pinfunction "1_1") (pintype "bidirectional"))
      (node (ref "J195") (pin "1") (pinfunction "1_1") (pintype "bidirectional"))
      (node (ref "J196") (pin "1") (pinfunction "1_1") (pintype "bidirectional"))
      (node (ref "J197") (pin "1") (pinfunction "1_1") (pintype "bidirectional"))
      (node (ref "J198") (pin "1") (pinfunction "1_1") (pintype "bidirectional"))
      (node (ref "J199") (pin "1") (pinfunction "1_1") (pintype "bidirectional"))
      (node (ref "J2") (pin "1") (pinfunction "1_1") (pintype "bidirectional"))
      (node (ref "J20") (pin "1") (pinfunction "1_1") (pintype "bidirectional"))
      (node (ref "J200") (pin "1") (pinfunction "1_1") (pintype "bidirectional"))
      (node (ref "J201") (pin "1") (pinfunction "1_1") (pintype "bidirectional"))
      (node (ref "J202") (pin "1") (pinfunction "1_1") (pintype "bidirectional"))
      (node (ref "J203") (pin "1") (pinfunction "1_1") (pintype "bidirectional"))
      (node (ref "J204") (pin "1") (pinfunction "1_1") (pintype "bidirectional"))
      (node (ref "J205") (pin "1") (pinfunction "1_1") (pintype "bidirectional"))
      (node (ref "J206") (pin "1") (pinfunction "1_1") (pintype "bidirectional"))
      (node (ref "J207") (pin "1") (pinfunction "1_1") (pintype "bidirectional"))
      (node (ref "J208") (pin "1") (pinfunction "1_1") (pintype "bidirectional"))
      (node (ref "J209") (pin "1") (pinfunction "1_1") (pintype "bidirectional"))
      (node (ref "J21") (pin "1") (pinfunction "1_1") (pintype "bidirectional"))
      (node (ref "J210") (pin "1") (pinfunction "1_1") (pintype "bidirectional"))
      (node (ref "J211") (pin "1") (pinfunction "1_1") (pintype "bidirectional"))
      (node (ref "J212") (pin "1") (pinfunction "1_1") (pintype "bidirectional"))
      (node (ref "J213") (pin "1") (pinfunction "1_1") (pintype "bidirectional"))
      (node (ref "J214") (pin "1") (pinfunction "1_1") (pintype "bidirectional"))
      (node (ref "J215") (pin "1") (pinfunction "1_1") (pintype "bidirectional"))
      (node (ref "J216") (pin "1") (pinfunction "1_1") (pintype "bidirectional"))
      (node (ref "J217") (pin "1") (pinfunction "1_1") (pintype "bidirectional"))
      (node (ref "J218") (pin "1") (pinfunction "1_1") (pintype "bidirectional"))
      (node (ref "J219") (pin "1") (pinfunction "1_1") (pintype "bidirectional"))
      (node (ref "J22") (pin "1") (pinfunction "1_1") (pintype "bidirectional"))
      (node (ref "J220") (pin "1") (pinfunction "1_1") (pintype "bidirectional"))
      (node (ref "J221") (pin "1") (pinfunction "1_1") (pintype "bidirectional"))
      (node (ref "J222") (pin "1") (pinfunction "1_1") (pintype "bidirectional"))
      (node (ref "J223") (pin "1") (pinfunction "1_1") (pintype "bidirectional"))
      (node (ref "J224") (pin "1") (pinfunction "1_1") (pintype "bidirectional"))
      (node (ref "J225") (pin "1") (pinfunction "1_1") (pintype "bidirectional"))
      (node (ref "J226") (pin "1") (pinfunction "1_1") (pintype "bidirectional"))
      (node (ref "J227") (pin "1") (pinfunction "1_1") (pintype "bidirectional"))
      (node (ref "J228") (pin "1") (pinfunction "1_1") (pintype "bidirectional"))
      (node (ref "J229") (pin "1") (pinfunction "1_1") (pintype "bidirectional"))
      (node (ref "J23") (pin "1") (pinfunction "1_1") (pintype "bidirectional"))
      (node (ref "J230") (pin "1") (pinfunction "1_1") (pintype "bidirectional"))
      (node (ref "J231") (pin "1") (pinfunction "1_1") (pintype "bidirectional"))
      (node (ref "J232") (pin "1") (pinfunction "1_1") (pintype "bidirectional"))
      (node (ref "J233") (pin "1") (pinfunction "1_1") (pintype "bidirectional"))
      (node (ref "J234") (pin "1") (pinfunction "1_1") (pintype "bidirectional"))
      (node (ref "J235") (pin "1") (pinfunction "1_1") (pintype "bidirectional"))
      (node (ref "J236") (pin "1") (pinfunction "1_1") (pintype "bidirectional"))
      (node (ref "J237") (pin "1") (pinfunction "1_1") (pintype "bidirectional"))
      (node (ref "J238") (pin "1") (pinfunction "1_1") (pintype "bidirectional"))
      (node (ref "J239") (pin "1") (pinfunction "1_1") (pintype "bidirectional"))
      (node (ref "J24") (pin "1") (pinfunction "1_1") (pintype "bidirectional"))
      (node (ref "J240") (pin "1") (pinfunction "1_1") (pintype "bidirectional"))
      (node (ref "J241") (pin "1") (pinfunction "1_1") (pintype "bidirectional"))
      (node (ref "J242") (pin "1") (pinfunction "1_1") (pintype "bidirectional"))
      (node (ref "J243") (pin "1") (pinfunction "1_1") (pintype "bidirectional"))
      (node (ref "J244") (pin "1") (pinfunction "1_1") (pintype "bidirectional"))
      (node (ref "J245") (pin "1") (pinfunction "1_1") (pintype "bidirectional"))
      (node (ref "J246") (pin "1") (pinfunction "1_1") (pintype "bidirectional"))
      (node (ref "J247") (pin "1") (pinfunction "1_1") (pintype "bidirectional"))
      (node (ref "J248") (pin "1") (pinfunction "1_1") (pintype "bidirectional"))
      (node (ref "J249") (pin "1") (pinfunction "1_1") (pintype "bidirectional"))
      (node (ref "J25") (pin "1") (pinfunction "1_1") (pintype "bidirectional"))
      (node (ref "J250") (pin "1") (pinfunction "1_1") (pintype "bidirectional"))
      (node (ref "J251") (pin "1") (pinfunction "1_1") (pintype "bidirectional"))
      (node (ref "J252") (pin "1") (pinfunction "1_1") (pintype "bidirectional"))
      (node (ref "J253") (pin "1") (pinfunction "1_1") (pintype "bidirectional"))
      (node (ref "J254") (pin "1") (pinfunction "1_1") (pintype "bidirectional"))
      (node (ref "J255") (pin "1") (pinfunction "1_1") (pintype "bidirectional"))
      (node (ref "J256") (pin "1") (pinfunction "1_1") (pintype "bidirectional"))
      (node (ref "J26") (pin "1") (pinfunction "1_1") (pintype "bidirectional"))
      (node (ref "J27") (pin "1") (pinfunction "1_1") (pintype "bidirectional"))
      (node (ref "J28") (pin "1") (pinfunction "1_1") (pintype "bidirectional"))
      (node (ref "J29") (pin "1") (pinfunction "1_1") (pintype "bidirectional"))
      (node (ref "J3") (pin "1") (pinfunction "1_1") (pintype "bidirectional"))
      (node (ref "J30") (pin "1") (pinfunction "1_1") (pintype "bidirectional"))
      (node (ref "J31") (pin "1") (pinfunction "1_1") (pintype "bidirectional"))
      (node (ref "J32") (pin "1") (pinfunction "1_1") (pintype "bidirectional"))
      (node (ref "J33") (pin "1") (pinfunction "1_1") (pintype "bidirectional"))
      (node (ref "J34") (pin "1") (pinfunction "1_1") (pintype "bidirectional"))
      (node (ref "J35") (pin "1") (pinfunction "1_1") (pintype "bidirectional"))
      (node (ref "J36") (pin "1") (pinfunction "1_1") (pintype "bidirectional"))
      (node (ref "J37") (pin "1") (pinfunction "1_1") (pintype "bidirectional"))
      (node (ref "J38") (pin "1") (pinfunction "1_1") (pintype "bidirectional"))
      (node (ref "J39") (pin "1") (pinfunction "1_1") (pintype "bidirectional"))
      (node (ref "J4") (pin "1") (pinfunction "1_1") (pintype "bidirectional"))
      (node (ref "J40") (pin "1") (pinfunction "1_1") (pintype "bidirectional"))
      (node (ref "J41") (pin "1") (pinfunction "1_1") (pintype "bidirectional"))
      (node (ref "J42") (pin "1") (pinfunction "1_1") (pintype "bidirectional"))
      (node (ref "J43") (pin "1") (pinfunction "1_1") (pintype "bidirectional"))
      (node (ref "J44") (pin "1") (pinfunction "1_1") (pintype "bidirectional"))
      (node (ref "J45") (pin "1") (pinfunction "1_1") (pintype "bidirectional"))
      (node (ref "J46") (pin "1") (pinfunction "1_1") (pintype "bidirectional"))
      (node (ref "J47") (pin "1") (pinfunction "1_1") (pintype "bidirectional"))
      (node (ref "J48") (pin "1") (pinfunction "1_1") (pintype "bidirectional"))
      (node (ref "J49") (pin "1") (pinfunction "1_1") (pintype "bidirectional"))
      (node (ref "J5") (pin "1") (pinfunction "1_1") (pintype "bidirectional"))
      (node (ref "J50") (pin "1") (pinfunction "1_1") (pintype "bidirectional"))
      (node (ref "J51") (pin "1") (pinfunction "1_1") (pintype "bidirectional"))
      (node (ref "J52") (pin "1") (pinfunction "1_1") (pintype "bidirectional"))
      (node (ref "J53") (pin "1") (pinfunction "1_1") (pintype "bidirectional"))
      (node (ref "J54") (pin "1") (pinfunction "1_1") (pintype "bidirectional"))
      (node (ref "J55") (pin "1") (pinfunction "1_1") (pintype "bidirectional"))
      (node (ref "J56") (pin "1") (pinfunction "1_1") (pintype "bidirectional"))
      (node (ref "J57") (pin "1") (pinfunction "1_1") (pintype "bidirectional"))
      (node (ref "J58") (pin "1") (pinfunction "1_1") (pintype "bidirectional"))
      (node (ref "J59") (pin "1") (pinfunction "1_1") (pintype "bidirectional"))
      (node (ref "J6") (pin "1") (pinfunction "1_1") (pintype "bidirectional"))
      (node (ref "J60") (pin "1") (pinfunction "1_1") (pintype "bidirectional"))
      (node (ref "J61") (pin "1") (pinfunction "1_1") (pintype "bidirectional"))
      (node (ref "J62") (pin "1") (pinfunction "1_1") (pintype "bidirectional"))
      (node (ref "J63") (pin "1") (pinfunction "1_1") (pintype "bidirectional"))
      (node (ref "J64") (pin "1") (pinfunction "1_1") (pintype "bidirectional"))
      (node (ref "J65") (pin "1") (pinfunction "1_1") (pintype "bidirectional"))
      (node (ref "J66") (pin "1") (pinfunction "1_1") (pintype "bidirectional"))
      (node (ref "J67") (pin "1") (pinfunction "1_1") (pintype "bidirectional"))
      (node (ref "J68") (pin "1") (pinfunction "1_1") (pintype "bidirectional"))
      (node (ref "J69") (pin "1") (pinfunction "1_1") (pintype "bidirectional"))
      (node (ref "J7") (pin "1") (pinfunction "1_1") (pintype "bidirectional"))
      (node (ref "J70") (pin "1") (pinfunction "1_1") (pintype "bidirectional"))
      (node (ref "J71") (pin "1") (pinfunction "1_1") (pintype "bidirectional"))
      (node (ref "J72") (pin "1") (pinfunction "1_1") (pintype "bidirectional"))
      (node (ref "J73") (pin "1") (pinfunction "1_1") (pintype "bidirectional"))
      (node (ref "J74") (pin "1") (pinfunction "1_1") (pintype "bidirectional"))
      (node (ref "J75") (pin "1") (pinfunction "1_1") (pintype "bidirectional"))
      (node (ref "J76") (pin "1") (pinfunction "1_1") (pintype "bidirectional"))
      (node (ref "J77") (pin "1") (pinfunction "1_1") (pintype "bidirectional"))
      (node (ref "J78") (pin "1") (pinfunction "1_1") (pintype "bidirectional"))
      (node (ref "J79") (pin "1") (pinfunction "1_1") (pintype "bidirectional"))
      (node (ref "J8") (pin "1") (pinfunction "1_1") (pintype "bidirectional"))
      (node (ref "J80") (pin "1") (pinfunction "1_1") (pintype "bidirectional"))
      (node (ref "J81") (pin "1") (pinfunction "1_1") (pintype "bidirectional"))
      (node (ref "J82") (pin "1") (pinfunction "1_1") (pintype "bidirectional"))
      (node (ref "J83") (pin "1") (pinfunction "1_1") (pintype "bidirectional"))
      (node (ref "J84") (pin "1") (pinfunction "1_1") (pintype "bidirectional"))
      (node (ref "J85") (pin "1") (pinfunction "1_1") (pintype "bidirectional"))
      (node (ref "J86") (pin "1") (pinfunction "1_1") (pintype "bidirectional"))
      (node (ref "J87") (pin "1") (pinfunction "1_1") (pintype "bidirectional"))
      (node (ref "J88") (pin "1") (pinfunction "1_1") (pintype "bidirectional"))
      (node (ref "J89") (pin "1") (pinfunction "1_1") (pintype "bidirectional"))
      (node (ref "J9") (pin "1") (pinfunction "1_1") (pintype "bidirectional"))
      (node (ref "J90") (pin "1") (pinfunction "1_1") (pintype "bidirectional"))
      (node (ref "J91") (pin "1") (pinfunction "1_1") (pintype "bidirectional"))
      (node (ref "J92") (pin "1") (pinfunction "1_1") (pintype "bidirectional"))
      (node (ref "J93") (pin "1") (pinfunction "1_1") (pintype "bidirectional"))
      (node (ref "J94") (pin "1") (pinfunction "1_1") (pintype "bidirectional"))
      (node (ref "J95") (pin "1") (pinfunction "1_1") (pintype "bidirectional"))
      (node (ref "J96") (pin "1") (pinfunction "1_1") (pintype "bidirectional"))
      (node (ref "J97") (pin "1") (pinfunction "1_1") (pintype "bidirectional"))
      (node (ref "J98") (pin "1") (pinfunction "1_1") (pintype "bidirectional"))
      (node (ref "J99") (pin "1") (pinfunction "1_1") (pintype "bidirectional"))
      (node (ref "Q2") (pin "3") (pinfunction "D_3") (pintype "passive"))
      (node (ref "Q3") (pin "3") (pinfunction "D_3") (pintype "passive"))
      (node (ref "Q6") (pin "3") (pinfunction "D_3") (pintype "passive"))
      (node (ref "Q8") (pin "3") (pinfunction "D_3") (pintype "passive"))
      (node (ref "TER_CONN") (pin "1_1") (pinfunction "1_1_1") (pintype "bidirectional"))
      (node (ref "TER_CONN") (pin "1_2") (pinfunction "1_1_2") (pintype "bidirectional"))
      (node (ref "TER_CONN") (pin "1_3") (pinfunction "1_1_3") (pintype "bidirectional"))
      (node (ref "TER_CONN") (pin "1_4") (pinfunction "1_1_4") (pintype "bidirectional"))
    )
    (net (code "290") (name "XOUT") (class "Default")
      (node (ref "JP1") (pin "12") (pinfunction "12_12") (pintype "passive"))
      (node (ref "JP3") (pin "12") (pinfunction "12_12") (pintype "passive"))
      (node (ref "U$4") (pin "86") (pinfunction "AIN1_86") (pintype "passive"))
      (node (ref "U$5") (pin "XOUT") (pinfunction "XOUT_XOUT") (pintype "bidirectional"))
    )
    (net (code "291") (name "YOUT") (class "Default")
      (node (ref "JP1") (pin "11") (pinfunction "11_11") (pintype "passive"))
      (node (ref "JP3") (pin "11") (pinfunction "11_11") (pintype "passive"))
      (node (ref "U$4") (pin "84") (pinfunction "AIN3_84") (pintype "passive"))
      (node (ref "U$5") (pin "YOUT") (pinfunction "YOUT_YOUT") (pintype "bidirectional"))
    )
    (net (code "292") (name "ZOUT") (class "Default")
      (node (ref "JP1") (pin "6") (pinfunction "6_6") (pintype "passive"))
      (node (ref "JP3") (pin "6") (pinfunction "6_6") (pintype "passive"))
      (node (ref "U$4") (pin "82") (pinfunction "AIN5_82") (pintype "passive"))
      (node (ref "U$5") (pin "ZOUT") (pinfunction "ZOUT_ZOUT") (pintype "bidirectional"))
    )
    (net (code "293") (name "unconnected-(J64-Pad3)") (class "Default")
      (node (ref "J64") (pin "3") (pinfunction "3_3") (pintype "bidirectional"))
    )
    (net (code "294") (name "unconnected-(J128-Pad3)") (class "Default")
      (node (ref "J128") (pin "3") (pinfunction "3_3") (pintype "bidirectional"))
    )
    (net (code "295") (name "unconnected-(J192-Pad3)") (class "Default")
      (node (ref "J192") (pin "3") (pinfunction "3_3") (pintype "bidirectional"))
    )
    (net (code "296") (name "unconnected-(J256-Pad3)") (class "Default")
      (node (ref "J256") (pin "3") (pinfunction "3_3") (pintype "bidirectional"))
    )
    (net (code "297") (name "unconnected-(ONLINE/OFFLINE-O-Pad1)") (class "Default")
      (node (ref "ONLINE/OFFLINE") (pin "1") (pinfunction "O_1") (pintype "passive"))
    )
    (net (code "298") (name "unconnected-(U$2-PadP$1)") (class "Default")
      (node (ref "U$2") (pin "P$1") (pinfunction "P$1_P$1") (pintype "bidirectional"))
    )
    (net (code "299") (name "unconnected-(U$3-PadP$1)") (class "Default")
      (node (ref "U$3") (pin "P$1") (pinfunction "P$1_P$1") (pintype "bidirectional"))
    )
    (net (code "300") (name "unconnected-(U$4-AIN4-Pad79)") (class "Default")
      (node (ref "U$4") (pin "79") (pinfunction "AIN4_79") (pintype "passive"))
    )
    (net (code "301") (name "unconnected-(U$4-AIN6-Pad81)") (class "Default")
      (node (ref "U$4") (pin "81") (pinfunction "AIN6_81") (pintype "passive"))
    )
    (net (code "302") (name "unconnected-(U$4-CLKOUT2-Pad87)") (class "Default")
      (node (ref "U$4") (pin "87") (pinfunction "CLKOUT2_87") (pintype "input"))
    )
    (net (code "303") (name "unconnected-(U$4-EHRPWM1A-Pad60)") (class "Default")
      (node (ref "U$4") (pin "60") (pinfunction "EHRPWM1A_60") (pintype "passive"))
    )
    (net (code "304") (name "unconnected-(U$4-EHRPWM1B-Pad62)") (class "Default")
      (node (ref "U$4") (pin "62") (pinfunction "EHRPWM1B_62") (pintype "passive"))
    )
    (net (code "305") (name "unconnected-(U$4-EHRPWM2A-Pad19)") (class "Default")
      (node (ref "U$4") (pin "19") (pinfunction "EHRPWM2A_19") (pintype "passive"))
    )
    (net (code "306") (name "unconnected-(U$4-EHRPWM2B-Pad13)") (class "Default")
      (node (ref "U$4") (pin "13") (pinfunction "EHRPWM2B_13") (pintype "passive"))
    )
    (net (code "307") (name "unconnected-(U$4-GNDA_ADC-Pad80)") (class "Default")
      (node (ref "U$4") (pin "80") (pinfunction "GNDA_ADC_80") (pintype "passive"))
    )
    (net (code "308") (name "unconnected-(U$4-GPIO0_7-Pad88)") (class "Default")
      (node (ref "U$4") (pin "88") (pinfunction "GPIO0_7_88") (pintype "passive"))
    )
    (net (code "309") (name "unconnected-(U$4-GPIO0_26-Pad14)") (class "Default")
      (node (ref "U$4") (pin "14") (pinfunction "GPIO0_26_14") (pintype "passive"))
    )
    (net (code "310") (name "unconnected-(U$4-GPIO0_27-Pad17)") (class "Default")
      (node (ref "U$4") (pin "17") (pinfunction "GPIO0_27_17") (pintype "passive"))
    )
    (net (code "311") (name "unconnected-(U$4-GPIO1_0-Pad25)") (class "Default")
      (node (ref "U$4") (pin "25") (pinfunction "GPIO1_0_25") (pintype "passive"))
    )
    (net (code "312") (name "unconnected-(U$4-GPIO1_1-Pad24)") (class "Default")
      (node (ref "U$4") (pin "24") (pinfunction "GPIO1_1_24") (pintype "passive"))
    )
    (net (code "313") (name "unconnected-(U$4-GPIO1_2-Pad5)") (class "Default")
      (node (ref "U$4") (pin "5") (pinfunction "GPIO1_2_5") (pintype "passive"))
    )
    (net (code "314") (name "unconnected-(U$4-GPIO1_3-Pad6)") (class "Default")
      (node (ref "U$4") (pin "6") (pinfunction "GPIO1_3_6") (pintype "passive"))
    )
    (net (code "315") (name "unconnected-(U$4-GPIO1_4-Pad23)") (class "Default")
      (node (ref "U$4") (pin "23") (pinfunction "GPIO1_4_23") (pintype "passive"))
    )
    (net (code "316") (name "unconnected-(U$4-GPIO1_5-Pad22)") (class "Default")
      (node (ref "U$4") (pin "22") (pinfunction "GPIO1_5_22") (pintype "passive"))
    )
    (net (code "317") (name "unconnected-(U$4-GPIO1_6-Pad3)") (class "Default")
      (node (ref "U$4") (pin "3") (pinfunction "GPIO1_6_3") (pintype "passive"))
    )
    (net (code "318") (name "unconnected-(U$4-GPIO1_7-Pad4)") (class "Default")
      (node (ref "U$4") (pin "4") (pinfunction "GPIO1_7_4") (pintype "passive"))
    )
    (net (code "319") (name "unconnected-(U$4-GPIO1_12-Pad12)") (class "Default")
      (node (ref "U$4") (pin "12") (pinfunction "GPIO1_12_12") (pintype "passive"))
    )
    (net (code "320") (name "unconnected-(U$4-GPIO1_13-Pad11)") (class "Default")
      (node (ref "U$4") (pin "11") (pinfunction "GPIO1_13_11") (pintype "passive"))
    )
    (net (code "321") (name "unconnected-(U$4-GPIO1_14-Pad16)") (class "Default")
      (node (ref "U$4") (pin "16") (pinfunction "GPIO1_14_16") (pintype "passive"))
    )
    (net (code "322") (name "unconnected-(U$4-GPIO1_15-Pad15)") (class "Default")
      (node (ref "U$4") (pin "15") (pinfunction "GPIO1_15_15") (pintype "passive"))
    )
    (net (code "323") (name "unconnected-(U$4-GPIO1_16-Pad61)") (class "Default")
      (node (ref "U$4") (pin "61") (pinfunction "GPIO1_16_61") (pintype "passive"))
    )
    (net (code "324") (name "unconnected-(U$4-GPIO1_17-Pad69)") (class "Default")
      (node (ref "U$4") (pin "69") (pinfunction "GPIO1_17_69") (pintype "passive"))
    )
    (net (code "325") (name "unconnected-(U$4-GPIO1_28-Pad58)") (class "Default")
      (node (ref "U$4") (pin "58") (pinfunction "GPIO1_28_58") (pintype "passive"))
    )
    (net (code "326") (name "unconnected-(U$4-GPIO1_29-Pad26)") (class "Default")
      (node (ref "U$4") (pin "26") (pinfunction "GPIO1_29_26") (pintype "passive"))
    )
    (net (code "327") (name "unconnected-(U$4-GPIO1_30-Pad21)") (class "Default")
      (node (ref "U$4") (pin "21") (pinfunction "GPIO1_30_21") (pintype "passive"))
    )
    (net (code "328") (name "unconnected-(U$4-GPIO1_31-Pad20)") (class "Default")
      (node (ref "U$4") (pin "20") (pinfunction "GPIO1_31_20") (pintype "passive"))
    )
    (net (code "329") (name "unconnected-(U$4-GPIO2_1-Pad18)") (class "Default")
      (node (ref "U$4") (pin "18") (pinfunction "GPIO2_1_18") (pintype "passive"))
    )
    (net (code "330") (name "unconnected-(U$4-GPIO2_22-Pad27)") (class "Default")
      (node (ref "U$4") (pin "27") (pinfunction "GPIO2_22_27") (pintype "passive"))
    )
    (net (code "331") (name "unconnected-(U$4-GPIO2_23-Pad29)") (class "Default")
      (node (ref "U$4") (pin "29") (pinfunction "GPIO2_23_29") (pintype "passive"))
    )
    (net (code "332") (name "unconnected-(U$4-GPIO2_24-Pad28)") (class "Default")
      (node (ref "U$4") (pin "28") (pinfunction "GPIO2_24_28") (pintype "passive"))
    )
    (net (code "333") (name "unconnected-(U$4-GPIO2_25-Pad30)") (class "Default")
      (node (ref "U$4") (pin "30") (pinfunction "GPIO2_25_30") (pintype "passive"))
    )
    (net (code "334") (name "unconnected-(U$4-GPIO3_19-Pad73)") (class "Default")
      (node (ref "U$4") (pin "73") (pinfunction "GPIO3_19_73") (pintype "passive"))
    )
    (net (code "335") (name "unconnected-(U$4-GPIO3_21-Pad71)") (class "Default")
      (node (ref "U$4") (pin "71") (pinfunction "GPIO3_21_71") (pintype "passive"))
    )
    (net (code "336") (name "unconnected-(U$4-I2C1_SCL-Pad63)") (class "Default")
      (node (ref "U$4") (pin "63") (pinfunction "I2C1_SCL_63") (pintype "passive"))
    )
    (net (code "337") (name "unconnected-(U$4-I2C1_SDA-Pad64)") (class "Default")
      (node (ref "U$4") (pin "64") (pinfunction "I2C1_SDA_64") (pintype "passive"))
    )
    (net (code "338") (name "unconnected-(U$4-I2C2_SCL-Pad65)") (class "Default")
      (node (ref "U$4") (pin "65") (pinfunction "I2C2_SCL_65") (pintype "passive"))
    )
    (net (code "339") (name "unconnected-(U$4-I2C2_SDA-Pad66)") (class "Default")
      (node (ref "U$4") (pin "66") (pinfunction "I2C2_SDA_66") (pintype "passive"))
    )
    (net (code "340") (name "unconnected-(U$4-PWR_BUT-Pad55)") (class "Default")
      (node (ref "U$4") (pin "55") (pinfunction "PWR_BUT_55") (pintype "passive"))
    )
    (net (code "341") (name "unconnected-(U$4-SPI1_CS0-Pad74)") (class "Default")
      (node (ref "U$4") (pin "74") (pinfunction "SPI1_CS0_74") (pintype "passive"))
    )
    (net (code "342") (name "unconnected-(U$4-SPI1_DI-Pad76)") (class "Default")
      (node (ref "U$4") (pin "76") (pinfunction "SPI1_DI_76") (pintype "passive"))
    )
    (net (code "343") (name "unconnected-(U$4-SPI1_DO-Pad75)") (class "Default")
      (node (ref "U$4") (pin "75") (pinfunction "SPI1_DO_75") (pintype "passive"))
    )
    (net (code "344") (name "unconnected-(U$4-SPI1_SCLK-Pad77)") (class "Default")
      (node (ref "U$4") (pin "77") (pinfunction "SPI1_SCLK_77") (pintype "passive"))
    )
    (net (code "345") (name "unconnected-(U$4-SYS_5V-Pad54)") (class "Default")
      (node (ref "U$4") (pin "54") (pinfunction "SYS_5V_54") (pintype "passive"))
    )
    (net (code "346") (name "unconnected-(U$4-SYS_RESETN-Pad56)") (class "Default")
      (node (ref "U$4") (pin "56") (pinfunction "SYS_RESETN_56") (pintype "passive"))
    )
    (net (code "347") (name "unconnected-(U$4-TIMER4-Pad7)") (class "Default")
      (node (ref "U$4") (pin "7") (pinfunction "TIMER4_7") (pintype "passive"))
    )
    (net (code "348") (name "unconnected-(U$4-TIMER5-Pad9)") (class "Default")
      (node (ref "U$4") (pin "9") (pinfunction "TIMER5_9") (pintype "passive"))
    )
    (net (code "349") (name "unconnected-(U$4-TIMER6-Pad10)") (class "Default")
      (node (ref "U$4") (pin "10") (pinfunction "TIMER6_10") (pintype "passive"))
    )
    (net (code "350") (name "unconnected-(U$4-TIMER7-Pad8)") (class "Default")
      (node (ref "U$4") (pin "8") (pinfunction "TIMER7_8") (pintype "passive"))
    )
    (net (code "351") (name "unconnected-(U$4-UART1_RXD-Pad72)") (class "Default")
      (node (ref "U$4") (pin "72") (pinfunction "UART1_RXD_72") (pintype "passive"))
    )
    (net (code "352") (name "unconnected-(U$4-UART1_TXD-Pad70)") (class "Default")
      (node (ref "U$4") (pin "70") (pinfunction "UART1_TXD_70") (pintype "passive"))
    )
    (net (code "353") (name "unconnected-(U$4-UART2_RXD-Pad68)") (class "Default")
      (node (ref "U$4") (pin "68") (pinfunction "UART2_RXD_68") (pintype "passive"))
    )
    (net (code "354") (name "unconnected-(U$4-UART2_TXD-Pad67)") (class "Default")
      (node (ref "U$4") (pin "67") (pinfunction "UART2_TXD_67") (pintype "passive"))
    )
    (net (code "355") (name "unconnected-(U$4-UART3_CTSN-Pad36)") (class "Default")
      (node (ref "U$4") (pin "36") (pinfunction "UART3_CTSN_36") (pintype "passive"))
    )
    (net (code "356") (name "unconnected-(U$4-UART3_RTSN-Pad34)") (class "Default")
      (node (ref "U$4") (pin "34") (pinfunction "UART3_RTSN_34") (pintype "passive"))
    )
    (net (code "357") (name "unconnected-(U$4-UART4_CTSN-Pad35)") (class "Default")
      (node (ref "U$4") (pin "35") (pinfunction "UART4_CTSN_35") (pintype "passive"))
    )
    (net (code "358") (name "unconnected-(U$4-UART4_RTSN-Pad33)") (class "Default")
      (node (ref "U$4") (pin "33") (pinfunction "UART4_RTSN_33") (pintype "passive"))
    )
    (net (code "359") (name "unconnected-(U$4-UART4_RXD-Pad57)") (class "Default")
      (node (ref "U$4") (pin "57") (pinfunction "UART4_RXD_57") (pintype "passive"))
    )
    (net (code "360") (name "unconnected-(U$4-UART4_TXD-Pad59)") (class "Default")
      (node (ref "U$4") (pin "59") (pinfunction "UART4_TXD_59") (pintype "passive"))
    )
    (net (code "361") (name "unconnected-(U$4-UART5_CTSN-Pad31)") (class "Default")
      (node (ref "U$4") (pin "31") (pinfunction "UART5_CTSN_31") (pintype "passive"))
    )
    (net (code "362") (name "unconnected-(U$4-UART5_RTSN-Pad32)") (class "Default")
      (node (ref "U$4") (pin "32") (pinfunction "UART5_RTSN_32") (pintype "passive"))
    )
    (net (code "363") (name "unconnected-(U$4-UART5_RXD-Pad38)") (class "Default")
      (node (ref "U$4") (pin "38") (pinfunction "UART5_RXD_38") (pintype "passive"))
    )
    (net (code "364") (name "unconnected-(U$4-UART5_TXD-Pad37)") (class "Default")
      (node (ref "U$4") (pin "37") (pinfunction "UART5_TXD_37") (pintype "passive"))
    )
    (net (code "365") (name "unconnected-(U$4-VDD_ADC-Pad78)") (class "Default")
      (node (ref "U$4") (pin "78") (pinfunction "VDD_ADC_78") (pintype "passive"))
    )
    (net (code "366") (name "unconnected-(U$5-PadMIC)") (class "Default")
      (node (ref "U$5") (pin "MIC") (pinfunction "MIC_MIC") (pintype "bidirectional"))
    )
    (net (code "367") (name "unconnected-(U$5-PadNC)") (class "Default")
      (node (ref "U$5") (pin "NC") (pinfunction "NC_NC") (pintype "bidirectional"))
    )
  )
)
